# 8x8v2.net
KiCad netlist of a schematic drawn in Altium Designer
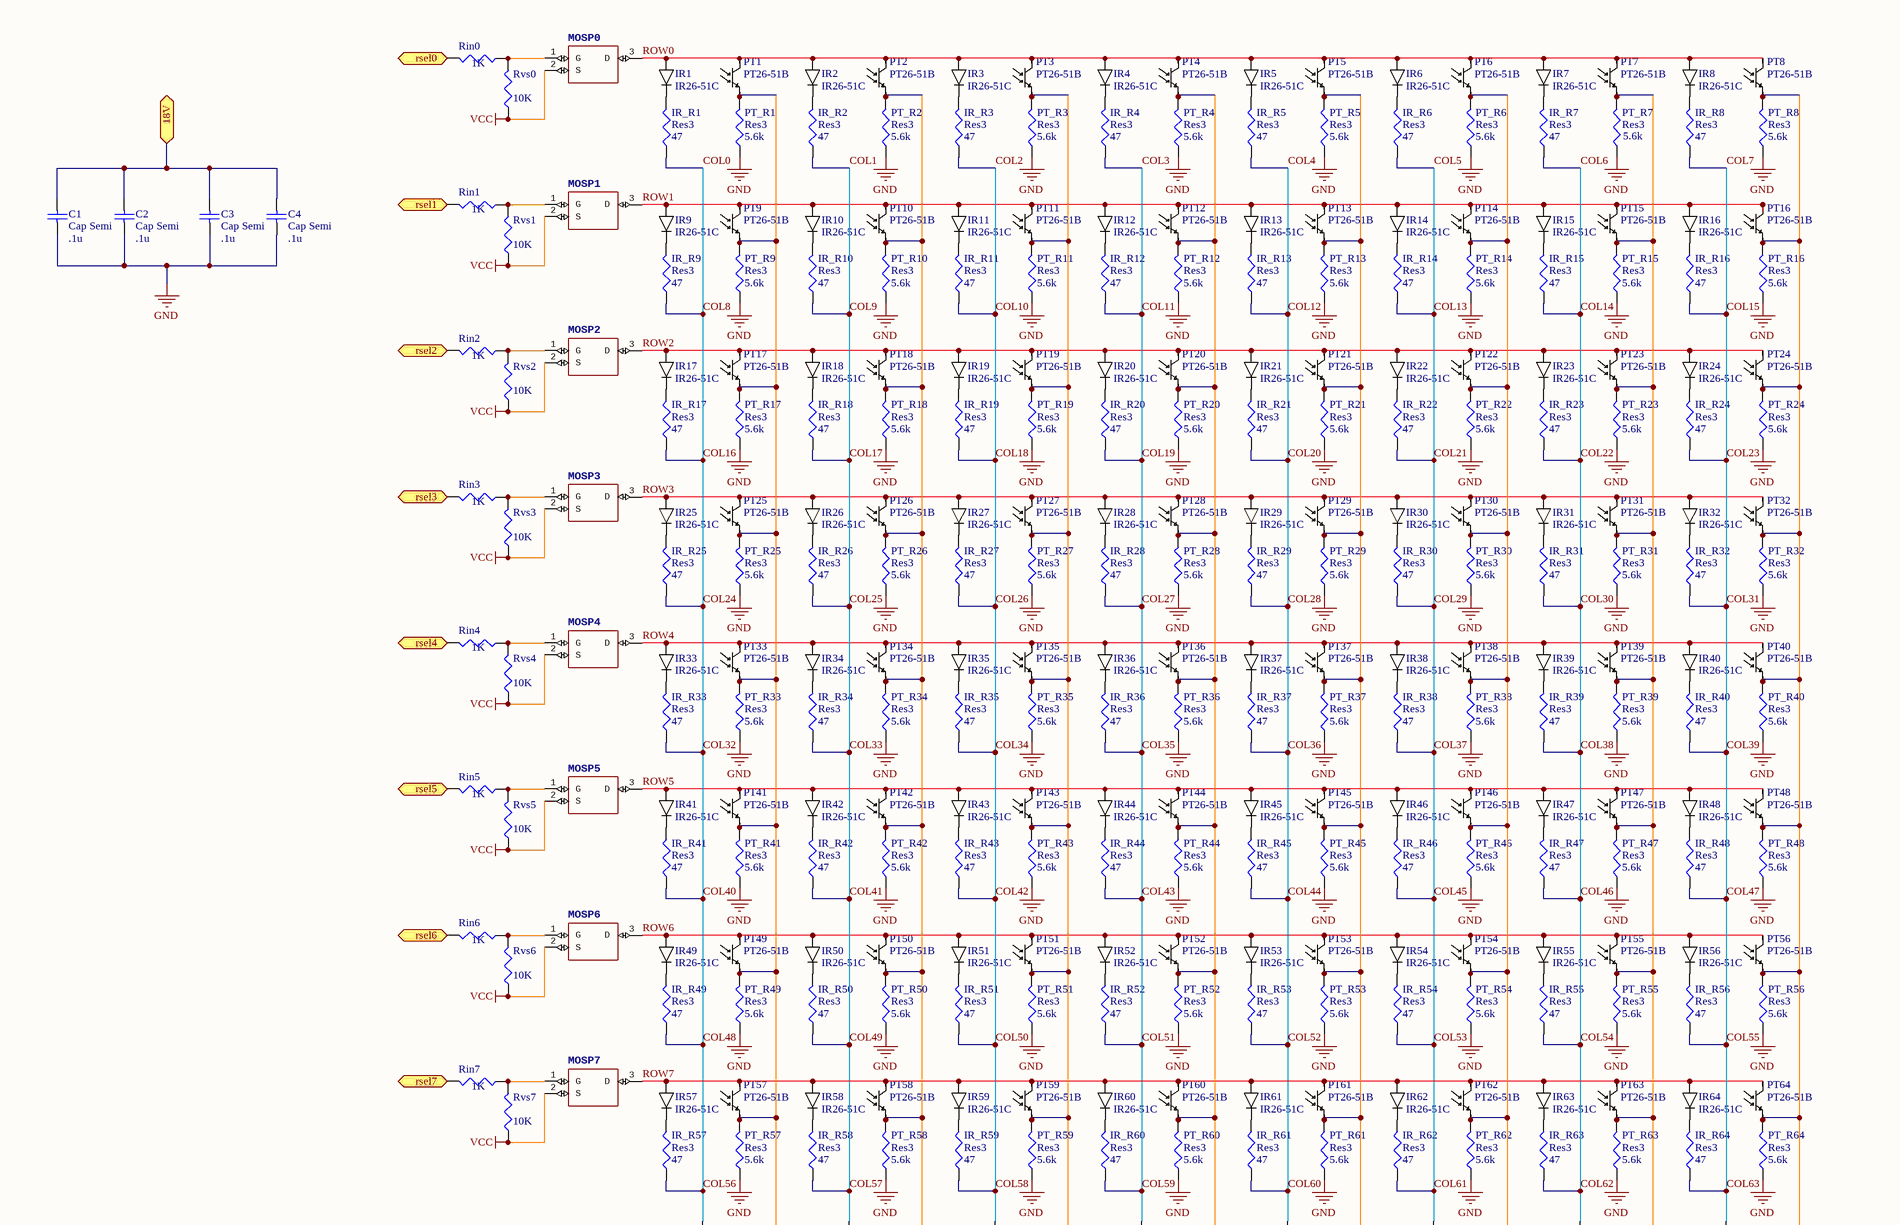
[diagram p0: 8x8v2.SchDoc, top left]
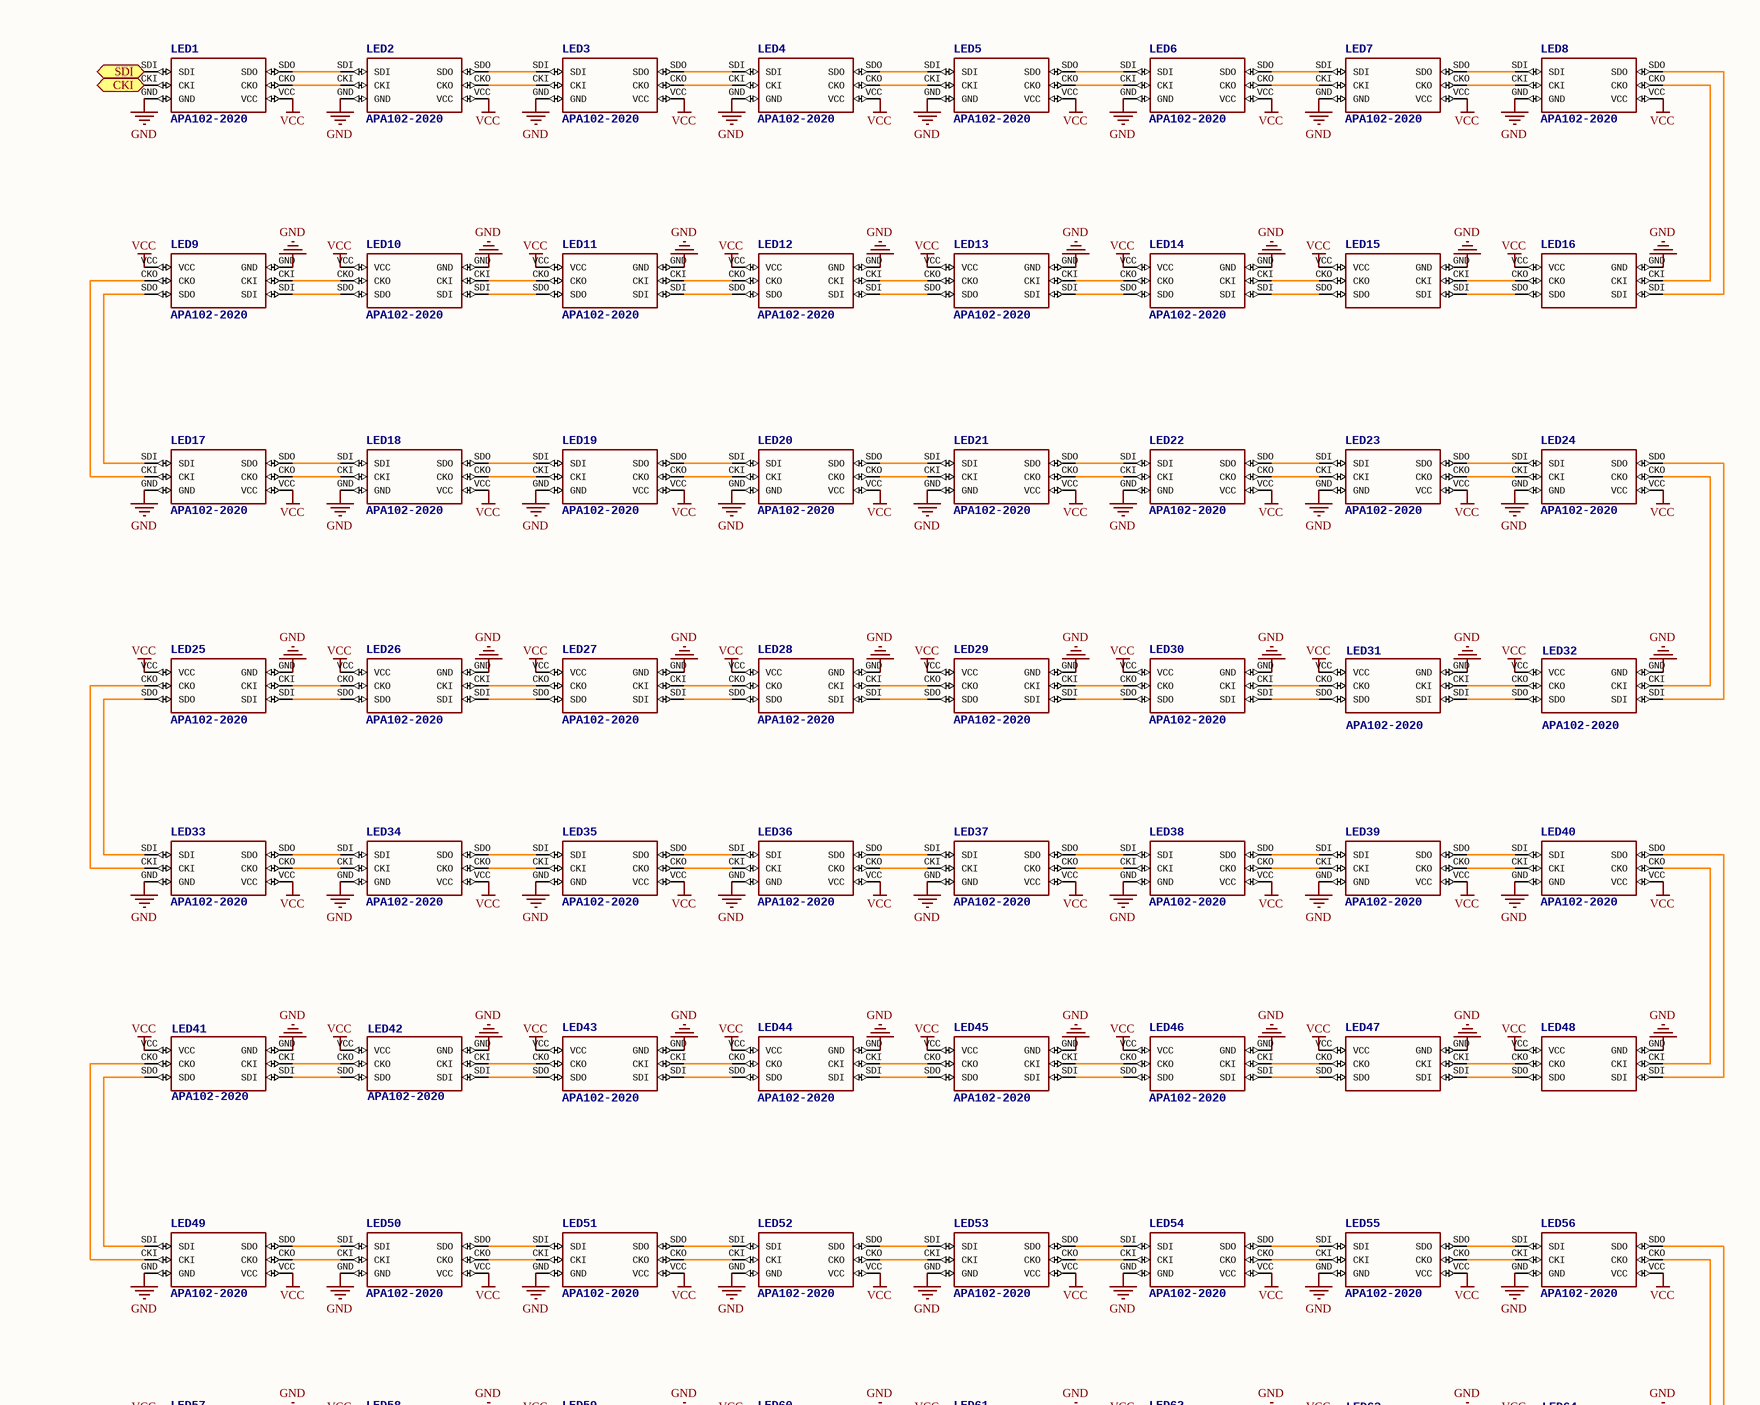
[diagram p1: 8x8v2.SchDoc, top right]
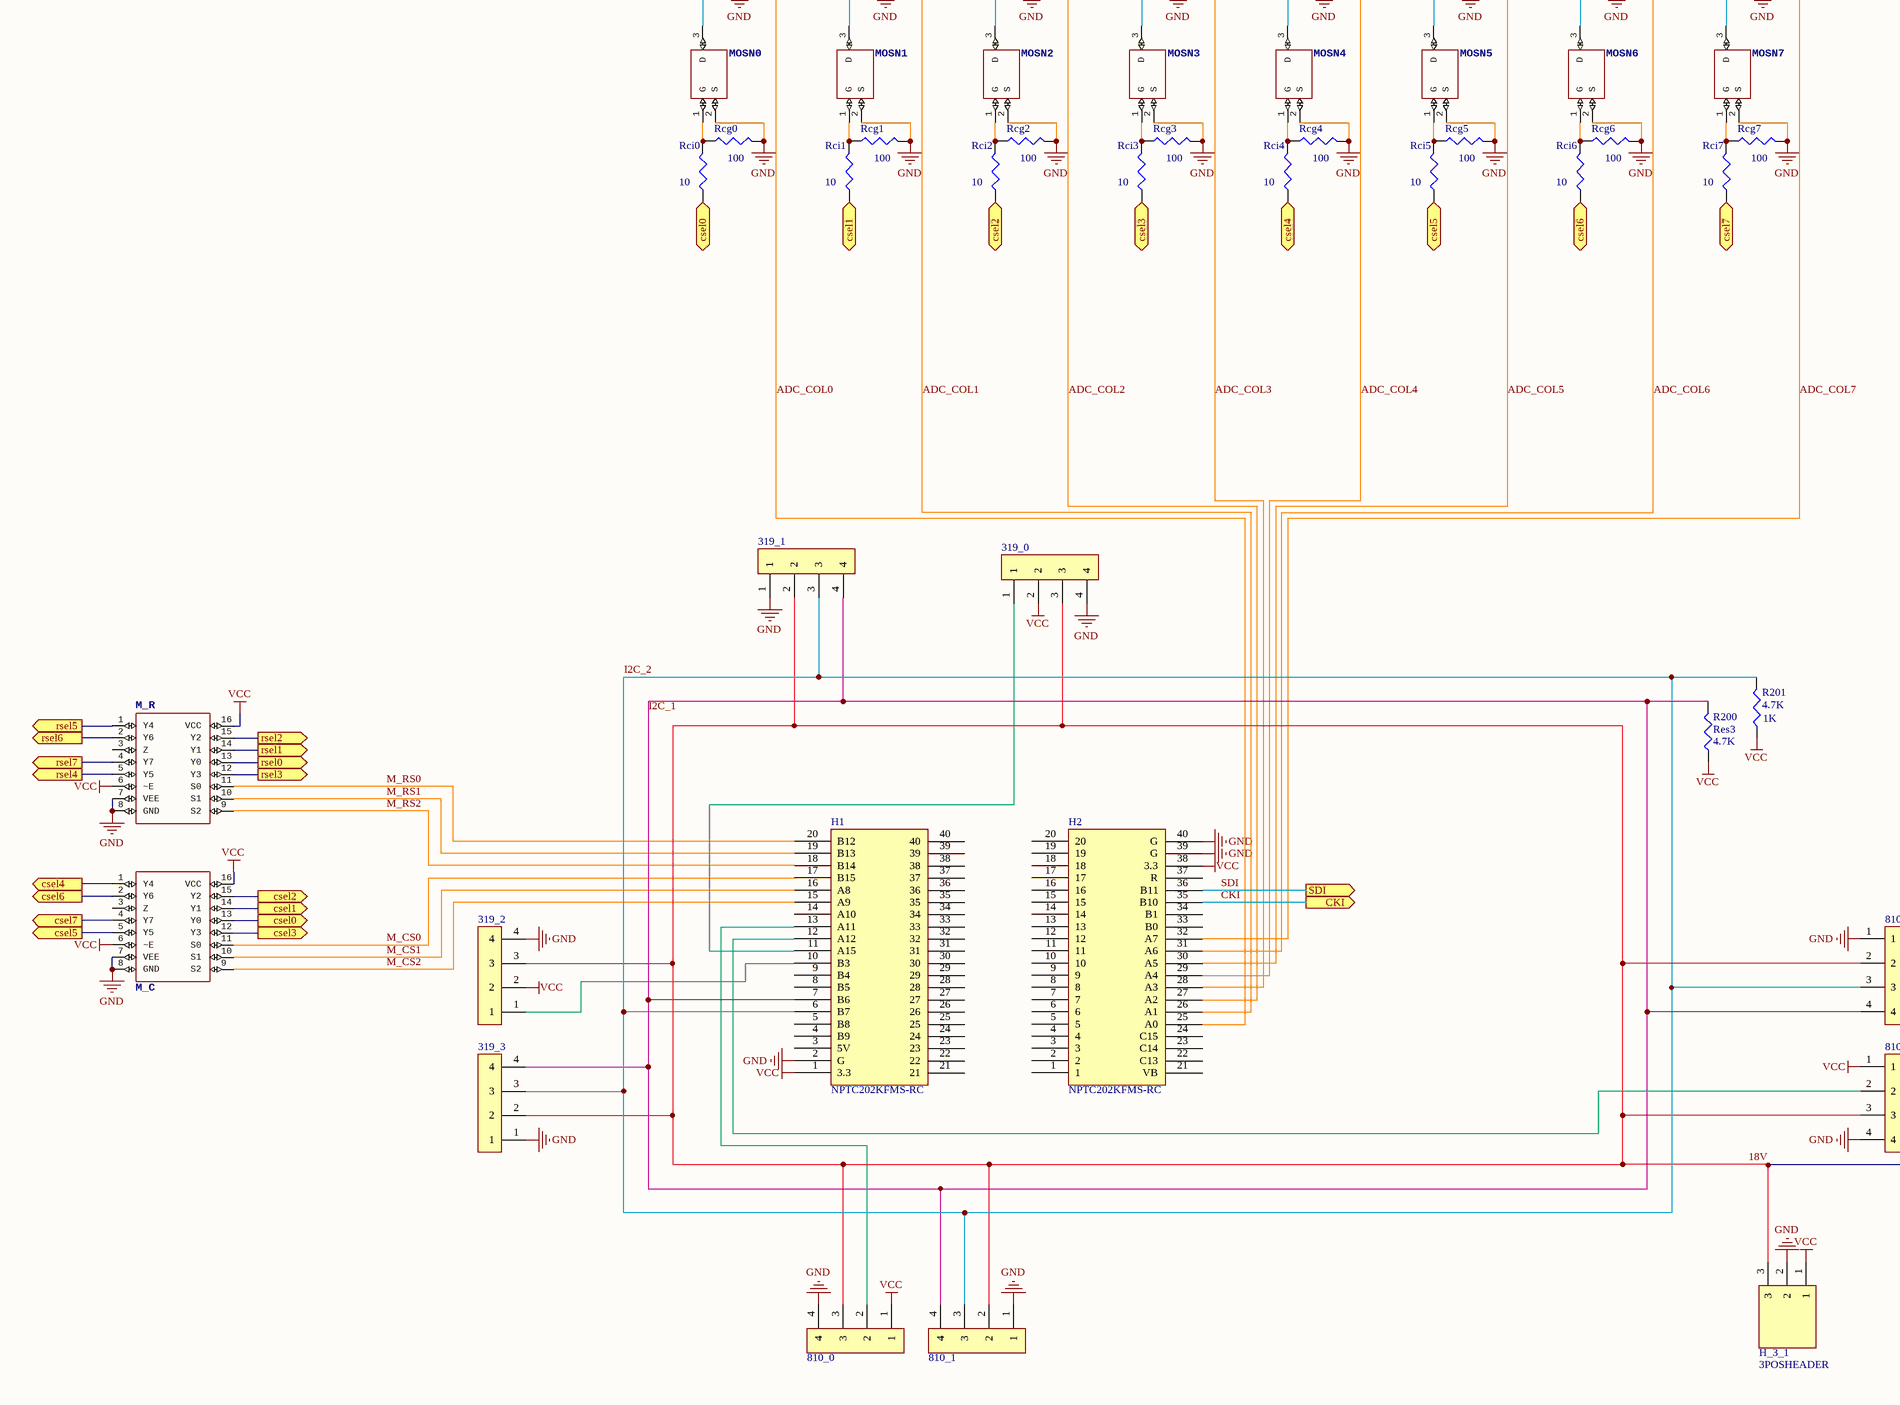
[diagram p2: 8x8v2.SchDoc, bottom left]
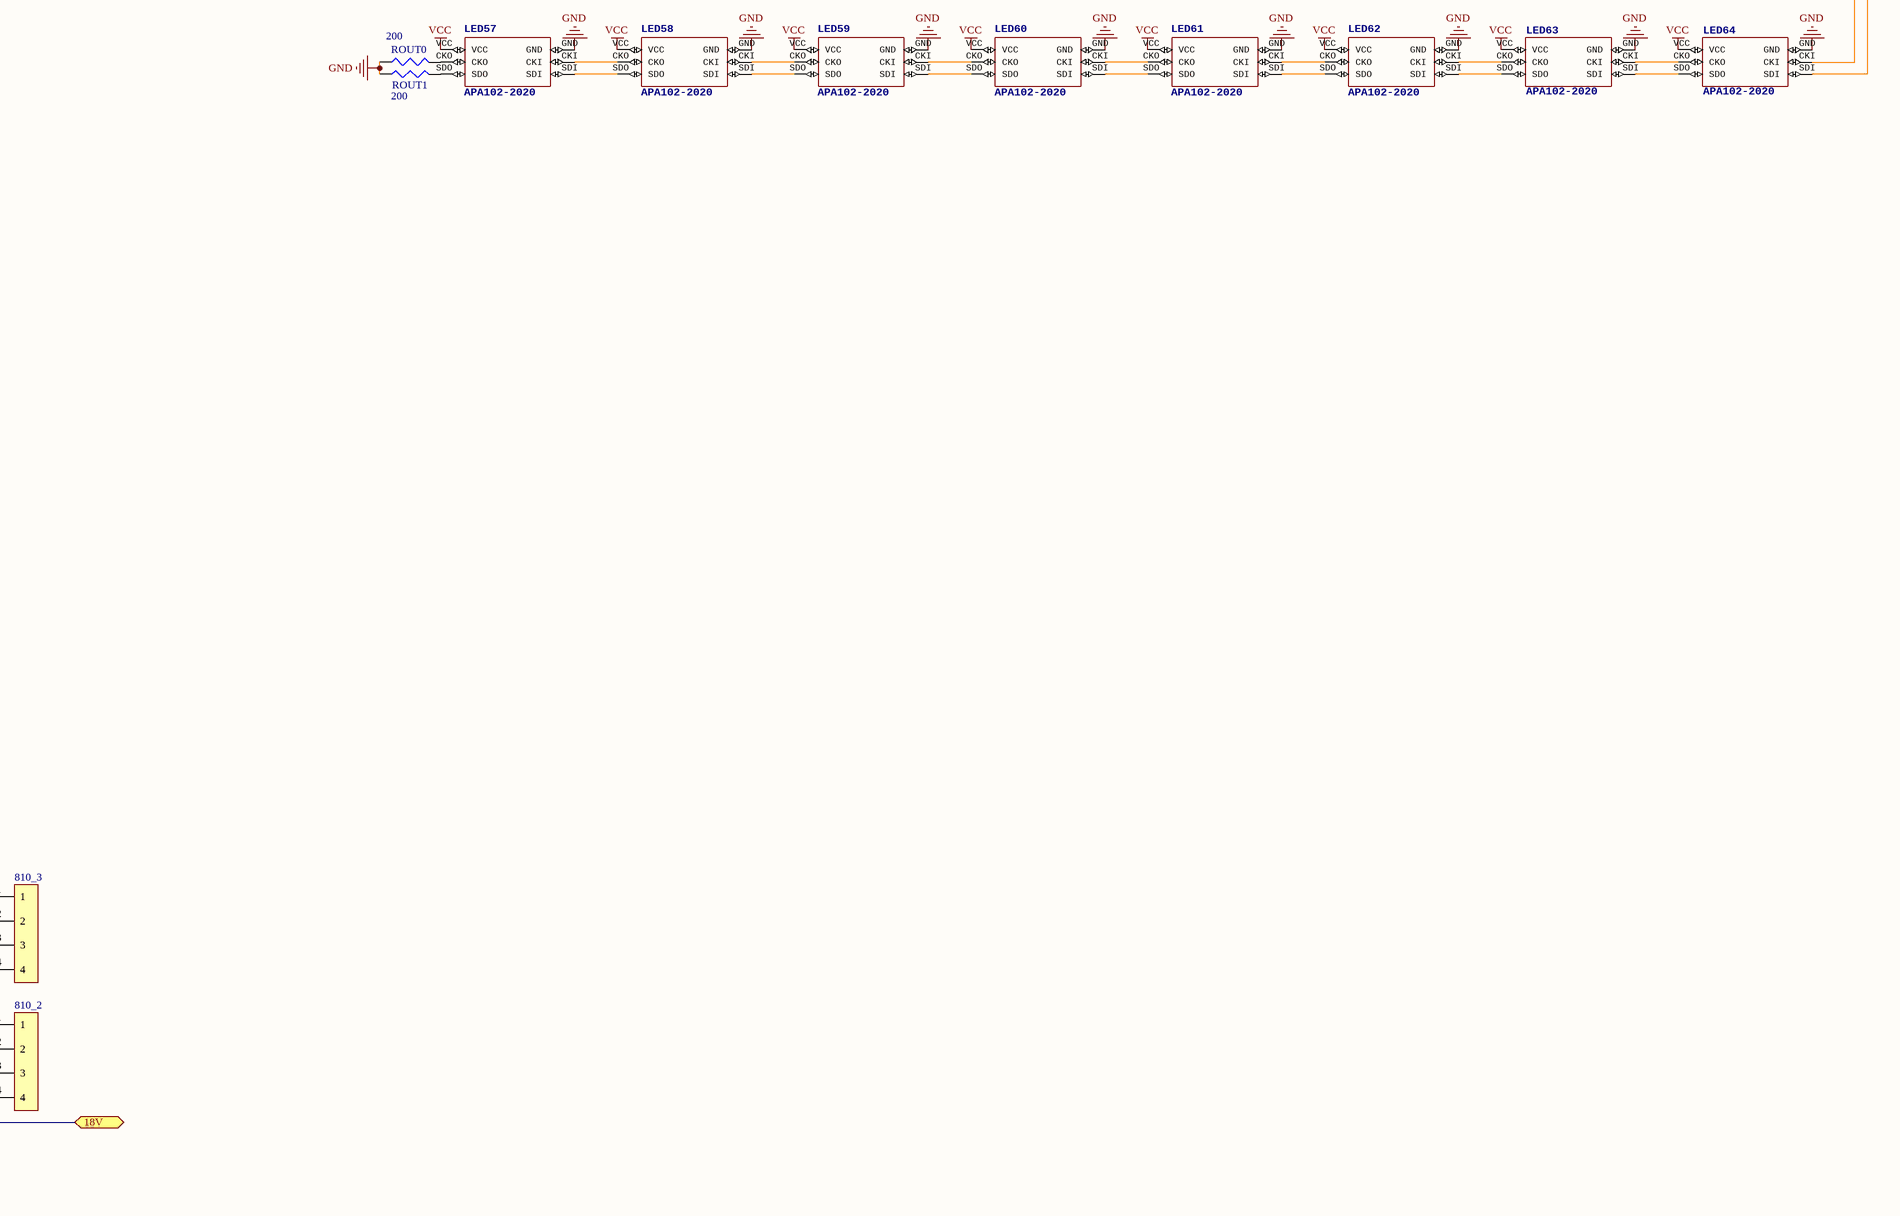
[diagram p3: 8x8v2.SchDoc, bottom right]

(export (version "E")
  (design (tool "Eeschema 10.0.6"))
  (components
    (comp (ref "319_0")
      (value "319_4")
      (footprint "319_4")
      (description "pad for mill max 319 series")
      (libsource (lib "T25_Components") (part "319_4"))
    )
    (comp (ref "319_1")
      (value "319_4")
      (footprint "319_4")
      (description "pad for mill max 319 series")
      (libsource (lib "T25_Components") (part "319_4"))
    )
    (comp (ref "319_2")
      (value "319_4")
      (footprint "319_4")
      (description "pad for mill max 319 series")
      (libsource (lib "") (part "319_4_1"))
    )
    (comp (ref "319_3")
      (value "319_4")
      (footprint "319_4")
      (description "pad for mill max 319 series")
      (libsource (lib "") (part "319_4_1"))
    )
    (comp (ref "810_0")
      (value "810_4")
      (footprint "810_4")
      (description "pad for mill max 810 series")
      (libsource (lib "T25_Components") (part "810_4"))
    )
    (comp (ref "810_1")
      (value "810_4")
      (footprint "810_4")
      (description "pad for mill max 810 series")
      (libsource (lib "T25_Components") (part "810_4"))
    )
    (comp (ref "810_2")
      (value "810_4")
      (footprint "810_4")
      (description "pad for mill max 810 series")
      (libsource (lib "") (part "810_4_1"))
    )
    (comp (ref "810_3")
      (value "810_4")
      (footprint "810_4")
      (description "pad for mill max 810 series")
      (libsource (lib "") (part "810_4_1"))
    )
    (comp (ref "C1")
      (value "Cap Semi")
      (footprint "0402")
      (description "Capacitor (Semiconductor SIM Model)")
      (fields (field (name "ALTIUM_VALUE") ".1u") (field (name "PUBLISHER") "Altium Limited"))
      (libsource (lib "Miscellaneous Devices") (part "Cap Semi"))
    )
    (comp (ref "C2")
      (value "Cap Semi")
      (footprint "0402")
      (description "Capacitor (Semiconductor SIM Model)")
      (fields (field (name "ALTIUM_VALUE") ".1u") (field (name "PUBLISHER") "Altium Limited"))
      (libsource (lib "Miscellaneous Devices") (part "Cap Semi"))
    )
    (comp (ref "C3")
      (value "Cap Semi")
      (footprint "0402")
      (description "Capacitor (Semiconductor SIM Model)")
      (fields (field (name "ALTIUM_VALUE") ".1u") (field (name "PUBLISHER") "Altium Limited"))
      (libsource (lib "Miscellaneous Devices") (part "Cap Semi"))
    )
    (comp (ref "C4")
      (value "Cap Semi")
      (footprint "0402")
      (description "Capacitor (Semiconductor SIM Model)")
      (fields (field (name "ALTIUM_VALUE") ".1u") (field (name "PUBLISHER") "Altium Limited"))
      (libsource (lib "Miscellaneous Devices") (part "Cap Semi"))
    )
    (comp (ref "H1")
      (value "NPTC202KFMS-RC")
      (footprint "NPTC202KFMS-RC")
      (description "40 Position Header Connector 0.100\" (2.54mm) Surface Mount Tin")
      (libsource (lib "T25_Components") (part "NPTC202KFMS-RC"))
    )
    (comp (ref "H2")
      (value "NPTC202KFMS-RC")
      (footprint "NPTC202KFMS-RC")
      (description "40 Position Header Connector 0.100\" (2.54mm) Surface Mount Tin")
      (libsource (lib "T25_Components") (part "NPTC202KFMS-RC"))
    )
    (comp (ref "H_3_1")
      (value "3POSHEADER")
      (footprint "3POSHEADER")
      (description "3 POS HEADER")
      (libsource (lib "T25_Components") (part "3POSHEADER"))
    )
    (comp (ref "IR1")
      (value "IR26-51C")
      (footprint "SFH 4056")
      (description "IR26-51C SMD IR Emitter")
      (libsource (lib "T25_Components") (part "IR26-51C"))
    )
    (comp (ref "IR2")
      (value "IR26-51C")
      (footprint "SFH 4056")
      (description "IR26-51C SMD IR Emitter")
      (libsource (lib "T25_Components") (part "IR26-51C"))
    )
    (comp (ref "IR3")
      (value "IR26-51C")
      (footprint "SFH 4056")
      (description "IR26-51C SMD IR Emitter")
      (libsource (lib "T25_Components") (part "IR26-51C"))
    )
    (comp (ref "IR4")
      (value "IR26-51C")
      (footprint "SFH 4056")
      (description "IR26-51C SMD IR Emitter")
      (libsource (lib "T25_Components") (part "IR26-51C"))
    )
    (comp (ref "IR5")
      (value "IR26-51C")
      (footprint "SFH 4056")
      (description "IR26-51C SMD IR Emitter")
      (libsource (lib "T25_Components") (part "IR26-51C"))
    )
    (comp (ref "IR6")
      (value "IR26-51C")
      (footprint "SFH 4056")
      (description "IR26-51C SMD IR Emitter")
      (libsource (lib "T25_Components") (part "IR26-51C"))
    )
    (comp (ref "IR7")
      (value "IR26-51C")
      (footprint "SFH 4056")
      (description "IR26-51C SMD IR Emitter")
      (libsource (lib "T25_Components") (part "IR26-51C"))
    )
    (comp (ref "IR8")
      (value "IR26-51C")
      (footprint "SFH 4056")
      (description "IR26-51C SMD IR Emitter")
      (libsource (lib "T25_Components") (part "IR26-51C"))
    )
    (comp (ref "IR9")
      (value "IR26-51C")
      (footprint "SFH 4056")
      (description "IR26-51C SMD IR Emitter")
      (libsource (lib "T25_Components") (part "IR26-51C"))
    )
    (comp (ref "IR10")
      (value "IR26-51C")
      (footprint "SFH 4056")
      (description "IR26-51C SMD IR Emitter")
      (libsource (lib "T25_Components") (part "IR26-51C"))
    )
    (comp (ref "IR11")
      (value "IR26-51C")
      (footprint "SFH 4056")
      (description "IR26-51C SMD IR Emitter")
      (libsource (lib "T25_Components") (part "IR26-51C"))
    )
    (comp (ref "IR12")
      (value "IR26-51C")
      (footprint "SFH 4056")
      (description "IR26-51C SMD IR Emitter")
      (libsource (lib "T25_Components") (part "IR26-51C"))
    )
    (comp (ref "IR13")
      (value "IR26-51C")
      (footprint "SFH 4056")
      (description "IR26-51C SMD IR Emitter")
      (libsource (lib "T25_Components") (part "IR26-51C"))
    )
    (comp (ref "IR14")
      (value "IR26-51C")
      (footprint "SFH 4056")
      (description "IR26-51C SMD IR Emitter")
      (libsource (lib "T25_Components") (part "IR26-51C"))
    )
    (comp (ref "IR15")
      (value "IR26-51C")
      (footprint "SFH 4056")
      (description "IR26-51C SMD IR Emitter")
      (libsource (lib "T25_Components") (part "IR26-51C"))
    )
    (comp (ref "IR16")
      (value "IR26-51C")
      (footprint "SFH 4056")
      (description "IR26-51C SMD IR Emitter")
      (libsource (lib "T25_Components") (part "IR26-51C"))
    )
    (comp (ref "IR17")
      (value "IR26-51C")
      (footprint "SFH 4056")
      (description "IR26-51C SMD IR Emitter")
      (libsource (lib "T25_Components") (part "IR26-51C"))
    )
    (comp (ref "IR18")
      (value "IR26-51C")
      (footprint "SFH 4056")
      (description "IR26-51C SMD IR Emitter")
      (libsource (lib "T25_Components") (part "IR26-51C"))
    )
    (comp (ref "IR19")
      (value "IR26-51C")
      (footprint "SFH 4056")
      (description "IR26-51C SMD IR Emitter")
      (libsource (lib "T25_Components") (part "IR26-51C"))
    )
    (comp (ref "IR20")
      (value "IR26-51C")
      (footprint "SFH 4056")
      (description "IR26-51C SMD IR Emitter")
      (libsource (lib "T25_Components") (part "IR26-51C"))
    )
    (comp (ref "IR21")
      (value "IR26-51C")
      (footprint "SFH 4056")
      (description "IR26-51C SMD IR Emitter")
      (libsource (lib "T25_Components") (part "IR26-51C"))
    )
    (comp (ref "IR22")
      (value "IR26-51C")
      (footprint "SFH 4056")
      (description "IR26-51C SMD IR Emitter")
      (libsource (lib "T25_Components") (part "IR26-51C"))
    )
    (comp (ref "IR23")
      (value "IR26-51C")
      (footprint "SFH 4056")
      (description "IR26-51C SMD IR Emitter")
      (libsource (lib "T25_Components") (part "IR26-51C"))
    )
    (comp (ref "IR24")
      (value "IR26-51C")
      (footprint "SFH 4056")
      (description "IR26-51C SMD IR Emitter")
      (libsource (lib "T25_Components") (part "IR26-51C"))
    )
    (comp (ref "IR25")
      (value "IR26-51C")
      (footprint "SFH 4056")
      (description "IR26-51C SMD IR Emitter")
      (libsource (lib "T25_Components") (part "IR26-51C"))
    )
    (comp (ref "IR26")
      (value "IR26-51C")
      (footprint "SFH 4056")
      (description "IR26-51C SMD IR Emitter")
      (libsource (lib "T25_Components") (part "IR26-51C"))
    )
    (comp (ref "IR27")
      (value "IR26-51C")
      (footprint "SFH 4056")
      (description "IR26-51C SMD IR Emitter")
      (libsource (lib "T25_Components") (part "IR26-51C"))
    )
    (comp (ref "IR28")
      (value "IR26-51C")
      (footprint "SFH 4056")
      (description "IR26-51C SMD IR Emitter")
      (libsource (lib "T25_Components") (part "IR26-51C"))
    )
    (comp (ref "IR29")
      (value "IR26-51C")
      (footprint "SFH 4056")
      (description "IR26-51C SMD IR Emitter")
      (libsource (lib "T25_Components") (part "IR26-51C"))
    )
    (comp (ref "IR30")
      (value "IR26-51C")
      (footprint "SFH 4056")
      (description "IR26-51C SMD IR Emitter")
      (libsource (lib "T25_Components") (part "IR26-51C"))
    )
    (comp (ref "IR31")
      (value "IR26-51C")
      (footprint "SFH 4056")
      (description "IR26-51C SMD IR Emitter")
      (libsource (lib "T25_Components") (part "IR26-51C"))
    )
    (comp (ref "IR32")
      (value "IR26-51C")
      (footprint "SFH 4056")
      (description "IR26-51C SMD IR Emitter")
      (libsource (lib "T25_Components") (part "IR26-51C"))
    )
    (comp (ref "IR33")
      (value "IR26-51C")
      (footprint "SFH 4056")
      (description "IR26-51C SMD IR Emitter")
      (libsource (lib "T25_Components") (part "IR26-51C"))
    )
    (comp (ref "IR34")
      (value "IR26-51C")
      (footprint "SFH 4056")
      (description "IR26-51C SMD IR Emitter")
      (libsource (lib "T25_Components") (part "IR26-51C"))
    )
    (comp (ref "IR35")
      (value "IR26-51C")
      (footprint "SFH 4056")
      (description "IR26-51C SMD IR Emitter")
      (libsource (lib "T25_Components") (part "IR26-51C"))
    )
    (comp (ref "IR36")
      (value "IR26-51C")
      (footprint "SFH 4056")
      (description "IR26-51C SMD IR Emitter")
      (libsource (lib "T25_Components") (part "IR26-51C"))
    )
    (comp (ref "IR37")
      (value "IR26-51C")
      (footprint "SFH 4056")
      (description "IR26-51C SMD IR Emitter")
      (libsource (lib "T25_Components") (part "IR26-51C"))
    )
    (comp (ref "IR38")
      (value "IR26-51C")
      (footprint "SFH 4056")
      (description "IR26-51C SMD IR Emitter")
      (libsource (lib "T25_Components") (part "IR26-51C"))
    )
    (comp (ref "IR39")
      (value "IR26-51C")
      (footprint "SFH 4056")
      (description "IR26-51C SMD IR Emitter")
      (libsource (lib "T25_Components") (part "IR26-51C"))
    )
    (comp (ref "IR40")
      (value "IR26-51C")
      (footprint "SFH 4056")
      (description "IR26-51C SMD IR Emitter")
      (libsource (lib "T25_Components") (part "IR26-51C"))
    )
    (comp (ref "IR41")
      (value "IR26-51C")
      (footprint "SFH 4056")
      (description "IR26-51C SMD IR Emitter")
      (libsource (lib "T25_Components") (part "IR26-51C"))
    )
    (comp (ref "IR42")
      (value "IR26-51C")
      (footprint "SFH 4056")
      (description "IR26-51C SMD IR Emitter")
      (libsource (lib "T25_Components") (part "IR26-51C"))
    )
    (comp (ref "IR43")
      (value "IR26-51C")
      (footprint "SFH 4056")
      (description "IR26-51C SMD IR Emitter")
      (libsource (lib "T25_Components") (part "IR26-51C"))
    )
    (comp (ref "IR44")
      (value "IR26-51C")
      (footprint "SFH 4056")
      (description "IR26-51C SMD IR Emitter")
      (libsource (lib "T25_Components") (part "IR26-51C"))
    )
    (comp (ref "IR45")
      (value "IR26-51C")
      (footprint "SFH 4056")
      (description "IR26-51C SMD IR Emitter")
      (libsource (lib "T25_Components") (part "IR26-51C"))
    )
    (comp (ref "IR46")
      (value "IR26-51C")
      (footprint "SFH 4056")
      (description "IR26-51C SMD IR Emitter")
      (libsource (lib "T25_Components") (part "IR26-51C"))
    )
    (comp (ref "IR47")
      (value "IR26-51C")
      (footprint "SFH 4056")
      (description "IR26-51C SMD IR Emitter")
      (libsource (lib "T25_Components") (part "IR26-51C"))
    )
    (comp (ref "IR48")
      (value "IR26-51C")
      (footprint "SFH 4056")
      (description "IR26-51C SMD IR Emitter")
      (libsource (lib "T25_Components") (part "IR26-51C"))
    )
    (comp (ref "IR49")
      (value "IR26-51C")
      (footprint "SFH 4056")
      (description "IR26-51C SMD IR Emitter")
      (libsource (lib "T25_Components") (part "IR26-51C"))
    )
    (comp (ref "IR50")
      (value "IR26-51C")
      (footprint "SFH 4056")
      (description "IR26-51C SMD IR Emitter")
      (libsource (lib "T25_Components") (part "IR26-51C"))
    )
    (comp (ref "IR51")
      (value "IR26-51C")
      (footprint "SFH 4056")
      (description "IR26-51C SMD IR Emitter")
      (libsource (lib "T25_Components") (part "IR26-51C"))
    )
    (comp (ref "IR52")
      (value "IR26-51C")
      (footprint "SFH 4056")
      (description "IR26-51C SMD IR Emitter")
      (libsource (lib "T25_Components") (part "IR26-51C"))
    )
    (comp (ref "IR53")
      (value "IR26-51C")
      (footprint "SFH 4056")
      (description "IR26-51C SMD IR Emitter")
      (libsource (lib "T25_Components") (part "IR26-51C"))
    )
    (comp (ref "IR54")
      (value "IR26-51C")
      (footprint "SFH 4056")
      (description "IR26-51C SMD IR Emitter")
      (libsource (lib "T25_Components") (part "IR26-51C"))
    )
    (comp (ref "IR55")
      (value "IR26-51C")
      (footprint "SFH 4056")
      (description "IR26-51C SMD IR Emitter")
      (libsource (lib "T25_Components") (part "IR26-51C"))
    )
    (comp (ref "IR56")
      (value "IR26-51C")
      (footprint "SFH 4056")
      (description "IR26-51C SMD IR Emitter")
      (libsource (lib "T25_Components") (part "IR26-51C"))
    )
    (comp (ref "IR57")
      (value "IR26-51C")
      (footprint "SFH 4056")
      (description "IR26-51C SMD IR Emitter")
      (libsource (lib "T25_Components") (part "IR26-51C"))
    )
    (comp (ref "IR58")
      (value "IR26-51C")
      (footprint "SFH 4056")
      (description "IR26-51C SMD IR Emitter")
      (libsource (lib "T25_Components") (part "IR26-51C"))
    )
    (comp (ref "IR59")
      (value "IR26-51C")
      (footprint "SFH 4056")
      (description "IR26-51C SMD IR Emitter")
      (libsource (lib "T25_Components") (part "IR26-51C"))
    )
    (comp (ref "IR60")
      (value "IR26-51C")
      (footprint "SFH 4056")
      (description "IR26-51C SMD IR Emitter")
      (libsource (lib "T25_Components") (part "IR26-51C"))
    )
    (comp (ref "IR61")
      (value "IR26-51C")
      (footprint "SFH 4056")
      (description "IR26-51C SMD IR Emitter")
      (libsource (lib "T25_Components") (part "IR26-51C"))
    )
    (comp (ref "IR62")
      (value "IR26-51C")
      (footprint "SFH 4056")
      (description "IR26-51C SMD IR Emitter")
      (libsource (lib "T25_Components") (part "IR26-51C"))
    )
    (comp (ref "IR63")
      (value "IR26-51C")
      (footprint "SFH 4056")
      (description "IR26-51C SMD IR Emitter")
      (libsource (lib "T25_Components") (part "IR26-51C"))
    )
    (comp (ref "IR64")
      (value "IR26-51C")
      (footprint "SFH 4056")
      (description "IR26-51C SMD IR Emitter")
      (libsource (lib "T25_Components") (part "IR26-51C"))
    )
    (comp (ref "IR_R1")
      (value "Res3")
      (footprint "J1-0603")
      (description "IR Emitter Resistor")
      (fields (field (name "ALTIUM_VALUE") "47") (field (name "PUBLISHER") "Altium Limited"))
      (libsource (lib "Miscellaneous Devices") (part "Res3"))
    )
    (comp (ref "IR_R2")
      (value "Res3")
      (footprint "J1-0603")
      (description "IR Emitter Resistor")
      (fields (field (name "ALTIUM_VALUE") "47") (field (name "PUBLISHER") "Altium Limited"))
      (libsource (lib "Miscellaneous Devices") (part "Res3"))
    )
    (comp (ref "IR_R3")
      (value "Res3")
      (footprint "J1-0603")
      (description "IR Emitter Resistor")
      (fields (field (name "ALTIUM_VALUE") "47") (field (name "PUBLISHER") "Altium Limited"))
      (libsource (lib "Miscellaneous Devices") (part "Res3"))
    )
    (comp (ref "IR_R4")
      (value "Res3")
      (footprint "J1-0603")
      (description "IR Emitter Resistor")
      (fields (field (name "ALTIUM_VALUE") "47") (field (name "PUBLISHER") "Altium Limited"))
      (libsource (lib "Miscellaneous Devices") (part "Res3"))
    )
    (comp (ref "IR_R5")
      (value "Res3")
      (footprint "J1-0603")
      (description "IR Emitter Resistor")
      (fields (field (name "ALTIUM_VALUE") "47") (field (name "PUBLISHER") "Altium Limited"))
      (libsource (lib "Miscellaneous Devices") (part "Res3"))
    )
    (comp (ref "IR_R6")
      (value "Res3")
      (footprint "J1-0603")
      (description "IR Emitter Resistor")
      (fields (field (name "ALTIUM_VALUE") "47") (field (name "PUBLISHER") "Altium Limited"))
      (libsource (lib "Miscellaneous Devices") (part "Res3"))
    )
    (comp (ref "IR_R7")
      (value "Res3")
      (footprint "J1-0603")
      (description "IR Emitter Resistor")
      (fields (field (name "ALTIUM_VALUE") "47") (field (name "PUBLISHER") "Altium Limited"))
      (libsource (lib "Miscellaneous Devices") (part "Res3"))
    )
    (comp (ref "IR_R8")
      (value "Res3")
      (footprint "J1-0603")
      (description "IR Emitter Resistor")
      (fields (field (name "ALTIUM_VALUE") "47") (field (name "PUBLISHER") "Altium Limited"))
      (libsource (lib "Miscellaneous Devices") (part "Res3"))
    )
    (comp (ref "IR_R9")
      (value "Res3")
      (footprint "J1-0603")
      (description "IR Emitter Resistor")
      (fields (field (name "ALTIUM_VALUE") "47") (field (name "PUBLISHER") "Altium Limited"))
      (libsource (lib "Miscellaneous Devices") (part "Res3"))
    )
    (comp (ref "IR_R10")
      (value "Res3")
      (footprint "J1-0603")
      (description "IR Emitter Resistor")
      (fields (field (name "ALTIUM_VALUE") "47") (field (name "PUBLISHER") "Altium Limited"))
      (libsource (lib "Miscellaneous Devices") (part "Res3"))
    )
    (comp (ref "IR_R11")
      (value "Res3")
      (footprint "J1-0603")
      (description "IR Emitter Resistor")
      (fields (field (name "ALTIUM_VALUE") "47") (field (name "PUBLISHER") "Altium Limited"))
      (libsource (lib "Miscellaneous Devices") (part "Res3"))
    )
    (comp (ref "IR_R12")
      (value "Res3")
      (footprint "J1-0603")
      (description "IR Emitter Resistor")
      (fields (field (name "ALTIUM_VALUE") "47") (field (name "PUBLISHER") "Altium Limited"))
      (libsource (lib "Miscellaneous Devices") (part "Res3"))
    )
    (comp (ref "IR_R13")
      (value "Res3")
      (footprint "J1-0603")
      (description "IR Emitter Resistor")
      (fields (field (name "ALTIUM_VALUE") "47") (field (name "PUBLISHER") "Altium Limited"))
      (libsource (lib "Miscellaneous Devices") (part "Res3"))
    )
    (comp (ref "IR_R14")
      (value "Res3")
      (footprint "J1-0603")
      (description "IR Emitter Resistor")
      (fields (field (name "ALTIUM_VALUE") "47") (field (name "PUBLISHER") "Altium Limited"))
      (libsource (lib "Miscellaneous Devices") (part "Res3"))
    )
    (comp (ref "IR_R15")
      (value "Res3")
      (footprint "J1-0603")
      (description "IR Emitter Resistor")
      (fields (field (name "ALTIUM_VALUE") "47") (field (name "PUBLISHER") "Altium Limited"))
      (libsource (lib "Miscellaneous Devices") (part "Res3"))
    )
    (comp (ref "IR_R16")
      (value "Res3")
      (footprint "J1-0603")
      (description "IR Emitter Resistor")
      (fields (field (name "ALTIUM_VALUE") "47") (field (name "PUBLISHER") "Altium Limited"))
      (libsource (lib "Miscellaneous Devices") (part "Res3"))
    )
    (comp (ref "IR_R17")
      (value "Res3")
      (footprint "J1-0603")
      (description "IR Emitter Resistor")
      (fields (field (name "ALTIUM_VALUE") "47") (field (name "PUBLISHER") "Altium Limited"))
      (libsource (lib "Miscellaneous Devices") (part "Res3"))
    )
    (comp (ref "IR_R18")
      (value "Res3")
      (footprint "J1-0603")
      (description "IR Emitter Resistor")
      (fields (field (name "ALTIUM_VALUE") "47") (field (name "PUBLISHER") "Altium Limited"))
      (libsource (lib "Miscellaneous Devices") (part "Res3"))
    )
    (comp (ref "IR_R19")
      (value "Res3")
      (footprint "J1-0603")
      (description "IR Emitter Resistor")
      (fields (field (name "ALTIUM_VALUE") "47") (field (name "PUBLISHER") "Altium Limited"))
      (libsource (lib "Miscellaneous Devices") (part "Res3"))
    )
    (comp (ref "IR_R20")
      (value "Res3")
      (footprint "J1-0603")
      (description "IR Emitter Resistor")
      (fields (field (name "ALTIUM_VALUE") "47") (field (name "PUBLISHER") "Altium Limited"))
      (libsource (lib "Miscellaneous Devices") (part "Res3"))
    )
    (comp (ref "IR_R21")
      (value "Res3")
      (footprint "J1-0603")
      (description "IR Emitter Resistor")
      (fields (field (name "ALTIUM_VALUE") "47") (field (name "PUBLISHER") "Altium Limited"))
      (libsource (lib "Miscellaneous Devices") (part "Res3"))
    )
    (comp (ref "IR_R22")
      (value "Res3")
      (footprint "J1-0603")
      (description "IR Emitter Resistor")
      (fields (field (name "ALTIUM_VALUE") "47") (field (name "PUBLISHER") "Altium Limited"))
      (libsource (lib "Miscellaneous Devices") (part "Res3"))
    )
    (comp (ref "IR_R23")
      (value "Res3")
      (footprint "J1-0603")
      (description "IR Emitter Resistor")
      (fields (field (name "ALTIUM_VALUE") "47") (field (name "PUBLISHER") "Altium Limited"))
      (libsource (lib "Miscellaneous Devices") (part "Res3"))
    )
    (comp (ref "IR_R24")
      (value "Res3")
      (footprint "J1-0603")
      (description "IR Emitter Resistor")
      (fields (field (name "ALTIUM_VALUE") "47") (field (name "PUBLISHER") "Altium Limited"))
      (libsource (lib "Miscellaneous Devices") (part "Res3"))
    )
    (comp (ref "IR_R25")
      (value "Res3")
      (footprint "J1-0603")
      (description "IR Emitter Resistor")
      (fields (field (name "ALTIUM_VALUE") "47") (field (name "PUBLISHER") "Altium Limited"))
      (libsource (lib "Miscellaneous Devices") (part "Res3"))
    )
    (comp (ref "IR_R26")
      (value "Res3")
      (footprint "J1-0603")
      (description "IR Emitter Resistor")
      (fields (field (name "ALTIUM_VALUE") "47") (field (name "PUBLISHER") "Altium Limited"))
      (libsource (lib "Miscellaneous Devices") (part "Res3"))
    )
    (comp (ref "IR_R27")
      (value "Res3")
      (footprint "J1-0603")
      (description "IR Emitter Resistor")
      (fields (field (name "ALTIUM_VALUE") "47") (field (name "PUBLISHER") "Altium Limited"))
      (libsource (lib "Miscellaneous Devices") (part "Res3"))
    )
    (comp (ref "IR_R28")
      (value "Res3")
      (footprint "J1-0603")
      (description "IR Emitter Resistor")
      (fields (field (name "ALTIUM_VALUE") "47") (field (name "PUBLISHER") "Altium Limited"))
      (libsource (lib "Miscellaneous Devices") (part "Res3"))
    )
    (comp (ref "IR_R29")
      (value "Res3")
      (footprint "J1-0603")
      (description "IR Emitter Resistor")
      (fields (field (name "ALTIUM_VALUE") "47") (field (name "PUBLISHER") "Altium Limited"))
      (libsource (lib "Miscellaneous Devices") (part "Res3"))
    )
    (comp (ref "IR_R30")
      (value "Res3")
      (footprint "J1-0603")
      (description "IR Emitter Resistor")
      (fields (field (name "ALTIUM_VALUE") "47") (field (name "PUBLISHER") "Altium Limited"))
      (libsource (lib "Miscellaneous Devices") (part "Res3"))
    )
    (comp (ref "IR_R31")
      (value "Res3")
      (footprint "J1-0603")
      (description "IR Emitter Resistor")
      (fields (field (name "ALTIUM_VALUE") "47") (field (name "PUBLISHER") "Altium Limited"))
      (libsource (lib "Miscellaneous Devices") (part "Res3"))
    )
    (comp (ref "IR_R32")
      (value "Res3")
      (footprint "J1-0603")
      (description "IR Emitter Resistor")
      (fields (field (name "ALTIUM_VALUE") "47") (field (name "PUBLISHER") "Altium Limited"))
      (libsource (lib "Miscellaneous Devices") (part "Res3"))
    )
    (comp (ref "IR_R33")
      (value "Res3")
      (footprint "J1-0603")
      (description "IR Emitter Resistor")
      (fields (field (name "ALTIUM_VALUE") "47") (field (name "PUBLISHER") "Altium Limited"))
      (libsource (lib "Miscellaneous Devices") (part "Res3"))
    )
    (comp (ref "IR_R34")
      (value "Res3")
      (footprint "J1-0603")
      (description "IR Emitter Resistor")
      (fields (field (name "ALTIUM_VALUE") "47") (field (name "PUBLISHER") "Altium Limited"))
      (libsource (lib "Miscellaneous Devices") (part "Res3"))
    )
    (comp (ref "IR_R35")
      (value "Res3")
      (footprint "J1-0603")
      (description "IR Emitter Resistor")
      (fields (field (name "ALTIUM_VALUE") "47") (field (name "PUBLISHER") "Altium Limited"))
      (libsource (lib "Miscellaneous Devices") (part "Res3"))
    )
    (comp (ref "IR_R36")
      (value "Res3")
      (footprint "J1-0603")
      (description "IR Emitter Resistor")
      (fields (field (name "ALTIUM_VALUE") "47") (field (name "PUBLISHER") "Altium Limited"))
      (libsource (lib "Miscellaneous Devices") (part "Res3"))
    )
    (comp (ref "IR_R37")
      (value "Res3")
      (footprint "J1-0603")
      (description "IR Emitter Resistor")
      (fields (field (name "ALTIUM_VALUE") "47") (field (name "PUBLISHER") "Altium Limited"))
      (libsource (lib "Miscellaneous Devices") (part "Res3"))
    )
    (comp (ref "IR_R38")
      (value "Res3")
      (footprint "J1-0603")
      (description "IR Emitter Resistor")
      (fields (field (name "ALTIUM_VALUE") "47") (field (name "PUBLISHER") "Altium Limited"))
      (libsource (lib "Miscellaneous Devices") (part "Res3"))
    )
    (comp (ref "IR_R39")
      (value "Res3")
      (footprint "J1-0603")
      (description "IR Emitter Resistor")
      (fields (field (name "ALTIUM_VALUE") "47") (field (name "PUBLISHER") "Altium Limited"))
      (libsource (lib "Miscellaneous Devices") (part "Res3"))
    )
    (comp (ref "IR_R40")
      (value "Res3")
      (footprint "J1-0603")
      (description "IR Emitter Resistor")
      (fields (field (name "ALTIUM_VALUE") "47") (field (name "PUBLISHER") "Altium Limited"))
      (libsource (lib "Miscellaneous Devices") (part "Res3"))
    )
    (comp (ref "IR_R41")
      (value "Res3")
      (footprint "J1-0603")
      (description "IR Emitter Resistor")
      (fields (field (name "ALTIUM_VALUE") "47") (field (name "PUBLISHER") "Altium Limited"))
      (libsource (lib "Miscellaneous Devices") (part "Res3"))
    )
    (comp (ref "IR_R42")
      (value "Res3")
      (footprint "J1-0603")
      (description "IR Emitter Resistor")
      (fields (field (name "ALTIUM_VALUE") "47") (field (name "PUBLISHER") "Altium Limited"))
      (libsource (lib "Miscellaneous Devices") (part "Res3"))
    )
    (comp (ref "IR_R43")
      (value "Res3")
      (footprint "J1-0603")
      (description "IR Emitter Resistor")
      (fields (field (name "ALTIUM_VALUE") "47") (field (name "PUBLISHER") "Altium Limited"))
      (libsource (lib "Miscellaneous Devices") (part "Res3"))
    )
    (comp (ref "IR_R44")
      (value "Res3")
      (footprint "J1-0603")
      (description "IR Emitter Resistor")
      (fields (field (name "ALTIUM_VALUE") "47") (field (name "PUBLISHER") "Altium Limited"))
      (libsource (lib "Miscellaneous Devices") (part "Res3"))
    )
    (comp (ref "IR_R45")
      (value "Res3")
      (footprint "J1-0603")
      (description "IR Emitter Resistor")
      (fields (field (name "ALTIUM_VALUE") "47") (field (name "PUBLISHER") "Altium Limited"))
      (libsource (lib "Miscellaneous Devices") (part "Res3"))
    )
    (comp (ref "IR_R46")
      (value "Res3")
      (footprint "J1-0603")
      (description "IR Emitter Resistor")
      (fields (field (name "ALTIUM_VALUE") "47") (field (name "PUBLISHER") "Altium Limited"))
      (libsource (lib "Miscellaneous Devices") (part "Res3"))
    )
    (comp (ref "IR_R47")
      (value "Res3")
      (footprint "J1-0603")
      (description "IR Emitter Resistor")
      (fields (field (name "ALTIUM_VALUE") "47") (field (name "PUBLISHER") "Altium Limited"))
      (libsource (lib "Miscellaneous Devices") (part "Res3"))
    )
    (comp (ref "IR_R48")
      (value "Res3")
      (footprint "J1-0603")
      (description "IR Emitter Resistor")
      (fields (field (name "ALTIUM_VALUE") "47") (field (name "PUBLISHER") "Altium Limited"))
      (libsource (lib "Miscellaneous Devices") (part "Res3"))
    )
    (comp (ref "IR_R49")
      (value "Res3")
      (footprint "J1-0603")
      (description "IR Emitter Resistor")
      (fields (field (name "ALTIUM_VALUE") "47") (field (name "PUBLISHER") "Altium Limited"))
      (libsource (lib "Miscellaneous Devices") (part "Res3"))
    )
    (comp (ref "IR_R50")
      (value "Res3")
      (footprint "J1-0603")
      (description "IR Emitter Resistor")
      (fields (field (name "ALTIUM_VALUE") "47") (field (name "PUBLISHER") "Altium Limited"))
      (libsource (lib "Miscellaneous Devices") (part "Res3"))
    )
    (comp (ref "IR_R51")
      (value "Res3")
      (footprint "J1-0603")
      (description "IR Emitter Resistor")
      (fields (field (name "ALTIUM_VALUE") "47") (field (name "PUBLISHER") "Altium Limited"))
      (libsource (lib "Miscellaneous Devices") (part "Res3"))
    )
    (comp (ref "IR_R52")
      (value "Res3")
      (footprint "J1-0603")
      (description "IR Emitter Resistor")
      (fields (field (name "ALTIUM_VALUE") "47") (field (name "PUBLISHER") "Altium Limited"))
      (libsource (lib "Miscellaneous Devices") (part "Res3"))
    )
    (comp (ref "IR_R53")
      (value "Res3")
      (footprint "J1-0603")
      (description "IR Emitter Resistor")
      (fields (field (name "ALTIUM_VALUE") "47") (field (name "PUBLISHER") "Altium Limited"))
      (libsource (lib "Miscellaneous Devices") (part "Res3"))
    )
    (comp (ref "IR_R54")
      (value "Res3")
      (footprint "J1-0603")
      (description "IR Emitter Resistor")
      (fields (field (name "ALTIUM_VALUE") "47") (field (name "PUBLISHER") "Altium Limited"))
      (libsource (lib "Miscellaneous Devices") (part "Res3"))
    )
    (comp (ref "IR_R55")
      (value "Res3")
      (footprint "J1-0603")
      (description "IR Emitter Resistor")
      (fields (field (name "ALTIUM_VALUE") "47") (field (name "PUBLISHER") "Altium Limited"))
      (libsource (lib "Miscellaneous Devices") (part "Res3"))
    )
    (comp (ref "IR_R56")
      (value "Res3")
      (footprint "J1-0603")
      (description "IR Emitter Resistor")
      (fields (field (name "ALTIUM_VALUE") "47") (field (name "PUBLISHER") "Altium Limited"))
      (libsource (lib "Miscellaneous Devices") (part "Res3"))
    )
    (comp (ref "IR_R57")
      (value "Res3")
      (footprint "J1-0603")
      (description "IR Emitter Resistor")
      (fields (field (name "ALTIUM_VALUE") "47") (field (name "PUBLISHER") "Altium Limited"))
      (libsource (lib "Miscellaneous Devices") (part "Res3"))
    )
    (comp (ref "IR_R58")
      (value "Res3")
      (footprint "J1-0603")
      (description "IR Emitter Resistor")
      (fields (field (name "ALTIUM_VALUE") "47") (field (name "PUBLISHER") "Altium Limited"))
      (libsource (lib "Miscellaneous Devices") (part "Res3"))
    )
    (comp (ref "IR_R59")
      (value "Res3")
      (footprint "J1-0603")
      (description "IR Emitter Resistor")
      (fields (field (name "ALTIUM_VALUE") "47") (field (name "PUBLISHER") "Altium Limited"))
      (libsource (lib "Miscellaneous Devices") (part "Res3"))
    )
    (comp (ref "IR_R60")
      (value "Res3")
      (footprint "J1-0603")
      (description "IR Emitter Resistor")
      (fields (field (name "ALTIUM_VALUE") "47") (field (name "PUBLISHER") "Altium Limited"))
      (libsource (lib "Miscellaneous Devices") (part "Res3"))
    )
    (comp (ref "IR_R61")
      (value "Res3")
      (footprint "J1-0603")
      (description "IR Emitter Resistor")
      (fields (field (name "ALTIUM_VALUE") "47") (field (name "PUBLISHER") "Altium Limited"))
      (libsource (lib "Miscellaneous Devices") (part "Res3"))
    )
    (comp (ref "IR_R62")
      (value "Res3")
      (footprint "J1-0603")
      (description "IR Emitter Resistor")
      (fields (field (name "ALTIUM_VALUE") "47") (field (name "PUBLISHER") "Altium Limited"))
      (libsource (lib "Miscellaneous Devices") (part "Res3"))
    )
    (comp (ref "IR_R63")
      (value "Res3")
      (footprint "J1-0603")
      (description "IR Emitter Resistor")
      (fields (field (name "ALTIUM_VALUE") "47") (field (name "PUBLISHER") "Altium Limited"))
      (libsource (lib "Miscellaneous Devices") (part "Res3"))
    )
    (comp (ref "IR_R64")
      (value "Res3")
      (footprint "J1-0603")
      (description "IR Emitter Resistor")
      (fields (field (name "ALTIUM_VALUE") "47") (field (name "PUBLISHER") "Altium Limited"))
      (libsource (lib "Miscellaneous Devices") (part "Res3"))
    )
    (comp (ref "LED1")
      (value "APA102-2020")
      (footprint "SON75P200X200X100-6N")
      (fields
        (field (name "MANUFACTURER_PART_NUMBER") "COM-14608")
        (field (name "MOUSER_PART_NUMBER") "474-COM-14608")
      )
      (libsource (lib "COM-14608") (part "COM-14608"))
    )
    (comp (ref "LED2")
      (value "APA102-2020")
      (footprint "SON75P200X200X100-6N")
      (fields
        (field (name "MANUFACTURER_PART_NUMBER") "COM-14608")
        (field (name "MOUSER_PART_NUMBER") "474-COM-14608")
      )
      (libsource (lib "COM-14608") (part "COM-14608"))
    )
    (comp (ref "LED3")
      (value "APA102-2020")
      (footprint "SON75P200X200X100-6N")
      (fields
        (field (name "MANUFACTURER_PART_NUMBER") "COM-14608")
        (field (name "MOUSER_PART_NUMBER") "474-COM-14608")
      )
      (libsource (lib "COM-14608") (part "COM-14608"))
    )
    (comp (ref "LED4")
      (value "APA102-2020")
      (footprint "SON75P200X200X100-6N")
      (fields
        (field (name "MANUFACTURER_PART_NUMBER") "COM-14608")
        (field (name "MOUSER_PART_NUMBER") "474-COM-14608")
      )
      (libsource (lib "COM-14608") (part "COM-14608"))
    )
    (comp (ref "LED5")
      (value "APA102-2020")
      (footprint "SON75P200X200X100-6N")
      (fields
        (field (name "MANUFACTURER_PART_NUMBER") "COM-14608")
        (field (name "MOUSER_PART_NUMBER") "474-COM-14608")
      )
      (libsource (lib "COM-14608") (part "COM-14608"))
    )
    (comp (ref "LED6")
      (value "APA102-2020")
      (footprint "SON75P200X200X100-6N")
      (fields
        (field (name "MANUFACTURER_PART_NUMBER") "COM-14608")
        (field (name "MOUSER_PART_NUMBER") "474-COM-14608")
      )
      (libsource (lib "COM-14608") (part "COM-14608"))
    )
    (comp (ref "LED7")
      (value "APA102-2020")
      (footprint "SON75P200X200X100-6N")
      (fields
        (field (name "MANUFACTURER_PART_NUMBER") "COM-14608")
        (field (name "MOUSER_PART_NUMBER") "474-COM-14608")
      )
      (libsource (lib "COM-14608") (part "COM-14608"))
    )
    (comp (ref "LED8")
      (value "APA102-2020")
      (footprint "SON75P200X200X100-6N")
      (fields
        (field (name "MANUFACTURER_PART_NUMBER") "COM-14608")
        (field (name "MOUSER_PART_NUMBER") "474-COM-14608")
      )
      (libsource (lib "COM-14608") (part "COM-14608"))
    )
    (comp (ref "LED9")
      (value "APA102-2020")
      (footprint "SON75P200X200X100-6N")
      (fields
        (field (name "MANUFACTURER_PART_NUMBER") "COM-14608")
        (field (name "MOUSER_PART_NUMBER") "474-COM-14608")
      )
      (libsource (lib "COM-14608") (part "COM-14608"))
    )
    (comp (ref "LED10")
      (value "APA102-2020")
      (footprint "SON75P200X200X100-6N")
      (fields
        (field (name "MANUFACTURER_PART_NUMBER") "COM-14608")
        (field (name "MOUSER_PART_NUMBER") "474-COM-14608")
      )
      (libsource (lib "COM-14608") (part "COM-14608"))
    )
    (comp (ref "LED11")
      (value "APA102-2020")
      (footprint "SON75P200X200X100-6N")
      (fields
        (field (name "MANUFACTURER_PART_NUMBER") "COM-14608")
        (field (name "MOUSER_PART_NUMBER") "474-COM-14608")
      )
      (libsource (lib "COM-14608") (part "COM-14608"))
    )
    (comp (ref "LED12")
      (value "APA102-2020")
      (footprint "SON75P200X200X100-6N")
      (fields
        (field (name "MANUFACTURER_PART_NUMBER") "COM-14608")
        (field (name "MOUSER_PART_NUMBER") "474-COM-14608")
      )
      (libsource (lib "COM-14608") (part "COM-14608"))
    )
    (comp (ref "LED13")
      (value "APA102-2020")
      (footprint "SON75P200X200X100-6N")
      (fields
        (field (name "MANUFACTURER_PART_NUMBER") "COM-14608")
        (field (name "MOUSER_PART_NUMBER") "474-COM-14608")
      )
      (libsource (lib "COM-14608") (part "COM-14608"))
    )
    (comp (ref "LED14")
      (value "APA102-2020")
      (footprint "SON75P200X200X100-6N")
      (fields
        (field (name "MANUFACTURER_PART_NUMBER") "COM-14608")
        (field (name "MOUSER_PART_NUMBER") "474-COM-14608")
      )
      (libsource (lib "COM-14608") (part "COM-14608"))
    )
    (comp (ref "LED15")
      (value "APA102-2020")
      (footprint "SON75P200X200X100-6N")
      (fields
        (field (name "MANUFACTURER_PART_NUMBER") "COM-14608")
        (field (name "MOUSER_PART_NUMBER") "474-COM-14608")
      )
      (libsource (lib "COM-14608") (part "COM-14608"))
    )
    (comp (ref "LED16")
      (value "APA102-2020")
      (footprint "SON75P200X200X100-6N")
      (fields
        (field (name "MANUFACTURER_PART_NUMBER") "COM-14608")
        (field (name "MOUSER_PART_NUMBER") "474-COM-14608")
      )
      (libsource (lib "COM-14608") (part "COM-14608"))
    )
    (comp (ref "LED17")
      (value "APA102-2020")
      (footprint "SON75P200X200X100-6N")
      (fields
        (field (name "MANUFACTURER_PART_NUMBER") "COM-14608")
        (field (name "MOUSER_PART_NUMBER") "474-COM-14608")
      )
      (libsource (lib "COM-14608") (part "COM-14608"))
    )
    (comp (ref "LED18")
      (value "APA102-2020")
      (footprint "SON75P200X200X100-6N")
      (fields
        (field (name "MANUFACTURER_PART_NUMBER") "COM-14608")
        (field (name "MOUSER_PART_NUMBER") "474-COM-14608")
      )
      (libsource (lib "COM-14608") (part "COM-14608"))
    )
    (comp (ref "LED19")
      (value "APA102-2020")
      (footprint "SON75P200X200X100-6N")
      (fields
        (field (name "MANUFACTURER_PART_NUMBER") "COM-14608")
        (field (name "MOUSER_PART_NUMBER") "474-COM-14608")
      )
      (libsource (lib "COM-14608") (part "COM-14608"))
    )
    (comp (ref "LED20")
      (value "APA102-2020")
      (footprint "SON75P200X200X100-6N")
      (fields
        (field (name "MANUFACTURER_PART_NUMBER") "COM-14608")
        (field (name "MOUSER_PART_NUMBER") "474-COM-14608")
      )
      (libsource (lib "COM-14608") (part "COM-14608"))
    )
    (comp (ref "LED21")
      (value "APA102-2020")
      (footprint "SON75P200X200X100-6N")
      (fields
        (field (name "MANUFACTURER_PART_NUMBER") "COM-14608")
        (field (name "MOUSER_PART_NUMBER") "474-COM-14608")
      )
      (libsource (lib "COM-14608") (part "COM-14608"))
    )
    (comp (ref "LED22")
      (value "APA102-2020")
      (footprint "SON75P200X200X100-6N")
      (fields
        (field (name "MANUFACTURER_PART_NUMBER") "COM-14608")
        (field (name "MOUSER_PART_NUMBER") "474-COM-14608")
      )
      (libsource (lib "COM-14608") (part "COM-14608"))
    )
    (comp (ref "LED23")
      (value "APA102-2020")
      (footprint "SON75P200X200X100-6N")
      (fields
        (field (name "MANUFACTURER_PART_NUMBER") "COM-14608")
        (field (name "MOUSER_PART_NUMBER") "474-COM-14608")
      )
      (libsource (lib "COM-14608") (part "COM-14608"))
    )
    (comp (ref "LED24")
      (value "APA102-2020")
      (footprint "SON75P200X200X100-6N")
      (fields
        (field (name "MANUFACTURER_PART_NUMBER") "COM-14608")
        (field (name "MOUSER_PART_NUMBER") "474-COM-14608")
      )
      (libsource (lib "COM-14608") (part "COM-14608"))
    )
    (comp (ref "LED25")
      (value "APA102-2020")
      (footprint "SON75P200X200X100-6N")
      (fields
        (field (name "MANUFACTURER_PART_NUMBER") "COM-14608")
        (field (name "MOUSER_PART_NUMBER") "474-COM-14608")
      )
      (libsource (lib "COM-14608") (part "COM-14608"))
    )
    (comp (ref "LED26")
      (value "APA102-2020")
      (footprint "SON75P200X200X100-6N")
      (fields
        (field (name "MANUFACTURER_PART_NUMBER") "COM-14608")
        (field (name "MOUSER_PART_NUMBER") "474-COM-14608")
      )
      (libsource (lib "COM-14608") (part "COM-14608"))
    )
    (comp (ref "LED27")
      (value "APA102-2020")
      (footprint "SON75P200X200X100-6N")
      (fields
        (field (name "MANUFACTURER_PART_NUMBER") "COM-14608")
        (field (name "MOUSER_PART_NUMBER") "474-COM-14608")
      )
      (libsource (lib "COM-14608") (part "COM-14608"))
    )
    (comp (ref "LED28")
      (value "APA102-2020")
      (footprint "SON75P200X200X100-6N")
      (fields
        (field (name "MANUFACTURER_PART_NUMBER") "COM-14608")
        (field (name "MOUSER_PART_NUMBER") "474-COM-14608")
      )
      (libsource (lib "COM-14608") (part "COM-14608"))
    )
    (comp (ref "LED29")
      (value "APA102-2020")
      (footprint "SON75P200X200X100-6N")
      (fields
        (field (name "MANUFACTURER_PART_NUMBER") "COM-14608")
        (field (name "MOUSER_PART_NUMBER") "474-COM-14608")
      )
      (libsource (lib "COM-14608") (part "COM-14608"))
    )
    (comp (ref "LED30")
      (value "APA102-2020")
      (footprint "SON75P200X200X100-6N")
      (fields
        (field (name "MANUFACTURER_PART_NUMBER") "COM-14608")
        (field (name "MOUSER_PART_NUMBER") "474-COM-14608")
      )
      (libsource (lib "COM-14608") (part "COM-14608"))
    )
    (comp (ref "LED31")
      (value "APA102-2020")
      (footprint "SON75P200X200X100-6N")
      (fields
        (field (name "MANUFACTURER_PART_NUMBER") "COM-14608")
        (field (name "MOUSER_PART_NUMBER") "474-COM-14608")
      )
      (libsource (lib "COM-14608") (part "COM-14608"))
    )
    (comp (ref "LED32")
      (value "APA102-2020")
      (footprint "SON75P200X200X100-6N")
      (fields
        (field (name "MANUFACTURER_PART_NUMBER") "COM-14608")
        (field (name "MOUSER_PART_NUMBER") "474-COM-14608")
      )
      (libsource (lib "COM-14608") (part "COM-14608"))
    )
    (comp (ref "LED33")
      (value "APA102-2020")
      (footprint "SON75P200X200X100-6N")
      (fields
        (field (name "MANUFACTURER_PART_NUMBER") "COM-14608")
        (field (name "MOUSER_PART_NUMBER") "474-COM-14608")
      )
      (libsource (lib "COM-14608") (part "COM-14608"))
    )
    (comp (ref "LED34")
      (value "APA102-2020")
      (footprint "SON75P200X200X100-6N")
      (fields
        (field (name "MANUFACTURER_PART_NUMBER") "COM-14608")
        (field (name "MOUSER_PART_NUMBER") "474-COM-14608")
      )
      (libsource (lib "COM-14608") (part "COM-14608"))
    )
    (comp (ref "LED35")
      (value "APA102-2020")
      (footprint "SON75P200X200X100-6N")
      (fields
        (field (name "MANUFACTURER_PART_NUMBER") "COM-14608")
        (field (name "MOUSER_PART_NUMBER") "474-COM-14608")
      )
      (libsource (lib "COM-14608") (part "COM-14608"))
    )
    (comp (ref "LED36")
      (value "APA102-2020")
      (footprint "SON75P200X200X100-6N")
      (fields
        (field (name "MANUFACTURER_PART_NUMBER") "COM-14608")
        (field (name "MOUSER_PART_NUMBER") "474-COM-14608")
      )
      (libsource (lib "COM-14608") (part "COM-14608"))
    )
    (comp (ref "LED37")
      (value "APA102-2020")
      (footprint "SON75P200X200X100-6N")
      (fields
        (field (name "MANUFACTURER_PART_NUMBER") "COM-14608")
        (field (name "MOUSER_PART_NUMBER") "474-COM-14608")
      )
      (libsource (lib "COM-14608") (part "COM-14608"))
    )
    (comp (ref "LED38")
      (value "APA102-2020")
      (footprint "SON75P200X200X100-6N")
      (fields
        (field (name "MANUFACTURER_PART_NUMBER") "COM-14608")
        (field (name "MOUSER_PART_NUMBER") "474-COM-14608")
      )
      (libsource (lib "COM-14608") (part "COM-14608"))
    )
    (comp (ref "LED39")
      (value "APA102-2020")
      (footprint "SON75P200X200X100-6N")
      (fields
        (field (name "MANUFACTURER_PART_NUMBER") "COM-14608")
        (field (name "MOUSER_PART_NUMBER") "474-COM-14608")
      )
      (libsource (lib "COM-14608") (part "COM-14608"))
    )
    (comp (ref "LED40")
      (value "APA102-2020")
      (footprint "SON75P200X200X100-6N")
      (fields
        (field (name "MANUFACTURER_PART_NUMBER") "COM-14608")
        (field (name "MOUSER_PART_NUMBER") "474-COM-14608")
      )
      (libsource (lib "COM-14608") (part "COM-14608"))
    )
    (comp (ref "LED41")
      (value "APA102-2020")
      (footprint "SON75P200X200X100-6N")
      (fields
        (field (name "MANUFACTURER_PART_NUMBER") "COM-14608")
        (field (name "MOUSER_PART_NUMBER") "474-COM-14608")
      )
      (libsource (lib "COM-14608") (part "COM-14608"))
    )
    (comp (ref "LED42")
      (value "APA102-2020")
      (footprint "SON75P200X200X100-6N")
      (fields
        (field (name "MANUFACTURER_PART_NUMBER") "COM-14608")
        (field (name "MOUSER_PART_NUMBER") "474-COM-14608")
      )
      (libsource (lib "COM-14608") (part "COM-14608"))
    )
    (comp (ref "LED43")
      (value "APA102-2020")
      (footprint "SON75P200X200X100-6N")
      (fields
        (field (name "MANUFACTURER_PART_NUMBER") "COM-14608")
        (field (name "MOUSER_PART_NUMBER") "474-COM-14608")
      )
      (libsource (lib "COM-14608") (part "COM-14608"))
    )
    (comp (ref "LED44")
      (value "APA102-2020")
      (footprint "SON75P200X200X100-6N")
      (fields
        (field (name "MANUFACTURER_PART_NUMBER") "COM-14608")
        (field (name "MOUSER_PART_NUMBER") "474-COM-14608")
      )
      (libsource (lib "COM-14608") (part "COM-14608"))
    )
    (comp (ref "LED45")
      (value "APA102-2020")
      (footprint "SON75P200X200X100-6N")
      (fields
        (field (name "MANUFACTURER_PART_NUMBER") "COM-14608")
        (field (name "MOUSER_PART_NUMBER") "474-COM-14608")
      )
      (libsource (lib "COM-14608") (part "COM-14608"))
    )
    (comp (ref "LED46")
      (value "APA102-2020")
      (footprint "SON75P200X200X100-6N")
      (fields
        (field (name "MANUFACTURER_PART_NUMBER") "COM-14608")
        (field (name "MOUSER_PART_NUMBER") "474-COM-14608")
      )
      (libsource (lib "COM-14608") (part "COM-14608"))
    )
    (comp (ref "LED47")
      (value "APA102-2020")
      (footprint "SON75P200X200X100-6N")
      (fields
        (field (name "MANUFACTURER_PART_NUMBER") "COM-14608")
        (field (name "MOUSER_PART_NUMBER") "474-COM-14608")
      )
      (libsource (lib "COM-14608") (part "COM-14608"))
    )
    (comp (ref "LED48")
      (value "APA102-2020")
      (footprint "SON75P200X200X100-6N")
      (fields
        (field (name "MANUFACTURER_PART_NUMBER") "COM-14608")
        (field (name "MOUSER_PART_NUMBER") "474-COM-14608")
      )
      (libsource (lib "COM-14608") (part "COM-14608"))
    )
    (comp (ref "LED49")
      (value "APA102-2020")
      (footprint "SON75P200X200X100-6N")
      (fields
        (field (name "MANUFACTURER_PART_NUMBER") "COM-14608")
        (field (name "MOUSER_PART_NUMBER") "474-COM-14608")
      )
      (libsource (lib "COM-14608") (part "COM-14608"))
    )
    (comp (ref "LED50")
      (value "APA102-2020")
      (footprint "SON75P200X200X100-6N")
      (fields
        (field (name "MANUFACTURER_PART_NUMBER") "COM-14608")
        (field (name "MOUSER_PART_NUMBER") "474-COM-14608")
      )
      (libsource (lib "COM-14608") (part "COM-14608"))
    )
    (comp (ref "LED51")
      (value "APA102-2020")
      (footprint "SON75P200X200X100-6N")
      (fields
        (field (name "MANUFACTURER_PART_NUMBER") "COM-14608")
        (field (name "MOUSER_PART_NUMBER") "474-COM-14608")
      )
      (libsource (lib "COM-14608") (part "COM-14608"))
    )
    (comp (ref "LED52")
      (value "APA102-2020")
      (footprint "SON75P200X200X100-6N")
      (fields
        (field (name "MANUFACTURER_PART_NUMBER") "COM-14608")
        (field (name "MOUSER_PART_NUMBER") "474-COM-14608")
      )
      (libsource (lib "COM-14608") (part "COM-14608"))
    )
    (comp (ref "LED53")
      (value "APA102-2020")
      (footprint "SON75P200X200X100-6N")
      (fields
        (field (name "MANUFACTURER_PART_NUMBER") "COM-14608")
        (field (name "MOUSER_PART_NUMBER") "474-COM-14608")
      )
      (libsource (lib "COM-14608") (part "COM-14608"))
    )
    (comp (ref "LED54")
      (value "APA102-2020")
      (footprint "SON75P200X200X100-6N")
      (fields
        (field (name "MANUFACTURER_PART_NUMBER") "COM-14608")
        (field (name "MOUSER_PART_NUMBER") "474-COM-14608")
      )
      (libsource (lib "COM-14608") (part "COM-14608"))
    )
    (comp (ref "LED55")
      (value "APA102-2020")
      (footprint "SON75P200X200X100-6N")
      (fields
        (field (name "MANUFACTURER_PART_NUMBER") "COM-14608")
        (field (name "MOUSER_PART_NUMBER") "474-COM-14608")
      )
      (libsource (lib "COM-14608") (part "COM-14608"))
    )
    (comp (ref "LED56")
      (value "APA102-2020")
      (footprint "SON75P200X200X100-6N")
      (fields
        (field (name "MANUFACTURER_PART_NUMBER") "COM-14608")
        (field (name "MOUSER_PART_NUMBER") "474-COM-14608")
      )
      (libsource (lib "COM-14608") (part "COM-14608"))
    )
    (comp (ref "LED57")
      (value "APA102-2020")
      (footprint "SON75P200X200X100-6N")
      (fields
        (field (name "MANUFACTURER_PART_NUMBER") "COM-14608")
        (field (name "MOUSER_PART_NUMBER") "474-COM-14608")
      )
      (libsource (lib "COM-14608") (part "COM-14608"))
    )
    (comp (ref "LED58")
      (value "APA102-2020")
      (footprint "SON75P200X200X100-6N")
      (fields
        (field (name "MANUFACTURER_PART_NUMBER") "COM-14608")
        (field (name "MOUSER_PART_NUMBER") "474-COM-14608")
      )
      (libsource (lib "COM-14608") (part "COM-14608"))
    )
    (comp (ref "LED59")
      (value "APA102-2020")
      (footprint "SON75P200X200X100-6N")
      (fields
        (field (name "MANUFACTURER_PART_NUMBER") "COM-14608")
        (field (name "MOUSER_PART_NUMBER") "474-COM-14608")
      )
      (libsource (lib "COM-14608") (part "COM-14608"))
    )
    (comp (ref "LED60")
      (value "APA102-2020")
      (footprint "SON75P200X200X100-6N")
      (fields
        (field (name "MANUFACTURER_PART_NUMBER") "COM-14608")
        (field (name "MOUSER_PART_NUMBER") "474-COM-14608")
      )
      (libsource (lib "COM-14608") (part "COM-14608"))
    )
    (comp (ref "LED61")
      (value "APA102-2020")
      (footprint "SON75P200X200X100-6N")
      (fields
        (field (name "MANUFACTURER_PART_NUMBER") "COM-14608")
        (field (name "MOUSER_PART_NUMBER") "474-COM-14608")
      )
      (libsource (lib "COM-14608") (part "COM-14608"))
    )
    (comp (ref "LED62")
      (value "APA102-2020")
      (footprint "SON75P200X200X100-6N")
      (fields
        (field (name "MANUFACTURER_PART_NUMBER") "COM-14608")
        (field (name "MOUSER_PART_NUMBER") "474-COM-14608")
      )
      (libsource (lib "COM-14608") (part "COM-14608"))
    )
    (comp (ref "LED63")
      (value "APA102-2020")
      (footprint "SON75P200X200X100-6N")
      (fields
        (field (name "MANUFACTURER_PART_NUMBER") "COM-14608")
        (field (name "MOUSER_PART_NUMBER") "474-COM-14608")
      )
      (libsource (lib "COM-14608") (part "COM-14608"))
    )
    (comp (ref "LED64")
      (value "APA102-2020")
      (footprint "SON75P200X200X100-6N")
      (fields
        (field (name "MANUFACTURER_PART_NUMBER") "COM-14608")
        (field (name "MOUSER_PART_NUMBER") "474-COM-14608")
      )
      (libsource (lib "COM-14608") (part "COM-14608"))
    )
    (comp (ref "MOSN0")
      (value "MOSFET 12V N-Ch Enh FET 2426pF 27.3nC   Source:  Datasheet")
      (footprint "SOT95P285X130-3N")
      (fields
        (field (name "MANUFACTURER_PART_NUMBER") "DMN1019USN-7")
        (field (name "RS_PART_NUMBER") "1658326")
        (field (name "MOUSER_PART_NUMBER") "621-DMN1019USN-7")
      )
      (libsource (lib "DMN1019USN-7") (part "DMN1019USN-7"))
    )
    (comp (ref "MOSN1")
      (value "MOSFET 12V N-Ch Enh FET 2426pF 27.3nC   Source:  Datasheet")
      (footprint "SOT95P285X130-3N")
      (fields
        (field (name "MANUFACTURER_PART_NUMBER") "DMN1019USN-7")
        (field (name "RS_PART_NUMBER") "1658326")
        (field (name "MOUSER_PART_NUMBER") "621-DMN1019USN-7")
      )
      (libsource (lib "DMN1019USN-7") (part "DMN1019USN-7"))
    )
    (comp (ref "MOSN2")
      (value "MOSFET 12V N-Ch Enh FET 2426pF 27.3nC   Source:  Datasheet")
      (footprint "SOT95P285X130-3N")
      (fields
        (field (name "MANUFACTURER_PART_NUMBER") "DMN1019USN-7")
        (field (name "RS_PART_NUMBER") "1658326")
        (field (name "MOUSER_PART_NUMBER") "621-DMN1019USN-7")
      )
      (libsource (lib "DMN1019USN-7") (part "DMN1019USN-7"))
    )
    (comp (ref "MOSN3")
      (value "MOSFET 12V N-Ch Enh FET 2426pF 27.3nC   Source:  Datasheet")
      (footprint "SOT95P285X130-3N")
      (fields
        (field (name "MANUFACTURER_PART_NUMBER") "DMN1019USN-7")
        (field (name "RS_PART_NUMBER") "1658326")
        (field (name "MOUSER_PART_NUMBER") "621-DMN1019USN-7")
      )
      (libsource (lib "DMN1019USN-7") (part "DMN1019USN-7"))
    )
    (comp (ref "MOSN4")
      (value "MOSFET 12V N-Ch Enh FET 2426pF 27.3nC   Source:  Datasheet")
      (footprint "SOT95P285X130-3N")
      (fields
        (field (name "MANUFACTURER_PART_NUMBER") "DMN1019USN-7")
        (field (name "RS_PART_NUMBER") "1658326")
        (field (name "MOUSER_PART_NUMBER") "621-DMN1019USN-7")
      )
      (libsource (lib "DMN1019USN-7") (part "DMN1019USN-7"))
    )
    (comp (ref "MOSN5")
      (value "MOSFET 12V N-Ch Enh FET 2426pF 27.3nC   Source:  Datasheet")
      (footprint "SOT95P285X130-3N")
      (fields
        (field (name "MANUFACTURER_PART_NUMBER") "DMN1019USN-7")
        (field (name "RS_PART_NUMBER") "1658326")
        (field (name "MOUSER_PART_NUMBER") "621-DMN1019USN-7")
      )
      (libsource (lib "DMN1019USN-7") (part "DMN1019USN-7"))
    )
    (comp (ref "MOSN6")
      (value "MOSFET 12V N-Ch Enh FET 2426pF 27.3nC   Source:  Datasheet")
      (footprint "SOT95P285X130-3N")
      (fields
        (field (name "MANUFACTURER_PART_NUMBER") "DMN1019USN-7")
        (field (name "RS_PART_NUMBER") "1658326")
        (field (name "MOUSER_PART_NUMBER") "621-DMN1019USN-7")
      )
      (libsource (lib "DMN1019USN-7") (part "DMN1019USN-7"))
    )
    (comp (ref "MOSN7")
      (value "MOSFET 12V N-Ch Enh FET 2426pF 27.3nC   Source:  Datasheet")
      (footprint "SOT95P285X130-3N")
      (fields
        (field (name "MANUFACTURER_PART_NUMBER") "DMN1019USN-7")
        (field (name "RS_PART_NUMBER") "1658326")
        (field (name "MOUSER_PART_NUMBER") "621-DMN1019USN-7")
      )
      (libsource (lib "DMN1019USN-7") (part "DMN1019USN-7"))
    )
    (comp (ref "MOSP0")
      (value "Power MOSFET   Source:  Datasheet")
      (footprint "SOT65P220X100-3N")
      (fields
        (field (name "MANUFACTURER_PART_NUMBER") "NTS2101PT1G")
        (field (name "RS_PART_NUMBER") "1631139")
        (field (name "MOUSER_PART_NUMBER") "863-NTS2101PT1G")
      )
      (libsource (lib "NTS2101PT1G") (part "NTS2101PT1G"))
    )
    (comp (ref "MOSP1")
      (value "Power MOSFET   Source:  Datasheet")
      (footprint "SOT65P220X100-3N")
      (fields
        (field (name "MANUFACTURER_PART_NUMBER") "NTS2101PT1G")
        (field (name "RS_PART_NUMBER") "1631139")
        (field (name "MOUSER_PART_NUMBER") "863-NTS2101PT1G")
      )
      (libsource (lib "NTS2101PT1G") (part "NTS2101PT1G"))
    )
    (comp (ref "MOSP2")
      (value "Power MOSFET   Source:  Datasheet")
      (footprint "SOT65P220X100-3N")
      (fields
        (field (name "MANUFACTURER_PART_NUMBER") "NTS2101PT1G")
        (field (name "RS_PART_NUMBER") "1631139")
        (field (name "MOUSER_PART_NUMBER") "863-NTS2101PT1G")
      )
      (libsource (lib "NTS2101PT1G") (part "NTS2101PT1G"))
    )
    (comp (ref "MOSP3")
      (value "Power MOSFET   Source:  Datasheet")
      (footprint "SOT65P220X100-3N")
      (fields
        (field (name "MANUFACTURER_PART_NUMBER") "NTS2101PT1G")
        (field (name "RS_PART_NUMBER") "1631139")
        (field (name "MOUSER_PART_NUMBER") "863-NTS2101PT1G")
      )
      (libsource (lib "NTS2101PT1G") (part "NTS2101PT1G"))
    )
    (comp (ref "MOSP4")
      (value "Power MOSFET   Source:  Datasheet")
      (footprint "SOT65P220X100-3N")
      (fields
        (field (name "MANUFACTURER_PART_NUMBER") "NTS2101PT1G")
        (field (name "RS_PART_NUMBER") "1631139")
        (field (name "MOUSER_PART_NUMBER") "863-NTS2101PT1G")
      )
      (libsource (lib "NTS2101PT1G") (part "NTS2101PT1G"))
    )
    (comp (ref "MOSP5")
      (value "Power MOSFET   Source:  Datasheet")
      (footprint "SOT65P220X100-3N")
      (fields
        (field (name "MANUFACTURER_PART_NUMBER") "NTS2101PT1G")
        (field (name "RS_PART_NUMBER") "1631139")
        (field (name "MOUSER_PART_NUMBER") "863-NTS2101PT1G")
      )
      (libsource (lib "NTS2101PT1G") (part "NTS2101PT1G"))
    )
    (comp (ref "MOSP6")
      (value "Power MOSFET   Source:  Datasheet")
      (footprint "SOT65P220X100-3N")
      (fields
        (field (name "MANUFACTURER_PART_NUMBER") "NTS2101PT1G")
        (field (name "RS_PART_NUMBER") "1631139")
        (field (name "MOUSER_PART_NUMBER") "863-NTS2101PT1G")
      )
      (libsource (lib "NTS2101PT1G") (part "NTS2101PT1G"))
    )
    (comp (ref "MOSP7")
      (value "Power MOSFET   Source:  Datasheet")
      (footprint "SOT65P220X100-3N")
      (fields
        (field (name "MANUFACTURER_PART_NUMBER") "NTS2101PT1G")
        (field (name "RS_PART_NUMBER") "1631139")
        (field (name "MOUSER_PART_NUMBER") "863-NTS2101PT1G")
      )
      (libsource (lib "NTS2101PT1G") (part "NTS2101PT1G"))
    )
    (comp (ref "M_C")
      (value "8-channel analog multiplexer/demultiplexer   Source:  Datasheet")
      (footprint "SOP65P640X110-16N")
      (fields
        (field (name "MANUFACTURER_PART_NUMBER") "74HC4051PW,118")
        (field (name "RS_PART_NUMBER") "1707982")
        (field (name "MOUSER_PART_NUMBER") "771-74HC4051PW-T")
      )
      (libsource (lib "74HC4051PW_118") (part "74HC4051PW,118"))
    )
    (comp (ref "M_R")
      (value "8-channel analog multiplexer/demultiplexer   Source:  Datasheet")
      (footprint "SOP65P640X110-16N")
      (fields
        (field (name "MANUFACTURER_PART_NUMBER") "74HC4051PW,118")
        (field (name "RS_PART_NUMBER") "1707982")
        (field (name "MOUSER_PART_NUMBER") "771-74HC4051PW-T")
      )
      (libsource (lib "74HC4051PW_118") (part "74HC4051PW,118"))
    )
    (comp (ref "PT1")
      (value "PT26-51B")
      (footprint "VEMT2020X01")
      (libsource (lib "T25_Components") (part "PT26-51B"))
    )
    (comp (ref "PT2")
      (value "PT26-51B")
      (footprint "VEMT2020X01")
      (libsource (lib "T25_Components") (part "PT26-51B"))
    )
    (comp (ref "PT3")
      (value "PT26-51B")
      (footprint "VEMT2020X01")
      (libsource (lib "T25_Components") (part "PT26-51B"))
    )
    (comp (ref "PT4")
      (value "PT26-51B")
      (footprint "VEMT2020X01")
      (libsource (lib "T25_Components") (part "PT26-51B"))
    )
    (comp (ref "PT5")
      (value "PT26-51B")
      (footprint "VEMT2020X01")
      (libsource (lib "T25_Components") (part "PT26-51B"))
    )
    (comp (ref "PT6")
      (value "PT26-51B")
      (footprint "VEMT2020X01")
      (libsource (lib "T25_Components") (part "PT26-51B"))
    )
    (comp (ref "PT7")
      (value "PT26-51B")
      (footprint "VEMT2020X01")
      (libsource (lib "T25_Components") (part "PT26-51B"))
    )
    (comp (ref "PT8")
      (value "PT26-51B")
      (footprint "VEMT2020X01")
      (libsource (lib "T25_Components") (part "PT26-51B"))
    )
    (comp (ref "PT9")
      (value "PT26-51B")
      (footprint "VEMT2020X01")
      (libsource (lib "T25_Components") (part "PT26-51B"))
    )
    (comp (ref "PT10")
      (value "PT26-51B")
      (footprint "VEMT2020X01")
      (libsource (lib "T25_Components") (part "PT26-51B"))
    )
    (comp (ref "PT11")
      (value "PT26-51B")
      (footprint "VEMT2020X01")
      (libsource (lib "T25_Components") (part "PT26-51B"))
    )
    (comp (ref "PT12")
      (value "PT26-51B")
      (footprint "VEMT2020X01")
      (libsource (lib "T25_Components") (part "PT26-51B"))
    )
    (comp (ref "PT13")
      (value "PT26-51B")
      (footprint "VEMT2020X01")
      (libsource (lib "T25_Components") (part "PT26-51B"))
    )
    (comp (ref "PT14")
      (value "PT26-51B")
      (footprint "VEMT2020X01")
      (libsource (lib "T25_Components") (part "PT26-51B"))
    )
    (comp (ref "PT15")
      (value "PT26-51B")
      (footprint "VEMT2020X01")
      (libsource (lib "T25_Components") (part "PT26-51B"))
    )
    (comp (ref "PT16")
      (value "PT26-51B")
      (footprint "VEMT2020X01")
      (libsource (lib "T25_Components") (part "PT26-51B"))
    )
    (comp (ref "PT17")
      (value "PT26-51B")
      (footprint "VEMT2020X01")
      (libsource (lib "T25_Components") (part "PT26-51B"))
    )
    (comp (ref "PT18")
      (value "PT26-51B")
      (footprint "VEMT2020X01")
      (libsource (lib "T25_Components") (part "PT26-51B"))
    )
    (comp (ref "PT19")
      (value "PT26-51B")
      (footprint "VEMT2020X01")
      (libsource (lib "T25_Components") (part "PT26-51B"))
    )
    (comp (ref "PT20")
      (value "PT26-51B")
      (footprint "VEMT2020X01")
      (libsource (lib "T25_Components") (part "PT26-51B"))
    )
    (comp (ref "PT21")
      (value "PT26-51B")
      (footprint "VEMT2020X01")
      (libsource (lib "T25_Components") (part "PT26-51B"))
    )
    (comp (ref "PT22")
      (value "PT26-51B")
      (footprint "VEMT2020X01")
      (libsource (lib "T25_Components") (part "PT26-51B"))
    )
    (comp (ref "PT23")
      (value "PT26-51B")
      (footprint "VEMT2020X01")
      (libsource (lib "T25_Components") (part "PT26-51B"))
    )
    (comp (ref "PT24")
      (value "PT26-51B")
      (footprint "VEMT2020X01")
      (libsource (lib "T25_Components") (part "PT26-51B"))
    )
    (comp (ref "PT25")
      (value "PT26-51B")
      (footprint "VEMT2020X01")
      (libsource (lib "T25_Components") (part "PT26-51B"))
    )
    (comp (ref "PT26")
      (value "PT26-51B")
      (footprint "VEMT2020X01")
      (libsource (lib "T25_Components") (part "PT26-51B"))
    )
    (comp (ref "PT27")
      (value "PT26-51B")
      (footprint "VEMT2020X01")
      (libsource (lib "T25_Components") (part "PT26-51B"))
    )
    (comp (ref "PT28")
      (value "PT26-51B")
      (footprint "VEMT2020X01")
      (libsource (lib "T25_Components") (part "PT26-51B"))
    )
    (comp (ref "PT29")
      (value "PT26-51B")
      (footprint "VEMT2020X01")
      (libsource (lib "T25_Components") (part "PT26-51B"))
    )
    (comp (ref "PT30")
      (value "PT26-51B")
      (footprint "VEMT2020X01")
      (libsource (lib "T25_Components") (part "PT26-51B"))
    )
    (comp (ref "PT31")
      (value "PT26-51B")
      (footprint "VEMT2020X01")
      (libsource (lib "T25_Components") (part "PT26-51B"))
    )
    (comp (ref "PT32")
      (value "PT26-51B")
      (footprint "VEMT2020X01")
      (libsource (lib "T25_Components") (part "PT26-51B"))
    )
    (comp (ref "PT33")
      (value "PT26-51B")
      (footprint "VEMT2020X01")
      (libsource (lib "T25_Components") (part "PT26-51B"))
    )
    (comp (ref "PT34")
      (value "PT26-51B")
      (footprint "VEMT2020X01")
      (libsource (lib "T25_Components") (part "PT26-51B"))
    )
    (comp (ref "PT35")
      (value "PT26-51B")
      (footprint "VEMT2020X01")
      (libsource (lib "T25_Components") (part "PT26-51B"))
    )
    (comp (ref "PT36")
      (value "PT26-51B")
      (footprint "VEMT2020X01")
      (libsource (lib "T25_Components") (part "PT26-51B"))
    )
    (comp (ref "PT37")
      (value "PT26-51B")
      (footprint "VEMT2020X01")
      (libsource (lib "T25_Components") (part "PT26-51B"))
    )
    (comp (ref "PT38")
      (value "PT26-51B")
      (footprint "VEMT2020X01")
      (libsource (lib "T25_Components") (part "PT26-51B"))
    )
    (comp (ref "PT39")
      (value "PT26-51B")
      (footprint "VEMT2020X01")
      (libsource (lib "T25_Components") (part "PT26-51B"))
    )
    (comp (ref "PT40")
      (value "PT26-51B")
      (footprint "VEMT2020X01")
      (libsource (lib "T25_Components") (part "PT26-51B"))
    )
    (comp (ref "PT41")
      (value "PT26-51B")
      (footprint "VEMT2020X01")
      (libsource (lib "T25_Components") (part "PT26-51B"))
    )
    (comp (ref "PT42")
      (value "PT26-51B")
      (footprint "VEMT2020X01")
      (libsource (lib "T25_Components") (part "PT26-51B"))
    )
    (comp (ref "PT43")
      (value "PT26-51B")
      (footprint "VEMT2020X01")
      (libsource (lib "T25_Components") (part "PT26-51B"))
    )
    (comp (ref "PT44")
      (value "PT26-51B")
      (footprint "VEMT2020X01")
      (libsource (lib "T25_Components") (part "PT26-51B"))
    )
    (comp (ref "PT45")
      (value "PT26-51B")
      (footprint "VEMT2020X01")
      (libsource (lib "T25_Components") (part "PT26-51B"))
    )
    (comp (ref "PT46")
      (value "PT26-51B")
      (footprint "VEMT2020X01")
      (libsource (lib "T25_Components") (part "PT26-51B"))
    )
    (comp (ref "PT47")
      (value "PT26-51B")
      (footprint "VEMT2020X01")
      (libsource (lib "T25_Components") (part "PT26-51B"))
    )
    (comp (ref "PT48")
      (value "PT26-51B")
      (footprint "VEMT2020X01")
      (libsource (lib "T25_Components") (part "PT26-51B"))
    )
    (comp (ref "PT49")
      (value "PT26-51B")
      (footprint "VEMT2020X01")
      (libsource (lib "T25_Components") (part "PT26-51B"))
    )
    (comp (ref "PT50")
      (value "PT26-51B")
      (footprint "VEMT2020X01")
      (libsource (lib "T25_Components") (part "PT26-51B"))
    )
    (comp (ref "PT51")
      (value "PT26-51B")
      (footprint "VEMT2020X01")
      (libsource (lib "T25_Components") (part "PT26-51B"))
    )
    (comp (ref "PT52")
      (value "PT26-51B")
      (footprint "VEMT2020X01")
      (libsource (lib "T25_Components") (part "PT26-51B"))
    )
    (comp (ref "PT53")
      (value "PT26-51B")
      (footprint "VEMT2020X01")
      (libsource (lib "T25_Components") (part "PT26-51B"))
    )
    (comp (ref "PT54")
      (value "PT26-51B")
      (footprint "VEMT2020X01")
      (libsource (lib "T25_Components") (part "PT26-51B"))
    )
    (comp (ref "PT55")
      (value "PT26-51B")
      (footprint "VEMT2020X01")
      (libsource (lib "T25_Components") (part "PT26-51B"))
    )
    (comp (ref "PT56")
      (value "PT26-51B")
      (footprint "VEMT2020X01")
      (libsource (lib "T25_Components") (part "PT26-51B"))
    )
    (comp (ref "PT57")
      (value "PT26-51B")
      (footprint "VEMT2020X01")
      (libsource (lib "T25_Components") (part "PT26-51B"))
    )
    (comp (ref "PT58")
      (value "PT26-51B")
      (footprint "VEMT2020X01")
      (libsource (lib "T25_Components") (part "PT26-51B"))
    )
    (comp (ref "PT59")
      (value "PT26-51B")
      (footprint "VEMT2020X01")
      (libsource (lib "T25_Components") (part "PT26-51B"))
    )
    (comp (ref "PT60")
      (value "PT26-51B")
      (footprint "VEMT2020X01")
      (libsource (lib "T25_Components") (part "PT26-51B"))
    )
    (comp (ref "PT61")
      (value "PT26-51B")
      (footprint "VEMT2020X01")
      (libsource (lib "T25_Components") (part "PT26-51B"))
    )
    (comp (ref "PT62")
      (value "PT26-51B")
      (footprint "VEMT2020X01")
      (libsource (lib "T25_Components") (part "PT26-51B"))
    )
    (comp (ref "PT63")
      (value "PT26-51B")
      (footprint "VEMT2020X01")
      (libsource (lib "T25_Components") (part "PT26-51B"))
    )
    (comp (ref "PT64")
      (value "PT26-51B")
      (footprint "VEMT2020X01")
      (libsource (lib "T25_Components") (part "PT26-51B"))
    )
    (comp (ref "PT_R1")
      (value "Res3")
      (footprint "J1-0603")
      (description "Phototransitor Resistor")
      (fields (field (name "ALTIUM_VALUE") "5.6k") (field (name "PUBLISHER") "Altium Limited"))
      (libsource (lib "Miscellaneous Devices") (part "Res3"))
    )
    (comp (ref "PT_R2")
      (value "Res3")
      (footprint "J1-0603")
      (description "Phototransitor Resistor")
      (fields (field (name "ALTIUM_VALUE") "5.6k") (field (name "PUBLISHER") "Altium Limited"))
      (libsource (lib "Miscellaneous Devices") (part "Res3"))
    )
    (comp (ref "PT_R3")
      (value "Res3")
      (footprint "J1-0603")
      (description "Phototransitor Resistor")
      (fields (field (name "ALTIUM_VALUE") "5.6k") (field (name "PUBLISHER") "Altium Limited"))
      (libsource (lib "Miscellaneous Devices") (part "Res3"))
    )
    (comp (ref "PT_R4")
      (value "Res3")
      (footprint "J1-0603")
      (description "Phototransitor Resistor")
      (fields (field (name "ALTIUM_VALUE") "5.6k") (field (name "PUBLISHER") "Altium Limited"))
      (libsource (lib "Miscellaneous Devices") (part "Res3"))
    )
    (comp (ref "PT_R5")
      (value "Res3")
      (footprint "J1-0603")
      (description "Phototransitor Resistor")
      (fields (field (name "ALTIUM_VALUE") "5.6k") (field (name "PUBLISHER") "Altium Limited"))
      (libsource (lib "Miscellaneous Devices") (part "Res3"))
    )
    (comp (ref "PT_R6")
      (value "Res3")
      (footprint "J1-0603")
      (description "Phototransitor Resistor")
      (fields (field (name "ALTIUM_VALUE") "5.6k") (field (name "PUBLISHER") "Altium Limited"))
      (libsource (lib "Miscellaneous Devices") (part "Res3"))
    )
    (comp (ref "PT_R7")
      (value "Res3")
      (footprint "J1-0603")
      (description "Phototransitor Resistor")
      (fields (field (name "ALTIUM_VALUE") "5.6k") (field (name "PUBLISHER") "Altium Limited"))
      (libsource (lib "Miscellaneous Devices") (part "Res3"))
    )
    (comp (ref "PT_R8")
      (value "Res3")
      (footprint "J1-0603")
      (description "Phototransitor Resistor")
      (fields (field (name "ALTIUM_VALUE") "5.6k") (field (name "PUBLISHER") "Altium Limited"))
      (libsource (lib "Miscellaneous Devices") (part "Res3"))
    )
    (comp (ref "PT_R9")
      (value "Res3")
      (footprint "J1-0603")
      (description "Phototransitor Resistor")
      (fields (field (name "ALTIUM_VALUE") "5.6k") (field (name "PUBLISHER") "Altium Limited"))
      (libsource (lib "Miscellaneous Devices") (part "Res3"))
    )
    (comp (ref "PT_R10")
      (value "Res3")
      (footprint "J1-0603")
      (description "Phototransitor Resistor")
      (fields (field (name "ALTIUM_VALUE") "5.6k") (field (name "PUBLISHER") "Altium Limited"))
      (libsource (lib "Miscellaneous Devices") (part "Res3"))
    )
    (comp (ref "PT_R11")
      (value "Res3")
      (footprint "J1-0603")
      (description "Phototransitor Resistor")
      (fields (field (name "ALTIUM_VALUE") "5.6k") (field (name "PUBLISHER") "Altium Limited"))
      (libsource (lib "Miscellaneous Devices") (part "Res3"))
    )
    (comp (ref "PT_R12")
      (value "Res3")
      (footprint "J1-0603")
      (description "Phototransitor Resistor")
      (fields (field (name "ALTIUM_VALUE") "5.6k") (field (name "PUBLISHER") "Altium Limited"))
      (libsource (lib "Miscellaneous Devices") (part "Res3"))
    )
    (comp (ref "PT_R13")
      (value "Res3")
      (footprint "J1-0603")
      (description "Phototransitor Resistor")
      (fields (field (name "ALTIUM_VALUE") "5.6k") (field (name "PUBLISHER") "Altium Limited"))
      (libsource (lib "Miscellaneous Devices") (part "Res3"))
    )
    (comp (ref "PT_R14")
      (value "Res3")
      (footprint "J1-0603")
      (description "Phototransitor Resistor")
      (fields (field (name "ALTIUM_VALUE") "5.6k") (field (name "PUBLISHER") "Altium Limited"))
      (libsource (lib "Miscellaneous Devices") (part "Res3"))
    )
    (comp (ref "PT_R15")
      (value "Res3")
      (footprint "J1-0603")
      (description "Phototransitor Resistor")
      (fields (field (name "ALTIUM_VALUE") "5.6k") (field (name "PUBLISHER") "Altium Limited"))
      (libsource (lib "Miscellaneous Devices") (part "Res3"))
    )
    (comp (ref "PT_R16")
      (value "Res3")
      (footprint "J1-0603")
      (description "Phototransitor Resistor")
      (fields (field (name "ALTIUM_VALUE") "5.6k") (field (name "PUBLISHER") "Altium Limited"))
      (libsource (lib "Miscellaneous Devices") (part "Res3"))
    )
    (comp (ref "PT_R17")
      (value "Res3")
      (footprint "J1-0603")
      (description "Phototransitor Resistor")
      (fields (field (name "ALTIUM_VALUE") "5.6k") (field (name "PUBLISHER") "Altium Limited"))
      (libsource (lib "Miscellaneous Devices") (part "Res3"))
    )
    (comp (ref "PT_R18")
      (value "Res3")
      (footprint "J1-0603")
      (description "Phototransitor Resistor")
      (fields (field (name "ALTIUM_VALUE") "5.6k") (field (name "PUBLISHER") "Altium Limited"))
      (libsource (lib "Miscellaneous Devices") (part "Res3"))
    )
    (comp (ref "PT_R19")
      (value "Res3")
      (footprint "J1-0603")
      (description "Phototransitor Resistor")
      (fields (field (name "ALTIUM_VALUE") "5.6k") (field (name "PUBLISHER") "Altium Limited"))
      (libsource (lib "Miscellaneous Devices") (part "Res3"))
    )
    (comp (ref "PT_R20")
      (value "Res3")
      (footprint "J1-0603")
      (description "Phototransitor Resistor")
      (fields (field (name "ALTIUM_VALUE") "5.6k") (field (name "PUBLISHER") "Altium Limited"))
      (libsource (lib "Miscellaneous Devices") (part "Res3"))
    )
    (comp (ref "PT_R21")
      (value "Res3")
      (footprint "J1-0603")
      (description "Phototransitor Resistor")
      (fields (field (name "ALTIUM_VALUE") "5.6k") (field (name "PUBLISHER") "Altium Limited"))
      (libsource (lib "Miscellaneous Devices") (part "Res3"))
    )
    (comp (ref "PT_R22")
      (value "Res3")
      (footprint "J1-0603")
      (description "Phototransitor Resistor")
      (fields (field (name "ALTIUM_VALUE") "5.6k") (field (name "PUBLISHER") "Altium Limited"))
      (libsource (lib "Miscellaneous Devices") (part "Res3"))
    )
    (comp (ref "PT_R23")
      (value "Res3")
      (footprint "J1-0603")
      (description "Phototransitor Resistor")
      (fields (field (name "ALTIUM_VALUE") "5.6k") (field (name "PUBLISHER") "Altium Limited"))
      (libsource (lib "Miscellaneous Devices") (part "Res3"))
    )
    (comp (ref "PT_R24")
      (value "Res3")
      (footprint "J1-0603")
      (description "Phototransitor Resistor")
      (fields (field (name "ALTIUM_VALUE") "5.6k") (field (name "PUBLISHER") "Altium Limited"))
      (libsource (lib "Miscellaneous Devices") (part "Res3"))
    )
    (comp (ref "PT_R25")
      (value "Res3")
      (footprint "J1-0603")
      (description "Phototransitor Resistor")
      (fields (field (name "ALTIUM_VALUE") "5.6k") (field (name "PUBLISHER") "Altium Limited"))
      (libsource (lib "Miscellaneous Devices") (part "Res3"))
    )
    (comp (ref "PT_R26")
      (value "Res3")
      (footprint "J1-0603")
      (description "Phototransitor Resistor")
      (fields (field (name "ALTIUM_VALUE") "5.6k") (field (name "PUBLISHER") "Altium Limited"))
      (libsource (lib "Miscellaneous Devices") (part "Res3"))
    )
    (comp (ref "PT_R27")
      (value "Res3")
      (footprint "J1-0603")
      (description "Phototransitor Resistor")
      (fields (field (name "ALTIUM_VALUE") "5.6k") (field (name "PUBLISHER") "Altium Limited"))
      (libsource (lib "Miscellaneous Devices") (part "Res3"))
    )
    (comp (ref "PT_R28")
      (value "Res3")
      (footprint "J1-0603")
      (description "Phototransitor Resistor")
      (fields (field (name "ALTIUM_VALUE") "5.6k") (field (name "PUBLISHER") "Altium Limited"))
      (libsource (lib "Miscellaneous Devices") (part "Res3"))
    )
    (comp (ref "PT_R29")
      (value "Res3")
      (footprint "J1-0603")
      (description "Phototransitor Resistor")
      (fields (field (name "ALTIUM_VALUE") "5.6k") (field (name "PUBLISHER") "Altium Limited"))
      (libsource (lib "Miscellaneous Devices") (part "Res3"))
    )
    (comp (ref "PT_R30")
      (value "Res3")
      (footprint "J1-0603")
      (description "Phototransitor Resistor")
      (fields (field (name "ALTIUM_VALUE") "5.6k") (field (name "PUBLISHER") "Altium Limited"))
      (libsource (lib "Miscellaneous Devices") (part "Res3"))
    )
    (comp (ref "PT_R31")
      (value "Res3")
      (footprint "J1-0603")
      (description "Phototransitor Resistor")
      (fields (field (name "ALTIUM_VALUE") "5.6k") (field (name "PUBLISHER") "Altium Limited"))
      (libsource (lib "Miscellaneous Devices") (part "Res3"))
    )
    (comp (ref "PT_R32")
      (value "Res3")
      (footprint "J1-0603")
      (description "Phototransitor Resistor")
      (fields (field (name "ALTIUM_VALUE") "5.6k") (field (name "PUBLISHER") "Altium Limited"))
      (libsource (lib "Miscellaneous Devices") (part "Res3"))
    )
    (comp (ref "PT_R33")
      (value "Res3")
      (footprint "J1-0603")
      (description "Phototransitor Resistor")
      (fields (field (name "ALTIUM_VALUE") "5.6k") (field (name "PUBLISHER") "Altium Limited"))
      (libsource (lib "Miscellaneous Devices") (part "Res3"))
    )
    (comp (ref "PT_R34")
      (value "Res3")
      (footprint "J1-0603")
      (description "Phototransitor Resistor")
      (fields (field (name "ALTIUM_VALUE") "5.6k") (field (name "PUBLISHER") "Altium Limited"))
      (libsource (lib "Miscellaneous Devices") (part "Res3"))
    )
    (comp (ref "PT_R35")
      (value "Res3")
      (footprint "J1-0603")
      (description "Phototransitor Resistor")
      (fields (field (name "ALTIUM_VALUE") "5.6k") (field (name "PUBLISHER") "Altium Limited"))
      (libsource (lib "Miscellaneous Devices") (part "Res3"))
    )
    (comp (ref "PT_R36")
      (value "Res3")
      (footprint "J1-0603")
      (description "Phototransitor Resistor")
      (fields (field (name "ALTIUM_VALUE") "5.6k") (field (name "PUBLISHER") "Altium Limited"))
      (libsource (lib "Miscellaneous Devices") (part "Res3"))
    )
    (comp (ref "PT_R37")
      (value "Res3")
      (footprint "J1-0603")
      (description "Phototransitor Resistor")
      (fields (field (name "ALTIUM_VALUE") "5.6k") (field (name "PUBLISHER") "Altium Limited"))
      (libsource (lib "Miscellaneous Devices") (part "Res3"))
    )
    (comp (ref "PT_R38")
      (value "Res3")
      (footprint "J1-0603")
      (description "Phototransitor Resistor")
      (fields (field (name "ALTIUM_VALUE") "5.6k") (field (name "PUBLISHER") "Altium Limited"))
      (libsource (lib "Miscellaneous Devices") (part "Res3"))
    )
    (comp (ref "PT_R39")
      (value "Res3")
      (footprint "J1-0603")
      (description "Phototransitor Resistor")
      (fields (field (name "ALTIUM_VALUE") "5.6k") (field (name "PUBLISHER") "Altium Limited"))
      (libsource (lib "Miscellaneous Devices") (part "Res3"))
    )
    (comp (ref "PT_R40")
      (value "Res3")
      (footprint "J1-0603")
      (description "Phototransitor Resistor")
      (fields (field (name "ALTIUM_VALUE") "5.6k") (field (name "PUBLISHER") "Altium Limited"))
      (libsource (lib "Miscellaneous Devices") (part "Res3"))
    )
    (comp (ref "PT_R41")
      (value "Res3")
      (footprint "J1-0603")
      (description "Phototransitor Resistor")
      (fields (field (name "ALTIUM_VALUE") "5.6k") (field (name "PUBLISHER") "Altium Limited"))
      (libsource (lib "Miscellaneous Devices") (part "Res3"))
    )
    (comp (ref "PT_R42")
      (value "Res3")
      (footprint "J1-0603")
      (description "Phototransitor Resistor")
      (fields (field (name "ALTIUM_VALUE") "5.6k") (field (name "PUBLISHER") "Altium Limited"))
      (libsource (lib "Miscellaneous Devices") (part "Res3"))
    )
    (comp (ref "PT_R43")
      (value "Res3")
      (footprint "J1-0603")
      (description "Phototransitor Resistor")
      (fields (field (name "ALTIUM_VALUE") "5.6k") (field (name "PUBLISHER") "Altium Limited"))
      (libsource (lib "Miscellaneous Devices") (part "Res3"))
    )
    (comp (ref "PT_R44")
      (value "Res3")
      (footprint "J1-0603")
      (description "Phototransitor Resistor")
      (fields (field (name "ALTIUM_VALUE") "5.6k") (field (name "PUBLISHER") "Altium Limited"))
      (libsource (lib "Miscellaneous Devices") (part "Res3"))
    )
    (comp (ref "PT_R45")
      (value "Res3")
      (footprint "J1-0603")
      (description "Phototransitor Resistor")
      (fields (field (name "ALTIUM_VALUE") "5.6k") (field (name "PUBLISHER") "Altium Limited"))
      (libsource (lib "Miscellaneous Devices") (part "Res3"))
    )
    (comp (ref "PT_R46")
      (value "Res3")
      (footprint "J1-0603")
      (description "Phototransitor Resistor")
      (fields (field (name "ALTIUM_VALUE") "5.6k") (field (name "PUBLISHER") "Altium Limited"))
      (libsource (lib "Miscellaneous Devices") (part "Res3"))
    )
    (comp (ref "PT_R47")
      (value "Res3")
      (footprint "J1-0603")
      (description "Phototransitor Resistor")
      (fields (field (name "ALTIUM_VALUE") "5.6k") (field (name "PUBLISHER") "Altium Limited"))
      (libsource (lib "Miscellaneous Devices") (part "Res3"))
    )
    (comp (ref "PT_R48")
      (value "Res3")
      (footprint "J1-0603")
      (description "Phototransitor Resistor")
      (fields (field (name "ALTIUM_VALUE") "5.6k") (field (name "PUBLISHER") "Altium Limited"))
      (libsource (lib "Miscellaneous Devices") (part "Res3"))
    )
    (comp (ref "PT_R49")
      (value "Res3")
      (footprint "J1-0603")
      (description "Phototransitor Resistor")
      (fields (field (name "ALTIUM_VALUE") "5.6k") (field (name "PUBLISHER") "Altium Limited"))
      (libsource (lib "Miscellaneous Devices") (part "Res3"))
    )
    (comp (ref "PT_R50")
      (value "Res3")
      (footprint "J1-0603")
      (description "Phototransitor Resistor")
      (fields (field (name "ALTIUM_VALUE") "5.6k") (field (name "PUBLISHER") "Altium Limited"))
      (libsource (lib "Miscellaneous Devices") (part "Res3"))
    )
    (comp (ref "PT_R51")
      (value "Res3")
      (footprint "J1-0603")
      (description "Phototransitor Resistor")
      (fields (field (name "ALTIUM_VALUE") "5.6k") (field (name "PUBLISHER") "Altium Limited"))
      (libsource (lib "Miscellaneous Devices") (part "Res3"))
    )
    (comp (ref "PT_R52")
      (value "Res3")
      (footprint "J1-0603")
      (description "Phototransitor Resistor")
      (fields (field (name "ALTIUM_VALUE") "5.6k") (field (name "PUBLISHER") "Altium Limited"))
      (libsource (lib "Miscellaneous Devices") (part "Res3"))
    )
    (comp (ref "PT_R53")
      (value "Res3")
      (footprint "J1-0603")
      (description "Phototransitor Resistor")
      (fields (field (name "ALTIUM_VALUE") "5.6k") (field (name "PUBLISHER") "Altium Limited"))
      (libsource (lib "Miscellaneous Devices") (part "Res3"))
    )
    (comp (ref "PT_R54")
      (value "Res3")
      (footprint "J1-0603")
      (description "Phototransitor Resistor")
      (fields (field (name "ALTIUM_VALUE") "5.6k") (field (name "PUBLISHER") "Altium Limited"))
      (libsource (lib "Miscellaneous Devices") (part "Res3"))
    )
    (comp (ref "PT_R55")
      (value "Res3")
      (footprint "J1-0603")
      (description "Phototransitor Resistor")
      (fields (field (name "ALTIUM_VALUE") "5.6k") (field (name "PUBLISHER") "Altium Limited"))
      (libsource (lib "Miscellaneous Devices") (part "Res3"))
    )
    (comp (ref "PT_R56")
      (value "Res3")
      (footprint "J1-0603")
      (description "Phototransitor Resistor")
      (fields (field (name "ALTIUM_VALUE") "5.6k") (field (name "PUBLISHER") "Altium Limited"))
      (libsource (lib "Miscellaneous Devices") (part "Res3"))
    )
    (comp (ref "PT_R57")
      (value "Res3")
      (footprint "J1-0603")
      (description "Phototransitor Resistor")
      (fields (field (name "ALTIUM_VALUE") "5.6k") (field (name "PUBLISHER") "Altium Limited"))
      (libsource (lib "Miscellaneous Devices") (part "Res3"))
    )
    (comp (ref "PT_R58")
      (value "Res3")
      (footprint "J1-0603")
      (description "Phototransitor Resistor")
      (fields (field (name "ALTIUM_VALUE") "5.6k") (field (name "PUBLISHER") "Altium Limited"))
      (libsource (lib "Miscellaneous Devices") (part "Res3"))
    )
    (comp (ref "PT_R59")
      (value "Res3")
      (footprint "J1-0603")
      (description "Phototransitor Resistor")
      (fields (field (name "ALTIUM_VALUE") "5.6k") (field (name "PUBLISHER") "Altium Limited"))
      (libsource (lib "Miscellaneous Devices") (part "Res3"))
    )
    (comp (ref "PT_R60")
      (value "Res3")
      (footprint "J1-0603")
      (description "Phototransitor Resistor")
      (fields (field (name "ALTIUM_VALUE") "5.6k") (field (name "PUBLISHER") "Altium Limited"))
      (libsource (lib "Miscellaneous Devices") (part "Res3"))
    )
    (comp (ref "PT_R61")
      (value "Res3")
      (footprint "J1-0603")
      (description "Phototransitor Resistor")
      (fields (field (name "ALTIUM_VALUE") "5.6k") (field (name "PUBLISHER") "Altium Limited"))
      (libsource (lib "Miscellaneous Devices") (part "Res3"))
    )
    (comp (ref "PT_R62")
      (value "Res3")
      (footprint "J1-0603")
      (description "Phototransitor Resistor")
      (fields (field (name "ALTIUM_VALUE") "5.6k") (field (name "PUBLISHER") "Altium Limited"))
      (libsource (lib "Miscellaneous Devices") (part "Res3"))
    )
    (comp (ref "PT_R63")
      (value "Res3")
      (footprint "J1-0603")
      (description "Phototransitor Resistor")
      (fields (field (name "ALTIUM_VALUE") "5.6k") (field (name "PUBLISHER") "Altium Limited"))
      (libsource (lib "Miscellaneous Devices") (part "Res3"))
    )
    (comp (ref "PT_R64")
      (value "Res3")
      (footprint "J1-0603")
      (description "Phototransitor Resistor")
      (fields (field (name "ALTIUM_VALUE") "5.6k") (field (name "PUBLISHER") "Altium Limited"))
      (libsource (lib "Miscellaneous Devices") (part "Res3"))
    )
    (comp (ref "R200")
      (value "Res3")
      (footprint "J1-0603")
      (description "Resistor")
      (fields (field (name "ALTIUM_VALUE") "4.7K") (field (name "PUBLISHER") "Altium Limited"))
      (libsource (lib "Miscellaneous Devices") (part "Res3"))
    )
    (comp (ref "R201")
      (value "4.7K")
      (footprint "J1-0603")
      (description "Resistor")
      (fields (field (name "ALTIUM_VALUE") "1K") (field (name "PUBLISHER") "Altium Limited"))
      (libsource (lib "Miscellaneous Devices") (part "Res3"))
    )
    (comp (ref "Rcg0")
      (value "100")
      (footprint "J1-0603")
      (description "Rcg Resistor")
      (fields (field (name "Comment") "Res3") (field (name "PUBLISHER") "Altium Limited"))
      (libsource (lib "Miscellaneous Devices") (part "Res3"))
    )
    (comp (ref "Rcg1")
      (value "100")
      (footprint "J1-0603")
      (description "Rcg Resistor")
      (fields (field (name "Comment") "Res3") (field (name "PUBLISHER") "Altium Limited"))
      (libsource (lib "Miscellaneous Devices") (part "Res3"))
    )
    (comp (ref "Rcg2")
      (value "100")
      (footprint "J1-0603")
      (description "Rcg Resistor")
      (fields (field (name "Comment") "Res3") (field (name "PUBLISHER") "Altium Limited"))
      (libsource (lib "Miscellaneous Devices") (part "Res3"))
    )
    (comp (ref "Rcg3")
      (value "100")
      (footprint "J1-0603")
      (description "Rcg Resistor")
      (fields (field (name "Comment") "Res3") (field (name "PUBLISHER") "Altium Limited"))
      (libsource (lib "Miscellaneous Devices") (part "Res3"))
    )
    (comp (ref "Rcg4")
      (value "100")
      (footprint "J1-0603")
      (description "Rcg Resistor")
      (fields (field (name "Comment") "Res3") (field (name "PUBLISHER") "Altium Limited"))
      (libsource (lib "Miscellaneous Devices") (part "Res3"))
    )
    (comp (ref "Rcg5")
      (value "100")
      (footprint "J1-0603")
      (description "Rcg Resistor")
      (fields (field (name "Comment") "Res3") (field (name "PUBLISHER") "Altium Limited"))
      (libsource (lib "Miscellaneous Devices") (part "Res3"))
    )
    (comp (ref "Rcg6")
      (value "100")
      (footprint "J1-0603")
      (description "Rcg Resistor")
      (fields (field (name "Comment") "Res3") (field (name "PUBLISHER") "Altium Limited"))
      (libsource (lib "Miscellaneous Devices") (part "Res3"))
    )
    (comp (ref "Rcg7")
      (value "100")
      (footprint "J1-0603")
      (description "Rcg Resistor")
      (fields (field (name "Comment") "Res3") (field (name "PUBLISHER") "Altium Limited"))
      (libsource (lib "Miscellaneous Devices") (part "Res3"))
    )
    (comp (ref "Rci0")
      (value "10")
      (footprint "J1-0603")
      (description "Csel Resistor")
      (fields (field (name "Comment") "Res3") (field (name "PUBLISHER") "Altium Limited"))
      (libsource (lib "Miscellaneous Devices") (part "Res3"))
    )
    (comp (ref "Rci1")
      (value "10")
      (footprint "J1-0603")
      (description "Csel Resistor")
      (fields (field (name "Comment") "Res3") (field (name "PUBLISHER") "Altium Limited"))
      (libsource (lib "Miscellaneous Devices") (part "Res3"))
    )
    (comp (ref "Rci2")
      (value "10")
      (footprint "J1-0603")
      (description "Csel Resistor")
      (fields (field (name "Comment") "Res3") (field (name "PUBLISHER") "Altium Limited"))
      (libsource (lib "Miscellaneous Devices") (part "Res3"))
    )
    (comp (ref "Rci3")
      (value "10")
      (footprint "J1-0603")
      (description "Csel Resistor")
      (fields (field (name "Comment") "Res3") (field (name "PUBLISHER") "Altium Limited"))
      (libsource (lib "Miscellaneous Devices") (part "Res3"))
    )
    (comp (ref "Rci4")
      (value "10")
      (footprint "J1-0603")
      (description "Csel Resistor")
      (fields (field (name "Comment") "Res3") (field (name "PUBLISHER") "Altium Limited"))
      (libsource (lib "Miscellaneous Devices") (part "Res3"))
    )
    (comp (ref "Rci5")
      (value "10")
      (footprint "J1-0603")
      (description "Csel Resistor")
      (fields (field (name "Comment") "Res3") (field (name "PUBLISHER") "Altium Limited"))
      (libsource (lib "Miscellaneous Devices") (part "Res3"))
    )
    (comp (ref "Rci6")
      (value "10")
      (footprint "J1-0603")
      (description "Csel Resistor")
      (fields (field (name "Comment") "Res3") (field (name "PUBLISHER") "Altium Limited"))
      (libsource (lib "Miscellaneous Devices") (part "Res3"))
    )
    (comp (ref "Rci7")
      (value "10")
      (footprint "J1-0603")
      (description "Csel Resistor")
      (fields (field (name "Comment") "Res3") (field (name "PUBLISHER") "Altium Limited"))
      (libsource (lib "Miscellaneous Devices") (part "Res3"))
    )
    (comp (ref "Rin0")
      (value "1K")
      (footprint "J1-0603")
      (description "Rsel resistor")
      (fields (field (name "Comment") "Res3") (field (name "PUBLISHER") "Altium Limited"))
      (libsource (lib "Miscellaneous Devices") (part "Res3"))
    )
    (comp (ref "Rin1")
      (value "1K")
      (footprint "J1-0603")
      (description "Rsel resistor")
      (fields (field (name "Comment") "Res3") (field (name "PUBLISHER") "Altium Limited"))
      (libsource (lib "Miscellaneous Devices") (part "Res3"))
    )
    (comp (ref "Rin2")
      (value "1K")
      (footprint "J1-0603")
      (description "Rsel resistor")
      (fields (field (name "Comment") "Res3") (field (name "PUBLISHER") "Altium Limited"))
      (libsource (lib "Miscellaneous Devices") (part "Res3"))
    )
    (comp (ref "Rin3")
      (value "1K")
      (footprint "J1-0603")
      (description "Rsel resistor")
      (fields (field (name "Comment") "Res3") (field (name "PUBLISHER") "Altium Limited"))
      (libsource (lib "Miscellaneous Devices") (part "Res3"))
    )
    (comp (ref "Rin4")
      (value "1K")
      (footprint "J1-0603")
      (description "Rsel resistor")
      (fields (field (name "Comment") "Res3") (field (name "PUBLISHER") "Altium Limited"))
      (libsource (lib "Miscellaneous Devices") (part "Res3"))
    )
    (comp (ref "Rin5")
      (value "1K")
      (footprint "J1-0603")
      (description "Rsel resistor")
      (fields (field (name "Comment") "Res3") (field (name "PUBLISHER") "Altium Limited"))
      (libsource (lib "Miscellaneous Devices") (part "Res3"))
    )
    (comp (ref "Rin6")
      (value "1K")
      (footprint "J1-0603")
      (description "Rsel resistor")
      (fields (field (name "Comment") "Res3") (field (name "PUBLISHER") "Altium Limited"))
      (libsource (lib "Miscellaneous Devices") (part "Res3"))
    )
    (comp (ref "Rin7")
      (value "1K")
      (footprint "J1-0603")
      (description "Rsel resistor")
      (fields (field (name "Comment") "Res3") (field (name "PUBLISHER") "Altium Limited"))
      (libsource (lib "Miscellaneous Devices") (part "Res3"))
    )
    (comp (ref "ROUT0")
      (value "200")
      (footprint "J1-0603")
      (description "Resistor")
      (fields (field (name "Comment") "Res3") (field (name "PUBLISHER") "Altium Limited"))
      (libsource (lib "Miscellaneous Devices") (part "Res3"))
    )
    (comp (ref "ROUT1")
      (value "200")
      (footprint "J1-0603")
      (description "Resistor")
      (fields (field (name "Comment") "Res3") (field (name "PUBLISHER") "Altium Limited"))
      (libsource (lib "Miscellaneous Devices") (part "Res3"))
    )
    (comp (ref "Rvs0")
      (value "10K")
      (footprint "J1-0603")
      (description "Rvs Resistor")
      (fields (field (name "Comment") "Res3") (field (name "PUBLISHER") "Altium Limited"))
      (libsource (lib "Miscellaneous Devices") (part "Res3"))
    )
    (comp (ref "Rvs1")
      (value "10K")
      (footprint "J1-0603")
      (description "Rvs Resistor")
      (fields (field (name "Comment") "Res3") (field (name "PUBLISHER") "Altium Limited"))
      (libsource (lib "Miscellaneous Devices") (part "Res3"))
    )
    (comp (ref "Rvs2")
      (value "10K")
      (footprint "J1-0603")
      (description "Rvs Resistor")
      (fields (field (name "Comment") "Res3") (field (name "PUBLISHER") "Altium Limited"))
      (libsource (lib "Miscellaneous Devices") (part "Res3"))
    )
    (comp (ref "Rvs3")
      (value "10K")
      (footprint "J1-0603")
      (description "Rvs Resistor")
      (fields (field (name "Comment") "Res3") (field (name "PUBLISHER") "Altium Limited"))
      (libsource (lib "Miscellaneous Devices") (part "Res3"))
    )
    (comp (ref "Rvs4")
      (value "10K")
      (footprint "J1-0603")
      (description "Rvs Resistor")
      (fields (field (name "Comment") "Res3") (field (name "PUBLISHER") "Altium Limited"))
      (libsource (lib "Miscellaneous Devices") (part "Res3"))
    )
    (comp (ref "Rvs5")
      (value "10K")
      (footprint "J1-0603")
      (description "Rvs Resistor")
      (fields (field (name "Comment") "Res3") (field (name "PUBLISHER") "Altium Limited"))
      (libsource (lib "Miscellaneous Devices") (part "Res3"))
    )
    (comp (ref "Rvs6")
      (value "10K")
      (footprint "J1-0603")
      (description "Rvs Resistor")
      (fields (field (name "Comment") "Res3") (field (name "PUBLISHER") "Altium Limited"))
      (libsource (lib "Miscellaneous Devices") (part "Res3"))
    )
    (comp (ref "Rvs7")
      (value "10K")
      (footprint "J1-0603")
      (description "Rvs Resistor")
      (fields (field (name "Comment") "Res3") (field (name "PUBLISHER") "Altium Limited"))
      (libsource (lib "Miscellaneous Devices") (part "Res3"))
    )
  )
  (nets
    (net (code "1") (name "/18V") (class "Default")
      (node (ref "319_0") (pin "3") (pinfunction "3_3") (pintype "passive"))
      (node (ref "319_1") (pin "2") (pinfunction "2_2") (pintype "passive"))
      (node (ref "319_2") (pin "3") (pinfunction "3_3") (pintype "passive"))
      (node (ref "319_3") (pin "2") (pinfunction "2_2") (pintype "passive"))
      (node (ref "810_0") (pin "3") (pinfunction "3_3") (pintype "passive"))
      (node (ref "810_1") (pin "2") (pinfunction "2_2") (pintype "passive"))
      (node (ref "810_2") (pin "3") (pinfunction "3_3") (pintype "passive"))
      (node (ref "810_3") (pin "2") (pinfunction "2_2") (pintype "passive"))
      (node (ref "C1") (pin "2") (pinfunction "2_2") (pintype "passive"))
      (node (ref "C2") (pin "2") (pinfunction "2_2") (pintype "passive"))
      (node (ref "C3") (pin "2") (pinfunction "2_2") (pintype "passive"))
      (node (ref "C4") (pin "2") (pinfunction "2_2") (pintype "passive"))
      (node (ref "H_3_1") (pin "3") (pinfunction "3_3") (pintype "passive"))
    )
    (net (code "2") (name "/ADC_COL0") (class "Default")
      (node (ref "H2") (pin "25") (pinfunction "25_25") (pintype "passive"))
      (node (ref "PT1") (pin "2") (pinfunction "E_2") (pintype "passive"))
      (node (ref "PT17") (pin "2") (pinfunction "E_2") (pintype "passive"))
      (node (ref "PT25") (pin "2") (pinfunction "E_2") (pintype "passive"))
      (node (ref "PT33") (pin "2") (pinfunction "E_2") (pintype "passive"))
      (node (ref "PT41") (pin "2") (pinfunction "E_2") (pintype "passive"))
      (node (ref "PT49") (pin "2") (pinfunction "E_2") (pintype "passive"))
      (node (ref "PT57") (pin "2") (pinfunction "E_2") (pintype "passive"))
      (node (ref "PT9") (pin "2") (pinfunction "E_2") (pintype "passive"))
      (node (ref "PT_R1") (pin "2") (pinfunction "2_2") (pintype "passive"))
      (node (ref "PT_R17") (pin "2") (pinfunction "2_2") (pintype "passive"))
      (node (ref "PT_R25") (pin "2") (pinfunction "2_2") (pintype "passive"))
      (node (ref "PT_R33") (pin "2") (pinfunction "2_2") (pintype "passive"))
      (node (ref "PT_R41") (pin "2") (pinfunction "2_2") (pintype "passive"))
      (node (ref "PT_R49") (pin "2") (pinfunction "2_2") (pintype "passive"))
      (node (ref "PT_R57") (pin "2") (pinfunction "2_2") (pintype "passive"))
      (node (ref "PT_R9") (pin "2") (pinfunction "2_2") (pintype "passive"))
    )
    (net (code "3") (name "/ADC_COL1") (class "Default")
      (node (ref "H2") (pin "26") (pinfunction "26_26") (pintype "passive"))
      (node (ref "PT10") (pin "2") (pinfunction "E_2") (pintype "passive"))
      (node (ref "PT18") (pin "2") (pinfunction "E_2") (pintype "passive"))
      (node (ref "PT2") (pin "2") (pinfunction "E_2") (pintype "passive"))
      (node (ref "PT26") (pin "2") (pinfunction "E_2") (pintype "passive"))
      (node (ref "PT34") (pin "2") (pinfunction "E_2") (pintype "passive"))
      (node (ref "PT42") (pin "2") (pinfunction "E_2") (pintype "passive"))
      (node (ref "PT50") (pin "2") (pinfunction "E_2") (pintype "passive"))
      (node (ref "PT58") (pin "2") (pinfunction "E_2") (pintype "passive"))
      (node (ref "PT_R10") (pin "2") (pinfunction "2_2") (pintype "passive"))
      (node (ref "PT_R18") (pin "2") (pinfunction "2_2") (pintype "passive"))
      (node (ref "PT_R2") (pin "2") (pinfunction "2_2") (pintype "passive"))
      (node (ref "PT_R26") (pin "2") (pinfunction "2_2") (pintype "passive"))
      (node (ref "PT_R34") (pin "2") (pinfunction "2_2") (pintype "passive"))
      (node (ref "PT_R42") (pin "2") (pinfunction "2_2") (pintype "passive"))
      (node (ref "PT_R50") (pin "2") (pinfunction "2_2") (pintype "passive"))
      (node (ref "PT_R58") (pin "2") (pinfunction "2_2") (pintype "passive"))
    )
    (net (code "4") (name "/ADC_COL2") (class "Default")
      (node (ref "H2") (pin "27") (pinfunction "27_27") (pintype "passive"))
      (node (ref "PT11") (pin "2") (pinfunction "E_2") (pintype "passive"))
      (node (ref "PT19") (pin "2") (pinfunction "E_2") (pintype "passive"))
      (node (ref "PT27") (pin "2") (pinfunction "E_2") (pintype "passive"))
      (node (ref "PT3") (pin "2") (pinfunction "E_2") (pintype "passive"))
      (node (ref "PT35") (pin "2") (pinfunction "E_2") (pintype "passive"))
      (node (ref "PT43") (pin "2") (pinfunction "E_2") (pintype "passive"))
      (node (ref "PT51") (pin "2") (pinfunction "E_2") (pintype "passive"))
      (node (ref "PT59") (pin "2") (pinfunction "E_2") (pintype "passive"))
      (node (ref "PT_R11") (pin "2") (pinfunction "2_2") (pintype "passive"))
      (node (ref "PT_R19") (pin "2") (pinfunction "2_2") (pintype "passive"))
      (node (ref "PT_R27") (pin "2") (pinfunction "2_2") (pintype "passive"))
      (node (ref "PT_R3") (pin "2") (pinfunction "2_2") (pintype "passive"))
      (node (ref "PT_R35") (pin "2") (pinfunction "2_2") (pintype "passive"))
      (node (ref "PT_R43") (pin "2") (pinfunction "2_2") (pintype "passive"))
      (node (ref "PT_R51") (pin "2") (pinfunction "2_2") (pintype "passive"))
      (node (ref "PT_R59") (pin "2") (pinfunction "2_2") (pintype "passive"))
    )
    (net (code "5") (name "/ADC_COL3") (class "Default")
      (node (ref "H2") (pin "28") (pinfunction "28_28") (pintype "passive"))
      (node (ref "PT12") (pin "2") (pinfunction "E_2") (pintype "passive"))
      (node (ref "PT20") (pin "2") (pinfunction "E_2") (pintype "passive"))
      (node (ref "PT28") (pin "2") (pinfunction "E_2") (pintype "passive"))
      (node (ref "PT36") (pin "2") (pinfunction "E_2") (pintype "passive"))
      (node (ref "PT4") (pin "2") (pinfunction "E_2") (pintype "passive"))
      (node (ref "PT44") (pin "2") (pinfunction "E_2") (pintype "passive"))
      (node (ref "PT52") (pin "2") (pinfunction "E_2") (pintype "passive"))
      (node (ref "PT60") (pin "2") (pinfunction "E_2") (pintype "passive"))
      (node (ref "PT_R12") (pin "2") (pinfunction "2_2") (pintype "passive"))
      (node (ref "PT_R20") (pin "2") (pinfunction "2_2") (pintype "passive"))
      (node (ref "PT_R28") (pin "2") (pinfunction "2_2") (pintype "passive"))
      (node (ref "PT_R36") (pin "2") (pinfunction "2_2") (pintype "passive"))
      (node (ref "PT_R4") (pin "2") (pinfunction "2_2") (pintype "passive"))
      (node (ref "PT_R44") (pin "2") (pinfunction "2_2") (pintype "passive"))
      (node (ref "PT_R52") (pin "2") (pinfunction "2_2") (pintype "passive"))
      (node (ref "PT_R60") (pin "2") (pinfunction "2_2") (pintype "passive"))
    )
    (net (code "6") (name "/ADC_COL4") (class "Default")
      (node (ref "H2") (pin "29") (pinfunction "29_29") (pintype "passive"))
      (node (ref "PT13") (pin "2") (pinfunction "E_2") (pintype "passive"))
      (node (ref "PT21") (pin "2") (pinfunction "E_2") (pintype "passive"))
      (node (ref "PT29") (pin "2") (pinfunction "E_2") (pintype "passive"))
      (node (ref "PT37") (pin "2") (pinfunction "E_2") (pintype "passive"))
      (node (ref "PT45") (pin "2") (pinfunction "E_2") (pintype "passive"))
      (node (ref "PT5") (pin "2") (pinfunction "E_2") (pintype "passive"))
      (node (ref "PT53") (pin "2") (pinfunction "E_2") (pintype "passive"))
      (node (ref "PT61") (pin "2") (pinfunction "E_2") (pintype "passive"))
      (node (ref "PT_R13") (pin "2") (pinfunction "2_2") (pintype "passive"))
      (node (ref "PT_R21") (pin "2") (pinfunction "2_2") (pintype "passive"))
      (node (ref "PT_R29") (pin "2") (pinfunction "2_2") (pintype "passive"))
      (node (ref "PT_R37") (pin "2") (pinfunction "2_2") (pintype "passive"))
      (node (ref "PT_R45") (pin "2") (pinfunction "2_2") (pintype "passive"))
      (node (ref "PT_R5") (pin "2") (pinfunction "2_2") (pintype "passive"))
      (node (ref "PT_R53") (pin "2") (pinfunction "2_2") (pintype "passive"))
      (node (ref "PT_R61") (pin "2") (pinfunction "2_2") (pintype "passive"))
    )
    (net (code "7") (name "/ADC_COL5") (class "Default")
      (node (ref "H2") (pin "30") (pinfunction "30_30") (pintype "passive"))
      (node (ref "PT14") (pin "2") (pinfunction "E_2") (pintype "passive"))
      (node (ref "PT22") (pin "2") (pinfunction "E_2") (pintype "passive"))
      (node (ref "PT30") (pin "2") (pinfunction "E_2") (pintype "passive"))
      (node (ref "PT38") (pin "2") (pinfunction "E_2") (pintype "passive"))
      (node (ref "PT46") (pin "2") (pinfunction "E_2") (pintype "passive"))
      (node (ref "PT54") (pin "2") (pinfunction "E_2") (pintype "passive"))
      (node (ref "PT6") (pin "2") (pinfunction "E_2") (pintype "passive"))
      (node (ref "PT62") (pin "2") (pinfunction "E_2") (pintype "passive"))
      (node (ref "PT_R14") (pin "2") (pinfunction "2_2") (pintype "passive"))
      (node (ref "PT_R22") (pin "2") (pinfunction "2_2") (pintype "passive"))
      (node (ref "PT_R30") (pin "2") (pinfunction "2_2") (pintype "passive"))
      (node (ref "PT_R38") (pin "2") (pinfunction "2_2") (pintype "passive"))
      (node (ref "PT_R46") (pin "2") (pinfunction "2_2") (pintype "passive"))
      (node (ref "PT_R54") (pin "2") (pinfunction "2_2") (pintype "passive"))
      (node (ref "PT_R6") (pin "2") (pinfunction "2_2") (pintype "passive"))
      (node (ref "PT_R62") (pin "2") (pinfunction "2_2") (pintype "passive"))
    )
    (net (code "8") (name "/ADC_COL6") (class "Default")
      (node (ref "H2") (pin "31") (pinfunction "31_31") (pintype "passive"))
      (node (ref "PT15") (pin "2") (pinfunction "E_2") (pintype "passive"))
      (node (ref "PT23") (pin "2") (pinfunction "E_2") (pintype "passive"))
      (node (ref "PT31") (pin "2") (pinfunction "E_2") (pintype "passive"))
      (node (ref "PT39") (pin "2") (pinfunction "E_2") (pintype "passive"))
      (node (ref "PT47") (pin "2") (pinfunction "E_2") (pintype "passive"))
      (node (ref "PT55") (pin "2") (pinfunction "E_2") (pintype "passive"))
      (node (ref "PT63") (pin "2") (pinfunction "E_2") (pintype "passive"))
      (node (ref "PT7") (pin "2") (pinfunction "E_2") (pintype "passive"))
      (node (ref "PT_R15") (pin "2") (pinfunction "2_2") (pintype "passive"))
      (node (ref "PT_R23") (pin "2") (pinfunction "2_2") (pintype "passive"))
      (node (ref "PT_R31") (pin "2") (pinfunction "2_2") (pintype "passive"))
      (node (ref "PT_R39") (pin "2") (pinfunction "2_2") (pintype "passive"))
      (node (ref "PT_R47") (pin "2") (pinfunction "2_2") (pintype "passive"))
      (node (ref "PT_R55") (pin "2") (pinfunction "2_2") (pintype "passive"))
      (node (ref "PT_R63") (pin "2") (pinfunction "2_2") (pintype "passive"))
      (node (ref "PT_R7") (pin "2") (pinfunction "2_2") (pintype "passive"))
    )
    (net (code "9") (name "/ADC_COL7") (class "Default")
      (node (ref "H2") (pin "32") (pinfunction "32_32") (pintype "passive"))
      (node (ref "PT16") (pin "2") (pinfunction "E_2") (pintype "passive"))
      (node (ref "PT24") (pin "2") (pinfunction "E_2") (pintype "passive"))
      (node (ref "PT32") (pin "2") (pinfunction "E_2") (pintype "passive"))
      (node (ref "PT40") (pin "2") (pinfunction "E_2") (pintype "passive"))
      (node (ref "PT48") (pin "2") (pinfunction "E_2") (pintype "passive"))
      (node (ref "PT56") (pin "2") (pinfunction "E_2") (pintype "passive"))
      (node (ref "PT64") (pin "2") (pinfunction "E_2") (pintype "passive"))
      (node (ref "PT8") (pin "2") (pinfunction "E_2") (pintype "passive"))
      (node (ref "PT_R16") (pin "2") (pinfunction "2_2") (pintype "passive"))
      (node (ref "PT_R24") (pin "2") (pinfunction "2_2") (pintype "passive"))
      (node (ref "PT_R32") (pin "2") (pinfunction "2_2") (pintype "passive"))
      (node (ref "PT_R40") (pin "2") (pinfunction "2_2") (pintype "passive"))
      (node (ref "PT_R48") (pin "2") (pinfunction "2_2") (pintype "passive"))
      (node (ref "PT_R56") (pin "2") (pinfunction "2_2") (pintype "passive"))
      (node (ref "PT_R64") (pin "2") (pinfunction "2_2") (pintype "passive"))
      (node (ref "PT_R8") (pin "2") (pinfunction "2_2") (pintype "passive"))
    )
    (net (code "10") (name "/CKI") (class "Default")
      (node (ref "H2") (pin "35") (pinfunction "35_35") (pintype "passive"))
      (node (ref "LED1") (pin "CKI") (pinfunction "CKI_CKI") (pintype "bidirectional"))
    )
    (net (code "11") (name "/COL0") (class "Default")
      (node (ref "IR_R1") (pin "1") (pinfunction "1_1") (pintype "passive"))
      (node (ref "IR_R17") (pin "1") (pinfunction "1_1") (pintype "passive"))
      (node (ref "IR_R25") (pin "1") (pinfunction "1_1") (pintype "passive"))
      (node (ref "IR_R33") (pin "1") (pinfunction "1_1") (pintype "passive"))
      (node (ref "IR_R41") (pin "1") (pinfunction "1_1") (pintype "passive"))
      (node (ref "IR_R49") (pin "1") (pinfunction "1_1") (pintype "passive"))
      (node (ref "IR_R57") (pin "1") (pinfunction "1_1") (pintype "passive"))
      (node (ref "IR_R9") (pin "1") (pinfunction "1_1") (pintype "passive"))
      (node (ref "MOSN0") (pin "3") (pinfunction "D_3") (pintype "bidirectional"))
    )
    (net (code "12") (name "/COL1") (class "Default")
      (node (ref "IR_R10") (pin "1") (pinfunction "1_1") (pintype "passive"))
      (node (ref "IR_R18") (pin "1") (pinfunction "1_1") (pintype "passive"))
      (node (ref "IR_R2") (pin "1") (pinfunction "1_1") (pintype "passive"))
      (node (ref "IR_R26") (pin "1") (pinfunction "1_1") (pintype "passive"))
      (node (ref "IR_R34") (pin "1") (pinfunction "1_1") (pintype "passive"))
      (node (ref "IR_R42") (pin "1") (pinfunction "1_1") (pintype "passive"))
      (node (ref "IR_R50") (pin "1") (pinfunction "1_1") (pintype "passive"))
      (node (ref "IR_R58") (pin "1") (pinfunction "1_1") (pintype "passive"))
      (node (ref "MOSN1") (pin "3") (pinfunction "D_3") (pintype "bidirectional"))
    )
    (net (code "13") (name "/COL10") (class "Default")
      (node (ref "IR_R11") (pin "1") (pinfunction "1_1") (pintype "passive"))
      (node (ref "IR_R19") (pin "1") (pinfunction "1_1") (pintype "passive"))
      (node (ref "IR_R27") (pin "1") (pinfunction "1_1") (pintype "passive"))
      (node (ref "IR_R3") (pin "1") (pinfunction "1_1") (pintype "passive"))
      (node (ref "IR_R35") (pin "1") (pinfunction "1_1") (pintype "passive"))
      (node (ref "IR_R43") (pin "1") (pinfunction "1_1") (pintype "passive"))
      (node (ref "IR_R51") (pin "1") (pinfunction "1_1") (pintype "passive"))
      (node (ref "IR_R59") (pin "1") (pinfunction "1_1") (pintype "passive"))
      (node (ref "MOSN2") (pin "3") (pinfunction "D_3") (pintype "bidirectional"))
    )
    (net (code "14") (name "/COL11") (class "Default")
      (node (ref "IR_R12") (pin "1") (pinfunction "1_1") (pintype "passive"))
      (node (ref "IR_R20") (pin "1") (pinfunction "1_1") (pintype "passive"))
      (node (ref "IR_R28") (pin "1") (pinfunction "1_1") (pintype "passive"))
      (node (ref "IR_R36") (pin "1") (pinfunction "1_1") (pintype "passive"))
      (node (ref "IR_R4") (pin "1") (pinfunction "1_1") (pintype "passive"))
      (node (ref "IR_R44") (pin "1") (pinfunction "1_1") (pintype "passive"))
      (node (ref "IR_R52") (pin "1") (pinfunction "1_1") (pintype "passive"))
      (node (ref "IR_R60") (pin "1") (pinfunction "1_1") (pintype "passive"))
      (node (ref "MOSN3") (pin "3") (pinfunction "D_3") (pintype "bidirectional"))
    )
    (net (code "15") (name "/COL12") (class "Default")
      (node (ref "IR_R13") (pin "1") (pinfunction "1_1") (pintype "passive"))
      (node (ref "IR_R21") (pin "1") (pinfunction "1_1") (pintype "passive"))
      (node (ref "IR_R29") (pin "1") (pinfunction "1_1") (pintype "passive"))
      (node (ref "IR_R37") (pin "1") (pinfunction "1_1") (pintype "passive"))
      (node (ref "IR_R45") (pin "1") (pinfunction "1_1") (pintype "passive"))
      (node (ref "IR_R5") (pin "1") (pinfunction "1_1") (pintype "passive"))
      (node (ref "IR_R53") (pin "1") (pinfunction "1_1") (pintype "passive"))
      (node (ref "IR_R61") (pin "1") (pinfunction "1_1") (pintype "passive"))
      (node (ref "MOSN4") (pin "3") (pinfunction "D_3") (pintype "bidirectional"))
    )
    (net (code "16") (name "/COL13") (class "Default")
      (node (ref "IR_R14") (pin "1") (pinfunction "1_1") (pintype "passive"))
      (node (ref "IR_R22") (pin "1") (pinfunction "1_1") (pintype "passive"))
      (node (ref "IR_R30") (pin "1") (pinfunction "1_1") (pintype "passive"))
      (node (ref "IR_R38") (pin "1") (pinfunction "1_1") (pintype "passive"))
      (node (ref "IR_R46") (pin "1") (pinfunction "1_1") (pintype "passive"))
      (node (ref "IR_R54") (pin "1") (pinfunction "1_1") (pintype "passive"))
      (node (ref "IR_R6") (pin "1") (pinfunction "1_1") (pintype "passive"))
      (node (ref "IR_R62") (pin "1") (pinfunction "1_1") (pintype "passive"))
      (node (ref "MOSN5") (pin "3") (pinfunction "D_3") (pintype "bidirectional"))
    )
    (net (code "17") (name "/COL14") (class "Default")
      (node (ref "IR_R15") (pin "1") (pinfunction "1_1") (pintype "passive"))
      (node (ref "IR_R23") (pin "1") (pinfunction "1_1") (pintype "passive"))
      (node (ref "IR_R31") (pin "1") (pinfunction "1_1") (pintype "passive"))
      (node (ref "IR_R39") (pin "1") (pinfunction "1_1") (pintype "passive"))
      (node (ref "IR_R47") (pin "1") (pinfunction "1_1") (pintype "passive"))
      (node (ref "IR_R55") (pin "1") (pinfunction "1_1") (pintype "passive"))
      (node (ref "IR_R63") (pin "1") (pinfunction "1_1") (pintype "passive"))
      (node (ref "IR_R7") (pin "1") (pinfunction "1_1") (pintype "passive"))
      (node (ref "MOSN6") (pin "3") (pinfunction "D_3") (pintype "bidirectional"))
    )
    (net (code "18") (name "/COL15") (class "Default")
      (node (ref "IR_R16") (pin "1") (pinfunction "1_1") (pintype "passive"))
      (node (ref "IR_R24") (pin "1") (pinfunction "1_1") (pintype "passive"))
      (node (ref "IR_R32") (pin "1") (pinfunction "1_1") (pintype "passive"))
      (node (ref "IR_R40") (pin "1") (pinfunction "1_1") (pintype "passive"))
      (node (ref "IR_R48") (pin "1") (pinfunction "1_1") (pintype "passive"))
      (node (ref "IR_R56") (pin "1") (pinfunction "1_1") (pintype "passive"))
      (node (ref "IR_R64") (pin "1") (pinfunction "1_1") (pintype "passive"))
      (node (ref "IR_R8") (pin "1") (pinfunction "1_1") (pintype "passive"))
      (node (ref "MOSN7") (pin "3") (pinfunction "D_3") (pintype "bidirectional"))
    )
    (net (code "19") (name "/I2C_1") (class "Default")
      (node (ref "319_1") (pin "4") (pinfunction "4_4") (pintype "passive"))
      (node (ref "319_3") (pin "4") (pinfunction "4_4") (pintype "passive"))
      (node (ref "810_1") (pin "4") (pinfunction "4_4") (pintype "passive"))
      (node (ref "810_3") (pin "4") (pinfunction "4_4") (pintype "passive"))
      (node (ref "H1") (pin "7") (pinfunction "B6_7") (pintype "passive"))
      (node (ref "R200") (pin "2") (pinfunction "2_2") (pintype "passive"))
    )
    (net (code "20") (name "/I2C_2") (class "Default")
      (node (ref "319_1") (pin "3") (pinfunction "3_3") (pintype "passive"))
      (node (ref "319_3") (pin "3") (pinfunction "3_3") (pintype "passive"))
      (node (ref "810_1") (pin "3") (pinfunction "3_3") (pintype "passive"))
      (node (ref "810_3") (pin "3") (pinfunction "3_3") (pintype "passive"))
      (node (ref "H1") (pin "6") (pinfunction "B7_6") (pintype "passive"))
      (node (ref "R201") (pin "2") (pinfunction "2_2") (pintype "passive"))
    )
    (net (code "21") (name "/M_CS0") (class "Default")
      (node (ref "H1") (pin "17") (pinfunction "B15_17") (pintype "passive"))
      (node (ref "M_C") (pin "11") (pinfunction "S0_11") (pintype "bidirectional"))
    )
    (net (code "22") (name "/M_CS1") (class "Default")
      (node (ref "H1") (pin "16") (pinfunction "A8_16") (pintype "passive"))
      (node (ref "M_C") (pin "10") (pinfunction "S1_10") (pintype "bidirectional"))
    )
    (net (code "23") (name "/M_CS2") (class "Default")
      (node (ref "H1") (pin "15") (pinfunction "A9_15") (pintype "passive"))
      (node (ref "M_C") (pin "9") (pinfunction "S2_9") (pintype "bidirectional"))
    )
    (net (code "24") (name "/M_RS0") (class "Default")
      (node (ref "H1") (pin "20") (pinfunction "B12_20") (pintype "passive"))
      (node (ref "M_R") (pin "11") (pinfunction "S0_11") (pintype "bidirectional"))
    )
    (net (code "25") (name "/M_RS1") (class "Default")
      (node (ref "H1") (pin "19") (pinfunction "B13_19") (pintype "passive"))
      (node (ref "M_R") (pin "10") (pinfunction "S1_10") (pintype "bidirectional"))
    )
    (net (code "26") (name "/M_RS2") (class "Default")
      (node (ref "H1") (pin "18") (pinfunction "B14_18") (pintype "passive"))
      (node (ref "M_R") (pin "9") (pinfunction "S2_9") (pintype "bidirectional"))
    )
    (net (code "27") (name "/ROW0") (class "Default")
      (node (ref "IR1") (pin "1") (pinfunction "A_1") (pintype "passive"))
      (node (ref "IR2") (pin "1") (pinfunction "A_1") (pintype "passive"))
      (node (ref "IR3") (pin "1") (pinfunction "A_1") (pintype "passive"))
      (node (ref "IR4") (pin "1") (pinfunction "A_1") (pintype "passive"))
      (node (ref "IR5") (pin "1") (pinfunction "A_1") (pintype "passive"))
      (node (ref "IR6") (pin "1") (pinfunction "A_1") (pintype "passive"))
      (node (ref "IR7") (pin "1") (pinfunction "A_1") (pintype "passive"))
      (node (ref "IR8") (pin "1") (pinfunction "A_1") (pintype "passive"))
      (node (ref "MOSP0") (pin "3") (pinfunction "D_3") (pintype "bidirectional"))
      (node (ref "PT1") (pin "1") (pinfunction "C_1") (pintype "passive"))
      (node (ref "PT2") (pin "1") (pinfunction "C_1") (pintype "passive"))
      (node (ref "PT3") (pin "1") (pinfunction "C_1") (pintype "passive"))
      (node (ref "PT4") (pin "1") (pinfunction "C_1") (pintype "passive"))
      (node (ref "PT5") (pin "1") (pinfunction "C_1") (pintype "passive"))
      (node (ref "PT6") (pin "1") (pinfunction "C_1") (pintype "passive"))
      (node (ref "PT7") (pin "1") (pinfunction "C_1") (pintype "passive"))
      (node (ref "PT8") (pin "1") (pinfunction "C_1") (pintype "passive"))
    )
    (net (code "28") (name "/ROW1") (class "Default")
      (node (ref "IR10") (pin "1") (pinfunction "A_1") (pintype "passive"))
      (node (ref "IR11") (pin "1") (pinfunction "A_1") (pintype "passive"))
      (node (ref "IR12") (pin "1") (pinfunction "A_1") (pintype "passive"))
      (node (ref "IR13") (pin "1") (pinfunction "A_1") (pintype "passive"))
      (node (ref "IR14") (pin "1") (pinfunction "A_1") (pintype "passive"))
      (node (ref "IR15") (pin "1") (pinfunction "A_1") (pintype "passive"))
      (node (ref "IR16") (pin "1") (pinfunction "A_1") (pintype "passive"))
      (node (ref "IR9") (pin "1") (pinfunction "A_1") (pintype "passive"))
      (node (ref "MOSP1") (pin "3") (pinfunction "D_3") (pintype "bidirectional"))
      (node (ref "PT10") (pin "1") (pinfunction "C_1") (pintype "passive"))
      (node (ref "PT11") (pin "1") (pinfunction "C_1") (pintype "passive"))
      (node (ref "PT12") (pin "1") (pinfunction "C_1") (pintype "passive"))
      (node (ref "PT13") (pin "1") (pinfunction "C_1") (pintype "passive"))
      (node (ref "PT14") (pin "1") (pinfunction "C_1") (pintype "passive"))
      (node (ref "PT15") (pin "1") (pinfunction "C_1") (pintype "passive"))
      (node (ref "PT16") (pin "1") (pinfunction "C_1") (pintype "passive"))
      (node (ref "PT9") (pin "1") (pinfunction "C_1") (pintype "passive"))
    )
    (net (code "29") (name "/ROW2") (class "Default")
      (node (ref "IR17") (pin "1") (pinfunction "A_1") (pintype "passive"))
      (node (ref "IR18") (pin "1") (pinfunction "A_1") (pintype "passive"))
      (node (ref "IR19") (pin "1") (pinfunction "A_1") (pintype "passive"))
      (node (ref "IR20") (pin "1") (pinfunction "A_1") (pintype "passive"))
      (node (ref "IR21") (pin "1") (pinfunction "A_1") (pintype "passive"))
      (node (ref "IR22") (pin "1") (pinfunction "A_1") (pintype "passive"))
      (node (ref "IR23") (pin "1") (pinfunction "A_1") (pintype "passive"))
      (node (ref "IR24") (pin "1") (pinfunction "A_1") (pintype "passive"))
      (node (ref "MOSP2") (pin "3") (pinfunction "D_3") (pintype "bidirectional"))
      (node (ref "PT17") (pin "1") (pinfunction "C_1") (pintype "passive"))
      (node (ref "PT18") (pin "1") (pinfunction "C_1") (pintype "passive"))
      (node (ref "PT19") (pin "1") (pinfunction "C_1") (pintype "passive"))
      (node (ref "PT20") (pin "1") (pinfunction "C_1") (pintype "passive"))
      (node (ref "PT21") (pin "1") (pinfunction "C_1") (pintype "passive"))
      (node (ref "PT22") (pin "1") (pinfunction "C_1") (pintype "passive"))
      (node (ref "PT23") (pin "1") (pinfunction "C_1") (pintype "passive"))
      (node (ref "PT24") (pin "1") (pinfunction "C_1") (pintype "passive"))
    )
    (net (code "30") (name "/ROW3") (class "Default")
      (node (ref "IR25") (pin "1") (pinfunction "A_1") (pintype "passive"))
      (node (ref "IR26") (pin "1") (pinfunction "A_1") (pintype "passive"))
      (node (ref "IR27") (pin "1") (pinfunction "A_1") (pintype "passive"))
      (node (ref "IR28") (pin "1") (pinfunction "A_1") (pintype "passive"))
      (node (ref "IR29") (pin "1") (pinfunction "A_1") (pintype "passive"))
      (node (ref "IR30") (pin "1") (pinfunction "A_1") (pintype "passive"))
      (node (ref "IR31") (pin "1") (pinfunction "A_1") (pintype "passive"))
      (node (ref "IR32") (pin "1") (pinfunction "A_1") (pintype "passive"))
      (node (ref "MOSP3") (pin "3") (pinfunction "D_3") (pintype "bidirectional"))
      (node (ref "PT25") (pin "1") (pinfunction "C_1") (pintype "passive"))
      (node (ref "PT26") (pin "1") (pinfunction "C_1") (pintype "passive"))
      (node (ref "PT27") (pin "1") (pinfunction "C_1") (pintype "passive"))
      (node (ref "PT28") (pin "1") (pinfunction "C_1") (pintype "passive"))
      (node (ref "PT29") (pin "1") (pinfunction "C_1") (pintype "passive"))
      (node (ref "PT30") (pin "1") (pinfunction "C_1") (pintype "passive"))
      (node (ref "PT31") (pin "1") (pinfunction "C_1") (pintype "passive"))
      (node (ref "PT32") (pin "1") (pinfunction "C_1") (pintype "passive"))
    )
    (net (code "31") (name "/ROW4") (class "Default")
      (node (ref "IR33") (pin "1") (pinfunction "A_1") (pintype "passive"))
      (node (ref "IR34") (pin "1") (pinfunction "A_1") (pintype "passive"))
      (node (ref "IR35") (pin "1") (pinfunction "A_1") (pintype "passive"))
      (node (ref "IR36") (pin "1") (pinfunction "A_1") (pintype "passive"))
      (node (ref "IR37") (pin "1") (pinfunction "A_1") (pintype "passive"))
      (node (ref "IR38") (pin "1") (pinfunction "A_1") (pintype "passive"))
      (node (ref "IR39") (pin "1") (pinfunction "A_1") (pintype "passive"))
      (node (ref "IR40") (pin "1") (pinfunction "A_1") (pintype "passive"))
      (node (ref "MOSP4") (pin "3") (pinfunction "D_3") (pintype "bidirectional"))
      (node (ref "PT33") (pin "1") (pinfunction "C_1") (pintype "passive"))
      (node (ref "PT34") (pin "1") (pinfunction "C_1") (pintype "passive"))
      (node (ref "PT35") (pin "1") (pinfunction "C_1") (pintype "passive"))
      (node (ref "PT36") (pin "1") (pinfunction "C_1") (pintype "passive"))
      (node (ref "PT37") (pin "1") (pinfunction "C_1") (pintype "passive"))
      (node (ref "PT38") (pin "1") (pinfunction "C_1") (pintype "passive"))
      (node (ref "PT39") (pin "1") (pinfunction "C_1") (pintype "passive"))
      (node (ref "PT40") (pin "1") (pinfunction "C_1") (pintype "passive"))
    )
    (net (code "32") (name "/ROW5") (class "Default")
      (node (ref "IR41") (pin "1") (pinfunction "A_1") (pintype "passive"))
      (node (ref "IR42") (pin "1") (pinfunction "A_1") (pintype "passive"))
      (node (ref "IR43") (pin "1") (pinfunction "A_1") (pintype "passive"))
      (node (ref "IR44") (pin "1") (pinfunction "A_1") (pintype "passive"))
      (node (ref "IR45") (pin "1") (pinfunction "A_1") (pintype "passive"))
      (node (ref "IR46") (pin "1") (pinfunction "A_1") (pintype "passive"))
      (node (ref "IR47") (pin "1") (pinfunction "A_1") (pintype "passive"))
      (node (ref "IR48") (pin "1") (pinfunction "A_1") (pintype "passive"))
      (node (ref "MOSP5") (pin "3") (pinfunction "D_3") (pintype "bidirectional"))
      (node (ref "PT41") (pin "1") (pinfunction "C_1") (pintype "passive"))
      (node (ref "PT42") (pin "1") (pinfunction "C_1") (pintype "passive"))
      (node (ref "PT43") (pin "1") (pinfunction "C_1") (pintype "passive"))
      (node (ref "PT44") (pin "1") (pinfunction "C_1") (pintype "passive"))
      (node (ref "PT45") (pin "1") (pinfunction "C_1") (pintype "passive"))
      (node (ref "PT46") (pin "1") (pinfunction "C_1") (pintype "passive"))
      (node (ref "PT47") (pin "1") (pinfunction "C_1") (pintype "passive"))
      (node (ref "PT48") (pin "1") (pinfunction "C_1") (pintype "passive"))
    )
    (net (code "33") (name "/ROW6") (class "Default")
      (node (ref "IR49") (pin "1") (pinfunction "A_1") (pintype "passive"))
      (node (ref "IR50") (pin "1") (pinfunction "A_1") (pintype "passive"))
      (node (ref "IR51") (pin "1") (pinfunction "A_1") (pintype "passive"))
      (node (ref "IR52") (pin "1") (pinfunction "A_1") (pintype "passive"))
      (node (ref "IR53") (pin "1") (pinfunction "A_1") (pintype "passive"))
      (node (ref "IR54") (pin "1") (pinfunction "A_1") (pintype "passive"))
      (node (ref "IR55") (pin "1") (pinfunction "A_1") (pintype "passive"))
      (node (ref "IR56") (pin "1") (pinfunction "A_1") (pintype "passive"))
      (node (ref "MOSP6") (pin "3") (pinfunction "D_3") (pintype "bidirectional"))
      (node (ref "PT49") (pin "1") (pinfunction "C_1") (pintype "passive"))
      (node (ref "PT50") (pin "1") (pinfunction "C_1") (pintype "passive"))
      (node (ref "PT51") (pin "1") (pinfunction "C_1") (pintype "passive"))
      (node (ref "PT52") (pin "1") (pinfunction "C_1") (pintype "passive"))
      (node (ref "PT53") (pin "1") (pinfunction "C_1") (pintype "passive"))
      (node (ref "PT54") (pin "1") (pinfunction "C_1") (pintype "passive"))
      (node (ref "PT55") (pin "1") (pinfunction "C_1") (pintype "passive"))
      (node (ref "PT56") (pin "1") (pinfunction "C_1") (pintype "passive"))
    )
    (net (code "34") (name "/ROW7") (class "Default")
      (node (ref "IR57") (pin "1") (pinfunction "A_1") (pintype "passive"))
      (node (ref "IR58") (pin "1") (pinfunction "A_1") (pintype "passive"))
      (node (ref "IR59") (pin "1") (pinfunction "A_1") (pintype "passive"))
      (node (ref "IR60") (pin "1") (pinfunction "A_1") (pintype "passive"))
      (node (ref "IR61") (pin "1") (pinfunction "A_1") (pintype "passive"))
      (node (ref "IR62") (pin "1") (pinfunction "A_1") (pintype "passive"))
      (node (ref "IR63") (pin "1") (pinfunction "A_1") (pintype "passive"))
      (node (ref "IR64") (pin "1") (pinfunction "A_1") (pintype "passive"))
      (node (ref "MOSP7") (pin "3") (pinfunction "D_3") (pintype "bidirectional"))
      (node (ref "PT57") (pin "1") (pinfunction "C_1") (pintype "passive"))
      (node (ref "PT58") (pin "1") (pinfunction "C_1") (pintype "passive"))
      (node (ref "PT59") (pin "1") (pinfunction "C_1") (pintype "passive"))
      (node (ref "PT60") (pin "1") (pinfunction "C_1") (pintype "passive"))
      (node (ref "PT61") (pin "1") (pinfunction "C_1") (pintype "passive"))
      (node (ref "PT62") (pin "1") (pinfunction "C_1") (pintype "passive"))
      (node (ref "PT63") (pin "1") (pinfunction "C_1") (pintype "passive"))
      (node (ref "PT64") (pin "1") (pinfunction "C_1") (pintype "passive"))
    )
    (net (code "35") (name "/SDI") (class "Default")
      (node (ref "H2") (pin "36") (pinfunction "36_36") (pintype "passive"))
      (node (ref "LED1") (pin "SDI") (pinfunction "SDI_SDI") (pintype "bidirectional"))
    )
    (net (code "36") (name "/csel0") (class "Default")
      (node (ref "M_C") (pin "13") (pinfunction "Y0_13") (pintype "bidirectional"))
      (node (ref "Rci0") (pin "1") (pinfunction "1_1") (pintype "passive"))
    )
    (net (code "37") (name "/csel1") (class "Default")
      (node (ref "M_C") (pin "14") (pinfunction "Y1_14") (pintype "bidirectional"))
      (node (ref "Rci1") (pin "1") (pinfunction "1_1") (pintype "passive"))
    )
    (net (code "38") (name "/csel2") (class "Default")
      (node (ref "M_C") (pin "15") (pinfunction "Y2_15") (pintype "bidirectional"))
      (node (ref "Rci2") (pin "1") (pinfunction "1_1") (pintype "passive"))
    )
    (net (code "39") (name "/csel3") (class "Default")
      (node (ref "M_C") (pin "12") (pinfunction "Y3_12") (pintype "bidirectional"))
      (node (ref "Rci3") (pin "1") (pinfunction "1_1") (pintype "passive"))
    )
    (net (code "40") (name "/csel4") (class "Default")
      (node (ref "M_C") (pin "1") (pinfunction "Y4_1") (pintype "bidirectional"))
      (node (ref "Rci4") (pin "1") (pinfunction "1_1") (pintype "passive"))
    )
    (net (code "41") (name "/csel5") (class "Default")
      (node (ref "M_C") (pin "5") (pinfunction "Y5_5") (pintype "bidirectional"))
      (node (ref "Rci5") (pin "1") (pinfunction "1_1") (pintype "passive"))
    )
    (net (code "42") (name "/csel6") (class "Default")
      (node (ref "M_C") (pin "2") (pinfunction "Y6_2") (pintype "bidirectional"))
      (node (ref "Rci6") (pin "1") (pinfunction "1_1") (pintype "passive"))
    )
    (net (code "43") (name "/csel7") (class "Default")
      (node (ref "M_C") (pin "4") (pinfunction "Y7_4") (pintype "bidirectional"))
      (node (ref "Rci7") (pin "1") (pinfunction "1_1") (pintype "passive"))
    )
    (net (code "44") (name "/rsel0") (class "Default")
      (node (ref "M_R") (pin "13") (pinfunction "Y0_13") (pintype "bidirectional"))
      (node (ref "Rin0") (pin "2") (pinfunction "2_2") (pintype "passive"))
    )
    (net (code "45") (name "/rsel1") (class "Default")
      (node (ref "M_R") (pin "14") (pinfunction "Y1_14") (pintype "bidirectional"))
      (node (ref "Rin1") (pin "2") (pinfunction "2_2") (pintype "passive"))
    )
    (net (code "46") (name "/rsel2") (class "Default")
      (node (ref "M_R") (pin "15") (pinfunction "Y2_15") (pintype "bidirectional"))
      (node (ref "Rin2") (pin "2") (pinfunction "2_2") (pintype "passive"))
    )
    (net (code "47") (name "/rsel3") (class "Default")
      (node (ref "M_R") (pin "12") (pinfunction "Y3_12") (pintype "bidirectional"))
      (node (ref "Rin3") (pin "2") (pinfunction "2_2") (pintype "passive"))
    )
    (net (code "48") (name "/rsel4") (class "Default")
      (node (ref "M_R") (pin "5") (pinfunction "Y5_5") (pintype "bidirectional"))
      (node (ref "Rin4") (pin "2") (pinfunction "2_2") (pintype "passive"))
    )
    (net (code "49") (name "/rsel5") (class "Default")
      (node (ref "M_R") (pin "1") (pinfunction "Y4_1") (pintype "bidirectional"))
      (node (ref "Rin5") (pin "2") (pinfunction "2_2") (pintype "passive"))
    )
    (net (code "50") (name "/rsel6") (class "Default")
      (node (ref "M_R") (pin "2") (pinfunction "Y6_2") (pintype "bidirectional"))
      (node (ref "Rin6") (pin "2") (pinfunction "2_2") (pintype "passive"))
    )
    (net (code "51") (name "/rsel7") (class "Default")
      (node (ref "M_R") (pin "4") (pinfunction "Y7_4") (pintype "bidirectional"))
      (node (ref "Rin7") (pin "2") (pinfunction "2_2") (pintype "passive"))
    )
    (net (code "52") (name "GND") (class "Default")
      (node (ref "319_0") (pin "4") (pinfunction "4_4") (pintype "passive"))
      (node (ref "319_1") (pin "1") (pinfunction "1_1") (pintype "passive"))
      (node (ref "319_2") (pin "4") (pinfunction "4_4") (pintype "passive"))
      (node (ref "319_3") (pin "1") (pinfunction "1_1") (pintype "passive"))
      (node (ref "810_0") (pin "4") (pinfunction "4_4") (pintype "passive"))
      (node (ref "810_1") (pin "1") (pinfunction "1_1") (pintype "passive"))
      (node (ref "810_2") (pin "4") (pinfunction "4_4") (pintype "passive"))
      (node (ref "810_3") (pin "1") (pinfunction "1_1") (pintype "passive"))
      (node (ref "C1") (pin "1") (pinfunction "1_1") (pintype "passive"))
      (node (ref "C2") (pin "1") (pinfunction "1_1") (pintype "passive"))
      (node (ref "C3") (pin "1") (pinfunction "1_1") (pintype "passive"))
      (node (ref "C4") (pin "1") (pinfunction "1_1") (pintype "passive"))
      (node (ref "H1") (pin "2") (pinfunction "G_2") (pintype "passive"))
      (node (ref "H2") (pin "39") (pinfunction "39_39") (pintype "passive"))
      (node (ref "H2") (pin "40") (pinfunction "40_40") (pintype "passive"))
      (node (ref "H_3_1") (pin "2") (pinfunction "2_2") (pintype "passive"))
      (node (ref "LED1") (pin "GND") (pinfunction "GND_GND") (pintype "bidirectional"))
      (node (ref "LED10") (pin "GND") (pinfunction "GND_GND") (pintype "bidirectional"))
      (node (ref "LED11") (pin "GND") (pinfunction "GND_GND") (pintype "bidirectional"))
      (node (ref "LED12") (pin "GND") (pinfunction "GND_GND") (pintype "bidirectional"))
      (node (ref "LED13") (pin "GND") (pinfunction "GND_GND") (pintype "bidirectional"))
      (node (ref "LED14") (pin "GND") (pinfunction "GND_GND") (pintype "bidirectional"))
      (node (ref "LED15") (pin "GND") (pinfunction "GND_GND") (pintype "bidirectional"))
      (node (ref "LED16") (pin "GND") (pinfunction "GND_GND") (pintype "bidirectional"))
      (node (ref "LED17") (pin "GND") (pinfunction "GND_GND") (pintype "bidirectional"))
      (node (ref "LED18") (pin "GND") (pinfunction "GND_GND") (pintype "bidirectional"))
      (node (ref "LED19") (pin "GND") (pinfunction "GND_GND") (pintype "bidirectional"))
      (node (ref "LED2") (pin "GND") (pinfunction "GND_GND") (pintype "bidirectional"))
      (node (ref "LED20") (pin "GND") (pinfunction "GND_GND") (pintype "bidirectional"))
      (node (ref "LED21") (pin "GND") (pinfunction "GND_GND") (pintype "bidirectional"))
      (node (ref "LED22") (pin "GND") (pinfunction "GND_GND") (pintype "bidirectional"))
      (node (ref "LED23") (pin "GND") (pinfunction "GND_GND") (pintype "bidirectional"))
      (node (ref "LED24") (pin "GND") (pinfunction "GND_GND") (pintype "bidirectional"))
      (node (ref "LED25") (pin "GND") (pinfunction "GND_GND") (pintype "bidirectional"))
      (node (ref "LED26") (pin "GND") (pinfunction "GND_GND") (pintype "bidirectional"))
      (node (ref "LED27") (pin "GND") (pinfunction "GND_GND") (pintype "bidirectional"))
      (node (ref "LED28") (pin "GND") (pinfunction "GND_GND") (pintype "bidirectional"))
      (node (ref "LED29") (pin "GND") (pinfunction "GND_GND") (pintype "bidirectional"))
      (node (ref "LED3") (pin "GND") (pinfunction "GND_GND") (pintype "bidirectional"))
      (node (ref "LED30") (pin "GND") (pinfunction "GND_GND") (pintype "bidirectional"))
      (node (ref "LED31") (pin "GND") (pinfunction "GND_GND") (pintype "bidirectional"))
      (node (ref "LED32") (pin "GND") (pinfunction "GND_GND") (pintype "bidirectional"))
      (node (ref "LED33") (pin "GND") (pinfunction "GND_GND") (pintype "bidirectional"))
      (node (ref "LED34") (pin "GND") (pinfunction "GND_GND") (pintype "bidirectional"))
      (node (ref "LED35") (pin "GND") (pinfunction "GND_GND") (pintype "bidirectional"))
      (node (ref "LED36") (pin "GND") (pinfunction "GND_GND") (pintype "bidirectional"))
      (node (ref "LED37") (pin "GND") (pinfunction "GND_GND") (pintype "bidirectional"))
      (node (ref "LED38") (pin "GND") (pinfunction "GND_GND") (pintype "bidirectional"))
      (node (ref "LED39") (pin "GND") (pinfunction "GND_GND") (pintype "bidirectional"))
      (node (ref "LED4") (pin "GND") (pinfunction "GND_GND") (pintype "bidirectional"))
      (node (ref "LED40") (pin "GND") (pinfunction "GND_GND") (pintype "bidirectional"))
      (node (ref "LED41") (pin "GND") (pinfunction "GND_GND") (pintype "bidirectional"))
      (node (ref "LED42") (pin "GND") (pinfunction "GND_GND") (pintype "bidirectional"))
      (node (ref "LED43") (pin "GND") (pinfunction "GND_GND") (pintype "bidirectional"))
      (node (ref "LED44") (pin "GND") (pinfunction "GND_GND") (pintype "bidirectional"))
      (node (ref "LED45") (pin "GND") (pinfunction "GND_GND") (pintype "bidirectional"))
      (node (ref "LED46") (pin "GND") (pinfunction "GND_GND") (pintype "bidirectional"))
      (node (ref "LED47") (pin "GND") (pinfunction "GND_GND") (pintype "bidirectional"))
      (node (ref "LED48") (pin "GND") (pinfunction "GND_GND") (pintype "bidirectional"))
      (node (ref "LED49") (pin "GND") (pinfunction "GND_GND") (pintype "bidirectional"))
      (node (ref "LED5") (pin "GND") (pinfunction "GND_GND") (pintype "bidirectional"))
      (node (ref "LED50") (pin "GND") (pinfunction "GND_GND") (pintype "bidirectional"))
      (node (ref "LED51") (pin "GND") (pinfunction "GND_GND") (pintype "bidirectional"))
      (node (ref "LED52") (pin "GND") (pinfunction "GND_GND") (pintype "bidirectional"))
      (node (ref "LED53") (pin "GND") (pinfunction "GND_GND") (pintype "bidirectional"))
      (node (ref "LED54") (pin "GND") (pinfunction "GND_GND") (pintype "bidirectional"))
      (node (ref "LED55") (pin "GND") (pinfunction "GND_GND") (pintype "bidirectional"))
      (node (ref "LED56") (pin "GND") (pinfunction "GND_GND") (pintype "bidirectional"))
      (node (ref "LED57") (pin "GND") (pinfunction "GND_GND") (pintype "bidirectional"))
      (node (ref "LED58") (pin "GND") (pinfunction "GND_GND") (pintype "bidirectional"))
      (node (ref "LED59") (pin "GND") (pinfunction "GND_GND") (pintype "bidirectional"))
      (node (ref "LED6") (pin "GND") (pinfunction "GND_GND") (pintype "bidirectional"))
      (node (ref "LED60") (pin "GND") (pinfunction "GND_GND") (pintype "bidirectional"))
      (node (ref "LED61") (pin "GND") (pinfunction "GND_GND") (pintype "bidirectional"))
      (node (ref "LED62") (pin "GND") (pinfunction "GND_GND") (pintype "bidirectional"))
      (node (ref "LED63") (pin "GND") (pinfunction "GND_GND") (pintype "bidirectional"))
      (node (ref "LED64") (pin "GND") (pinfunction "GND_GND") (pintype "bidirectional"))
      (node (ref "LED7") (pin "GND") (pinfunction "GND_GND") (pintype "bidirectional"))
      (node (ref "LED8") (pin "GND") (pinfunction "GND_GND") (pintype "bidirectional"))
      (node (ref "LED9") (pin "GND") (pinfunction "GND_GND") (pintype "bidirectional"))
      (node (ref "MOSN0") (pin "2") (pinfunction "S_2") (pintype "bidirectional"))
      (node (ref "MOSN1") (pin "2") (pinfunction "S_2") (pintype "bidirectional"))
      (node (ref "MOSN2") (pin "2") (pinfunction "S_2") (pintype "bidirectional"))
      (node (ref "MOSN3") (pin "2") (pinfunction "S_2") (pintype "bidirectional"))
      (node (ref "MOSN4") (pin "2") (pinfunction "S_2") (pintype "bidirectional"))
      (node (ref "MOSN5") (pin "2") (pinfunction "S_2") (pintype "bidirectional"))
      (node (ref "MOSN6") (pin "2") (pinfunction "S_2") (pintype "bidirectional"))
      (node (ref "MOSN7") (pin "2") (pinfunction "S_2") (pintype "bidirectional"))
      (node (ref "M_C") (pin "7") (pinfunction "VEE_7") (pintype "bidirectional"))
      (node (ref "M_C") (pin "8") (pinfunction "GND_8") (pintype "bidirectional"))
      (node (ref "M_R") (pin "7") (pinfunction "VEE_7") (pintype "bidirectional"))
      (node (ref "M_R") (pin "8") (pinfunction "GND_8") (pintype "bidirectional"))
      (node (ref "PT_R1") (pin "1") (pinfunction "1_1") (pintype "passive"))
      (node (ref "PT_R10") (pin "1") (pinfunction "1_1") (pintype "passive"))
      (node (ref "PT_R11") (pin "1") (pinfunction "1_1") (pintype "passive"))
      (node (ref "PT_R12") (pin "1") (pinfunction "1_1") (pintype "passive"))
      (node (ref "PT_R13") (pin "1") (pinfunction "1_1") (pintype "passive"))
      (node (ref "PT_R14") (pin "1") (pinfunction "1_1") (pintype "passive"))
      (node (ref "PT_R15") (pin "1") (pinfunction "1_1") (pintype "passive"))
      (node (ref "PT_R16") (pin "1") (pinfunction "1_1") (pintype "passive"))
      (node (ref "PT_R17") (pin "1") (pinfunction "1_1") (pintype "passive"))
      (node (ref "PT_R18") (pin "1") (pinfunction "1_1") (pintype "passive"))
      (node (ref "PT_R19") (pin "1") (pinfunction "1_1") (pintype "passive"))
      (node (ref "PT_R2") (pin "1") (pinfunction "1_1") (pintype "passive"))
      (node (ref "PT_R20") (pin "1") (pinfunction "1_1") (pintype "passive"))
      (node (ref "PT_R21") (pin "1") (pinfunction "1_1") (pintype "passive"))
      (node (ref "PT_R22") (pin "1") (pinfunction "1_1") (pintype "passive"))
      (node (ref "PT_R23") (pin "1") (pinfunction "1_1") (pintype "passive"))
      (node (ref "PT_R24") (pin "1") (pinfunction "1_1") (pintype "passive"))
      (node (ref "PT_R25") (pin "1") (pinfunction "1_1") (pintype "passive"))
      (node (ref "PT_R26") (pin "1") (pinfunction "1_1") (pintype "passive"))
      (node (ref "PT_R27") (pin "1") (pinfunction "1_1") (pintype "passive"))
      (node (ref "PT_R28") (pin "1") (pinfunction "1_1") (pintype "passive"))
      (node (ref "PT_R29") (pin "1") (pinfunction "1_1") (pintype "passive"))
      (node (ref "PT_R3") (pin "1") (pinfunction "1_1") (pintype "passive"))
      (node (ref "PT_R30") (pin "1") (pinfunction "1_1") (pintype "passive"))
      (node (ref "PT_R31") (pin "1") (pinfunction "1_1") (pintype "passive"))
      (node (ref "PT_R32") (pin "1") (pinfunction "1_1") (pintype "passive"))
      (node (ref "PT_R33") (pin "1") (pinfunction "1_1") (pintype "passive"))
      (node (ref "PT_R34") (pin "1") (pinfunction "1_1") (pintype "passive"))
      (node (ref "PT_R35") (pin "1") (pinfunction "1_1") (pintype "passive"))
      (node (ref "PT_R36") (pin "1") (pinfunction "1_1") (pintype "passive"))
      (node (ref "PT_R37") (pin "1") (pinfunction "1_1") (pintype "passive"))
      (node (ref "PT_R38") (pin "1") (pinfunction "1_1") (pintype "passive"))
      (node (ref "PT_R39") (pin "1") (pinfunction "1_1") (pintype "passive"))
      (node (ref "PT_R4") (pin "1") (pinfunction "1_1") (pintype "passive"))
      (node (ref "PT_R40") (pin "1") (pinfunction "1_1") (pintype "passive"))
      (node (ref "PT_R41") (pin "1") (pinfunction "1_1") (pintype "passive"))
      (node (ref "PT_R42") (pin "1") (pinfunction "1_1") (pintype "passive"))
      (node (ref "PT_R43") (pin "1") (pinfunction "1_1") (pintype "passive"))
      (node (ref "PT_R44") (pin "1") (pinfunction "1_1") (pintype "passive"))
      (node (ref "PT_R45") (pin "1") (pinfunction "1_1") (pintype "passive"))
      (node (ref "PT_R46") (pin "1") (pinfunction "1_1") (pintype "passive"))
      (node (ref "PT_R47") (pin "1") (pinfunction "1_1") (pintype "passive"))
      (node (ref "PT_R48") (pin "1") (pinfunction "1_1") (pintype "passive"))
      (node (ref "PT_R49") (pin "1") (pinfunction "1_1") (pintype "passive"))
      (node (ref "PT_R5") (pin "1") (pinfunction "1_1") (pintype "passive"))
      (node (ref "PT_R50") (pin "1") (pinfunction "1_1") (pintype "passive"))
      (node (ref "PT_R51") (pin "1") (pinfunction "1_1") (pintype "passive"))
      (node (ref "PT_R52") (pin "1") (pinfunction "1_1") (pintype "passive"))
      (node (ref "PT_R53") (pin "1") (pinfunction "1_1") (pintype "passive"))
      (node (ref "PT_R54") (pin "1") (pinfunction "1_1") (pintype "passive"))
      (node (ref "PT_R55") (pin "1") (pinfunction "1_1") (pintype "passive"))
      (node (ref "PT_R56") (pin "1") (pinfunction "1_1") (pintype "passive"))
      (node (ref "PT_R57") (pin "1") (pinfunction "1_1") (pintype "passive"))
      (node (ref "PT_R58") (pin "1") (pinfunction "1_1") (pintype "passive"))
      (node (ref "PT_R59") (pin "1") (pinfunction "1_1") (pintype "passive"))
      (node (ref "PT_R6") (pin "1") (pinfunction "1_1") (pintype "passive"))
      (node (ref "PT_R60") (pin "1") (pinfunction "1_1") (pintype "passive"))
      (node (ref "PT_R61") (pin "1") (pinfunction "1_1") (pintype "passive"))
      (node (ref "PT_R62") (pin "1") (pinfunction "1_1") (pintype "passive"))
      (node (ref "PT_R63") (pin "1") (pinfunction "1_1") (pintype "passive"))
      (node (ref "PT_R64") (pin "1") (pinfunction "1_1") (pintype "passive"))
      (node (ref "PT_R7") (pin "1") (pinfunction "1_1") (pintype "passive"))
      (node (ref "PT_R8") (pin "1") (pinfunction "1_1") (pintype "passive"))
      (node (ref "PT_R9") (pin "1") (pinfunction "1_1") (pintype "passive"))
      (node (ref "ROUT0") (pin "1") (pinfunction "1_1") (pintype "passive"))
      (node (ref "ROUT1") (pin "1") (pinfunction "1_1") (pintype "passive"))
      (node (ref "Rcg0") (pin "2") (pinfunction "2_2") (pintype "passive"))
      (node (ref "Rcg1") (pin "2") (pinfunction "2_2") (pintype "passive"))
      (node (ref "Rcg2") (pin "2") (pinfunction "2_2") (pintype "passive"))
      (node (ref "Rcg3") (pin "2") (pinfunction "2_2") (pintype "passive"))
      (node (ref "Rcg4") (pin "2") (pinfunction "2_2") (pintype "passive"))
      (node (ref "Rcg5") (pin "2") (pinfunction "2_2") (pintype "passive"))
      (node (ref "Rcg6") (pin "2") (pinfunction "2_2") (pintype "passive"))
      (node (ref "Rcg7") (pin "2") (pinfunction "2_2") (pintype "passive"))
    )
    (net (code "53") (name "Net-(H1-A11)") (class "Default")
      (node (ref "810_0") (pin "2") (pinfunction "2_2") (pintype "passive"))
      (node (ref "H1") (pin "13") (pinfunction "A11_13") (pintype "passive"))
    )
    (net (code "54") (name "Net-(H1-A12)") (class "Default")
      (node (ref "810_2") (pin "2") (pinfunction "2_2") (pintype "passive"))
      (node (ref "H1") (pin "12") (pinfunction "A12_12") (pintype "passive"))
    )
    (net (code "55") (name "Net-(H1-A15)") (class "Default")
      (node (ref "319_0") (pin "1") (pinfunction "1_1") (pintype "passive"))
      (node (ref "H1") (pin "11") (pinfunction "A15_11") (pintype "passive"))
    )
    (net (code "56") (name "Net-(H1-B3)") (class "Default")
      (node (ref "319_2") (pin "1") (pinfunction "1_1") (pintype "passive"))
      (node (ref "H1") (pin "10") (pinfunction "B3_10") (pintype "passive"))
    )
    (net (code "57") (name "Net-(IR1-C)") (class "Default")
      (node (ref "IR1") (pin "2") (pinfunction "C_2") (pintype "passive"))
      (node (ref "IR_R1") (pin "2") (pinfunction "2_2") (pintype "passive"))
    )
    (net (code "58") (name "Net-(IR2-C)") (class "Default")
      (node (ref "IR2") (pin "2") (pinfunction "C_2") (pintype "passive"))
      (node (ref "IR_R2") (pin "2") (pinfunction "2_2") (pintype "passive"))
    )
    (net (code "59") (name "Net-(IR3-C)") (class "Default")
      (node (ref "IR3") (pin "2") (pinfunction "C_2") (pintype "passive"))
      (node (ref "IR_R3") (pin "2") (pinfunction "2_2") (pintype "passive"))
    )
    (net (code "60") (name "Net-(IR4-C)") (class "Default")
      (node (ref "IR4") (pin "2") (pinfunction "C_2") (pintype "passive"))
      (node (ref "IR_R4") (pin "2") (pinfunction "2_2") (pintype "passive"))
    )
    (net (code "61") (name "Net-(IR5-C)") (class "Default")
      (node (ref "IR5") (pin "2") (pinfunction "C_2") (pintype "passive"))
      (node (ref "IR_R5") (pin "2") (pinfunction "2_2") (pintype "passive"))
    )
    (net (code "62") (name "Net-(IR6-C)") (class "Default")
      (node (ref "IR6") (pin "2") (pinfunction "C_2") (pintype "passive"))
      (node (ref "IR_R6") (pin "2") (pinfunction "2_2") (pintype "passive"))
    )
    (net (code "63") (name "Net-(IR7-C)") (class "Default")
      (node (ref "IR7") (pin "2") (pinfunction "C_2") (pintype "passive"))
      (node (ref "IR_R7") (pin "2") (pinfunction "2_2") (pintype "passive"))
    )
    (net (code "64") (name "Net-(IR8-C)") (class "Default")
      (node (ref "IR8") (pin "2") (pinfunction "C_2") (pintype "passive"))
      (node (ref "IR_R8") (pin "2") (pinfunction "2_2") (pintype "passive"))
    )
    (net (code "65") (name "Net-(IR9-C)") (class "Default")
      (node (ref "IR9") (pin "2") (pinfunction "C_2") (pintype "passive"))
      (node (ref "IR_R9") (pin "2") (pinfunction "2_2") (pintype "passive"))
    )
    (net (code "66") (name "Net-(IR10-C)") (class "Default")
      (node (ref "IR10") (pin "2") (pinfunction "C_2") (pintype "passive"))
      (node (ref "IR_R10") (pin "2") (pinfunction "2_2") (pintype "passive"))
    )
    (net (code "67") (name "Net-(IR11-C)") (class "Default")
      (node (ref "IR11") (pin "2") (pinfunction "C_2") (pintype "passive"))
      (node (ref "IR_R11") (pin "2") (pinfunction "2_2") (pintype "passive"))
    )
    (net (code "68") (name "Net-(IR12-C)") (class "Default")
      (node (ref "IR12") (pin "2") (pinfunction "C_2") (pintype "passive"))
      (node (ref "IR_R12") (pin "2") (pinfunction "2_2") (pintype "passive"))
    )
    (net (code "69") (name "Net-(IR13-C)") (class "Default")
      (node (ref "IR13") (pin "2") (pinfunction "C_2") (pintype "passive"))
      (node (ref "IR_R13") (pin "2") (pinfunction "2_2") (pintype "passive"))
    )
    (net (code "70") (name "Net-(IR14-C)") (class "Default")
      (node (ref "IR14") (pin "2") (pinfunction "C_2") (pintype "passive"))
      (node (ref "IR_R14") (pin "2") (pinfunction "2_2") (pintype "passive"))
    )
    (net (code "71") (name "Net-(IR15-C)") (class "Default")
      (node (ref "IR15") (pin "2") (pinfunction "C_2") (pintype "passive"))
      (node (ref "IR_R15") (pin "2") (pinfunction "2_2") (pintype "passive"))
    )
    (net (code "72") (name "Net-(IR16-C)") (class "Default")
      (node (ref "IR16") (pin "2") (pinfunction "C_2") (pintype "passive"))
      (node (ref "IR_R16") (pin "2") (pinfunction "2_2") (pintype "passive"))
    )
    (net (code "73") (name "Net-(IR17-C)") (class "Default")
      (node (ref "IR17") (pin "2") (pinfunction "C_2") (pintype "passive"))
      (node (ref "IR_R17") (pin "2") (pinfunction "2_2") (pintype "passive"))
    )
    (net (code "74") (name "Net-(IR18-C)") (class "Default")
      (node (ref "IR18") (pin "2") (pinfunction "C_2") (pintype "passive"))
      (node (ref "IR_R18") (pin "2") (pinfunction "2_2") (pintype "passive"))
    )
    (net (code "75") (name "Net-(IR19-C)") (class "Default")
      (node (ref "IR19") (pin "2") (pinfunction "C_2") (pintype "passive"))
      (node (ref "IR_R19") (pin "2") (pinfunction "2_2") (pintype "passive"))
    )
    (net (code "76") (name "Net-(IR20-C)") (class "Default")
      (node (ref "IR20") (pin "2") (pinfunction "C_2") (pintype "passive"))
      (node (ref "IR_R20") (pin "2") (pinfunction "2_2") (pintype "passive"))
    )
    (net (code "77") (name "Net-(IR21-C)") (class "Default")
      (node (ref "IR21") (pin "2") (pinfunction "C_2") (pintype "passive"))
      (node (ref "IR_R21") (pin "2") (pinfunction "2_2") (pintype "passive"))
    )
    (net (code "78") (name "Net-(IR22-C)") (class "Default")
      (node (ref "IR22") (pin "2") (pinfunction "C_2") (pintype "passive"))
      (node (ref "IR_R22") (pin "2") (pinfunction "2_2") (pintype "passive"))
    )
    (net (code "79") (name "Net-(IR23-C)") (class "Default")
      (node (ref "IR23") (pin "2") (pinfunction "C_2") (pintype "passive"))
      (node (ref "IR_R23") (pin "2") (pinfunction "2_2") (pintype "passive"))
    )
    (net (code "80") (name "Net-(IR24-C)") (class "Default")
      (node (ref "IR24") (pin "2") (pinfunction "C_2") (pintype "passive"))
      (node (ref "IR_R24") (pin "2") (pinfunction "2_2") (pintype "passive"))
    )
    (net (code "81") (name "Net-(IR25-C)") (class "Default")
      (node (ref "IR25") (pin "2") (pinfunction "C_2") (pintype "passive"))
      (node (ref "IR_R25") (pin "2") (pinfunction "2_2") (pintype "passive"))
    )
    (net (code "82") (name "Net-(IR26-C)") (class "Default")
      (node (ref "IR26") (pin "2") (pinfunction "C_2") (pintype "passive"))
      (node (ref "IR_R26") (pin "2") (pinfunction "2_2") (pintype "passive"))
    )
    (net (code "83") (name "Net-(IR27-C)") (class "Default")
      (node (ref "IR27") (pin "2") (pinfunction "C_2") (pintype "passive"))
      (node (ref "IR_R27") (pin "2") (pinfunction "2_2") (pintype "passive"))
    )
    (net (code "84") (name "Net-(IR28-C)") (class "Default")
      (node (ref "IR28") (pin "2") (pinfunction "C_2") (pintype "passive"))
      (node (ref "IR_R28") (pin "2") (pinfunction "2_2") (pintype "passive"))
    )
    (net (code "85") (name "Net-(IR29-C)") (class "Default")
      (node (ref "IR29") (pin "2") (pinfunction "C_2") (pintype "passive"))
      (node (ref "IR_R29") (pin "2") (pinfunction "2_2") (pintype "passive"))
    )
    (net (code "86") (name "Net-(IR30-C)") (class "Default")
      (node (ref "IR30") (pin "2") (pinfunction "C_2") (pintype "passive"))
      (node (ref "IR_R30") (pin "2") (pinfunction "2_2") (pintype "passive"))
    )
    (net (code "87") (name "Net-(IR31-C)") (class "Default")
      (node (ref "IR31") (pin "2") (pinfunction "C_2") (pintype "passive"))
      (node (ref "IR_R31") (pin "2") (pinfunction "2_2") (pintype "passive"))
    )
    (net (code "88") (name "Net-(IR32-C)") (class "Default")
      (node (ref "IR32") (pin "2") (pinfunction "C_2") (pintype "passive"))
      (node (ref "IR_R32") (pin "2") (pinfunction "2_2") (pintype "passive"))
    )
    (net (code "89") (name "Net-(IR33-C)") (class "Default")
      (node (ref "IR33") (pin "2") (pinfunction "C_2") (pintype "passive"))
      (node (ref "IR_R33") (pin "2") (pinfunction "2_2") (pintype "passive"))
    )
    (net (code "90") (name "Net-(IR34-C)") (class "Default")
      (node (ref "IR34") (pin "2") (pinfunction "C_2") (pintype "passive"))
      (node (ref "IR_R34") (pin "2") (pinfunction "2_2") (pintype "passive"))
    )
    (net (code "91") (name "Net-(IR35-C)") (class "Default")
      (node (ref "IR35") (pin "2") (pinfunction "C_2") (pintype "passive"))
      (node (ref "IR_R35") (pin "2") (pinfunction "2_2") (pintype "passive"))
    )
    (net (code "92") (name "Net-(IR36-C)") (class "Default")
      (node (ref "IR36") (pin "2") (pinfunction "C_2") (pintype "passive"))
      (node (ref "IR_R36") (pin "2") (pinfunction "2_2") (pintype "passive"))
    )
    (net (code "93") (name "Net-(IR37-C)") (class "Default")
      (node (ref "IR37") (pin "2") (pinfunction "C_2") (pintype "passive"))
      (node (ref "IR_R37") (pin "2") (pinfunction "2_2") (pintype "passive"))
    )
    (net (code "94") (name "Net-(IR38-C)") (class "Default")
      (node (ref "IR38") (pin "2") (pinfunction "C_2") (pintype "passive"))
      (node (ref "IR_R38") (pin "2") (pinfunction "2_2") (pintype "passive"))
    )
    (net (code "95") (name "Net-(IR39-C)") (class "Default")
      (node (ref "IR39") (pin "2") (pinfunction "C_2") (pintype "passive"))
      (node (ref "IR_R39") (pin "2") (pinfunction "2_2") (pintype "passive"))
    )
    (net (code "96") (name "Net-(IR40-C)") (class "Default")
      (node (ref "IR40") (pin "2") (pinfunction "C_2") (pintype "passive"))
      (node (ref "IR_R40") (pin "2") (pinfunction "2_2") (pintype "passive"))
    )
    (net (code "97") (name "Net-(IR41-C)") (class "Default")
      (node (ref "IR41") (pin "2") (pinfunction "C_2") (pintype "passive"))
      (node (ref "IR_R41") (pin "2") (pinfunction "2_2") (pintype "passive"))
    )
    (net (code "98") (name "Net-(IR42-C)") (class "Default")
      (node (ref "IR42") (pin "2") (pinfunction "C_2") (pintype "passive"))
      (node (ref "IR_R42") (pin "2") (pinfunction "2_2") (pintype "passive"))
    )
    (net (code "99") (name "Net-(IR43-C)") (class "Default")
      (node (ref "IR43") (pin "2") (pinfunction "C_2") (pintype "passive"))
      (node (ref "IR_R43") (pin "2") (pinfunction "2_2") (pintype "passive"))
    )
    (net (code "100") (name "Net-(IR44-C)") (class "Default")
      (node (ref "IR44") (pin "2") (pinfunction "C_2") (pintype "passive"))
      (node (ref "IR_R44") (pin "2") (pinfunction "2_2") (pintype "passive"))
    )
    (net (code "101") (name "Net-(IR45-C)") (class "Default")
      (node (ref "IR45") (pin "2") (pinfunction "C_2") (pintype "passive"))
      (node (ref "IR_R45") (pin "2") (pinfunction "2_2") (pintype "passive"))
    )
    (net (code "102") (name "Net-(IR46-C)") (class "Default")
      (node (ref "IR46") (pin "2") (pinfunction "C_2") (pintype "passive"))
      (node (ref "IR_R46") (pin "2") (pinfunction "2_2") (pintype "passive"))
    )
    (net (code "103") (name "Net-(IR47-C)") (class "Default")
      (node (ref "IR47") (pin "2") (pinfunction "C_2") (pintype "passive"))
      (node (ref "IR_R47") (pin "2") (pinfunction "2_2") (pintype "passive"))
    )
    (net (code "104") (name "Net-(IR48-C)") (class "Default")
      (node (ref "IR48") (pin "2") (pinfunction "C_2") (pintype "passive"))
      (node (ref "IR_R48") (pin "2") (pinfunction "2_2") (pintype "passive"))
    )
    (net (code "105") (name "Net-(IR49-C)") (class "Default")
      (node (ref "IR49") (pin "2") (pinfunction "C_2") (pintype "passive"))
      (node (ref "IR_R49") (pin "2") (pinfunction "2_2") (pintype "passive"))
    )
    (net (code "106") (name "Net-(IR50-C)") (class "Default")
      (node (ref "IR50") (pin "2") (pinfunction "C_2") (pintype "passive"))
      (node (ref "IR_R50") (pin "2") (pinfunction "2_2") (pintype "passive"))
    )
    (net (code "107") (name "Net-(IR51-C)") (class "Default")
      (node (ref "IR51") (pin "2") (pinfunction "C_2") (pintype "passive"))
      (node (ref "IR_R51") (pin "2") (pinfunction "2_2") (pintype "passive"))
    )
    (net (code "108") (name "Net-(IR52-C)") (class "Default")
      (node (ref "IR52") (pin "2") (pinfunction "C_2") (pintype "passive"))
      (node (ref "IR_R52") (pin "2") (pinfunction "2_2") (pintype "passive"))
    )
    (net (code "109") (name "Net-(IR53-C)") (class "Default")
      (node (ref "IR53") (pin "2") (pinfunction "C_2") (pintype "passive"))
      (node (ref "IR_R53") (pin "2") (pinfunction "2_2") (pintype "passive"))
    )
    (net (code "110") (name "Net-(IR54-C)") (class "Default")
      (node (ref "IR54") (pin "2") (pinfunction "C_2") (pintype "passive"))
      (node (ref "IR_R54") (pin "2") (pinfunction "2_2") (pintype "passive"))
    )
    (net (code "111") (name "Net-(IR55-C)") (class "Default")
      (node (ref "IR55") (pin "2") (pinfunction "C_2") (pintype "passive"))
      (node (ref "IR_R55") (pin "2") (pinfunction "2_2") (pintype "passive"))
    )
    (net (code "112") (name "Net-(IR56-C)") (class "Default")
      (node (ref "IR56") (pin "2") (pinfunction "C_2") (pintype "passive"))
      (node (ref "IR_R56") (pin "2") (pinfunction "2_2") (pintype "passive"))
    )
    (net (code "113") (name "Net-(IR57-C)") (class "Default")
      (node (ref "IR57") (pin "2") (pinfunction "C_2") (pintype "passive"))
      (node (ref "IR_R57") (pin "2") (pinfunction "2_2") (pintype "passive"))
    )
    (net (code "114") (name "Net-(IR58-C)") (class "Default")
      (node (ref "IR58") (pin "2") (pinfunction "C_2") (pintype "passive"))
      (node (ref "IR_R58") (pin "2") (pinfunction "2_2") (pintype "passive"))
    )
    (net (code "115") (name "Net-(IR59-C)") (class "Default")
      (node (ref "IR59") (pin "2") (pinfunction "C_2") (pintype "passive"))
      (node (ref "IR_R59") (pin "2") (pinfunction "2_2") (pintype "passive"))
    )
    (net (code "116") (name "Net-(IR60-C)") (class "Default")
      (node (ref "IR60") (pin "2") (pinfunction "C_2") (pintype "passive"))
      (node (ref "IR_R60") (pin "2") (pinfunction "2_2") (pintype "passive"))
    )
    (net (code "117") (name "Net-(IR61-C)") (class "Default")
      (node (ref "IR61") (pin "2") (pinfunction "C_2") (pintype "passive"))
      (node (ref "IR_R61") (pin "2") (pinfunction "2_2") (pintype "passive"))
    )
    (net (code "118") (name "Net-(IR62-C)") (class "Default")
      (node (ref "IR62") (pin "2") (pinfunction "C_2") (pintype "passive"))
      (node (ref "IR_R62") (pin "2") (pinfunction "2_2") (pintype "passive"))
    )
    (net (code "119") (name "Net-(IR63-C)") (class "Default")
      (node (ref "IR63") (pin "2") (pinfunction "C_2") (pintype "passive"))
      (node (ref "IR_R63") (pin "2") (pinfunction "2_2") (pintype "passive"))
    )
    (net (code "120") (name "Net-(IR64-C)") (class "Default")
      (node (ref "IR64") (pin "2") (pinfunction "C_2") (pintype "passive"))
      (node (ref "IR_R64") (pin "2") (pinfunction "2_2") (pintype "passive"))
    )
    (net (code "121") (name "Net-(LED1-PadCKO)") (class "Default")
      (node (ref "LED1") (pin "CKO") (pinfunction "CKO_CKO") (pintype "bidirectional"))
      (node (ref "LED2") (pin "CKI") (pinfunction "CKI_CKI") (pintype "bidirectional"))
    )
    (net (code "122") (name "Net-(LED1-PadSDO)") (class "Default")
      (node (ref "LED1") (pin "SDO") (pinfunction "SDO_SDO") (pintype "bidirectional"))
      (node (ref "LED2") (pin "SDI") (pinfunction "SDI_SDI") (pintype "bidirectional"))
    )
    (net (code "123") (name "Net-(LED2-PadCKO)") (class "Default")
      (node (ref "LED2") (pin "CKO") (pinfunction "CKO_CKO") (pintype "bidirectional"))
      (node (ref "LED3") (pin "CKI") (pinfunction "CKI_CKI") (pintype "bidirectional"))
    )
    (net (code "124") (name "Net-(LED2-PadSDO)") (class "Default")
      (node (ref "LED2") (pin "SDO") (pinfunction "SDO_SDO") (pintype "bidirectional"))
      (node (ref "LED3") (pin "SDI") (pinfunction "SDI_SDI") (pintype "bidirectional"))
    )
    (net (code "125") (name "Net-(LED3-PadCKO)") (class "Default")
      (node (ref "LED3") (pin "CKO") (pinfunction "CKO_CKO") (pintype "bidirectional"))
      (node (ref "LED4") (pin "CKI") (pinfunction "CKI_CKI") (pintype "bidirectional"))
    )
    (net (code "126") (name "Net-(LED3-PadSDO)") (class "Default")
      (node (ref "LED3") (pin "SDO") (pinfunction "SDO_SDO") (pintype "bidirectional"))
      (node (ref "LED4") (pin "SDI") (pinfunction "SDI_SDI") (pintype "bidirectional"))
    )
    (net (code "127") (name "Net-(LED4-PadCKO)") (class "Default")
      (node (ref "LED4") (pin "CKO") (pinfunction "CKO_CKO") (pintype "bidirectional"))
      (node (ref "LED5") (pin "CKI") (pinfunction "CKI_CKI") (pintype "bidirectional"))
    )
    (net (code "128") (name "Net-(LED4-PadSDO)") (class "Default")
      (node (ref "LED4") (pin "SDO") (pinfunction "SDO_SDO") (pintype "bidirectional"))
      (node (ref "LED5") (pin "SDI") (pinfunction "SDI_SDI") (pintype "bidirectional"))
    )
    (net (code "129") (name "Net-(LED5-PadCKO)") (class "Default")
      (node (ref "LED5") (pin "CKO") (pinfunction "CKO_CKO") (pintype "bidirectional"))
      (node (ref "LED6") (pin "CKI") (pinfunction "CKI_CKI") (pintype "bidirectional"))
    )
    (net (code "130") (name "Net-(LED5-PadSDO)") (class "Default")
      (node (ref "LED5") (pin "SDO") (pinfunction "SDO_SDO") (pintype "bidirectional"))
      (node (ref "LED6") (pin "SDI") (pinfunction "SDI_SDI") (pintype "bidirectional"))
    )
    (net (code "131") (name "Net-(LED6-PadCKO)") (class "Default")
      (node (ref "LED6") (pin "CKO") (pinfunction "CKO_CKO") (pintype "bidirectional"))
      (node (ref "LED7") (pin "CKI") (pinfunction "CKI_CKI") (pintype "bidirectional"))
    )
    (net (code "132") (name "Net-(LED6-PadSDO)") (class "Default")
      (node (ref "LED6") (pin "SDO") (pinfunction "SDO_SDO") (pintype "bidirectional"))
      (node (ref "LED7") (pin "SDI") (pinfunction "SDI_SDI") (pintype "bidirectional"))
    )
    (net (code "133") (name "Net-(LED7-PadCKO)") (class "Default")
      (node (ref "LED7") (pin "CKO") (pinfunction "CKO_CKO") (pintype "bidirectional"))
      (node (ref "LED8") (pin "CKI") (pinfunction "CKI_CKI") (pintype "bidirectional"))
    )
    (net (code "134") (name "Net-(LED7-PadSDO)") (class "Default")
      (node (ref "LED7") (pin "SDO") (pinfunction "SDO_SDO") (pintype "bidirectional"))
      (node (ref "LED8") (pin "SDI") (pinfunction "SDI_SDI") (pintype "bidirectional"))
    )
    (net (code "135") (name "Net-(LED10-PadCKI)") (class "Default")
      (node (ref "LED10") (pin "CKI") (pinfunction "CKI_CKI") (pintype "bidirectional"))
      (node (ref "LED11") (pin "CKO") (pinfunction "CKO_CKO") (pintype "bidirectional"))
    )
    (net (code "136") (name "Net-(LED10-PadCKO)") (class "Default")
      (node (ref "LED10") (pin "CKO") (pinfunction "CKO_CKO") (pintype "bidirectional"))
      (node (ref "LED9") (pin "CKI") (pinfunction "CKI_CKI") (pintype "bidirectional"))
    )
    (net (code "137") (name "Net-(LED10-PadSDI)") (class "Default")
      (node (ref "LED10") (pin "SDI") (pinfunction "SDI_SDI") (pintype "bidirectional"))
      (node (ref "LED11") (pin "SDO") (pinfunction "SDO_SDO") (pintype "bidirectional"))
    )
    (net (code "138") (name "Net-(LED10-PadSDO)") (class "Default")
      (node (ref "LED10") (pin "SDO") (pinfunction "SDO_SDO") (pintype "bidirectional"))
      (node (ref "LED9") (pin "SDI") (pinfunction "SDI_SDI") (pintype "bidirectional"))
    )
    (net (code "139") (name "Net-(LED11-PadCKI)") (class "Default")
      (node (ref "LED11") (pin "CKI") (pinfunction "CKI_CKI") (pintype "bidirectional"))
      (node (ref "LED12") (pin "CKO") (pinfunction "CKO_CKO") (pintype "bidirectional"))
    )
    (net (code "140") (name "Net-(LED11-PadSDI)") (class "Default")
      (node (ref "LED11") (pin "SDI") (pinfunction "SDI_SDI") (pintype "bidirectional"))
      (node (ref "LED12") (pin "SDO") (pinfunction "SDO_SDO") (pintype "bidirectional"))
    )
    (net (code "141") (name "Net-(LED12-PadCKI)") (class "Default")
      (node (ref "LED12") (pin "CKI") (pinfunction "CKI_CKI") (pintype "bidirectional"))
      (node (ref "LED13") (pin "CKO") (pinfunction "CKO_CKO") (pintype "bidirectional"))
    )
    (net (code "142") (name "Net-(LED12-PadSDI)") (class "Default")
      (node (ref "LED12") (pin "SDI") (pinfunction "SDI_SDI") (pintype "bidirectional"))
      (node (ref "LED13") (pin "SDO") (pinfunction "SDO_SDO") (pintype "bidirectional"))
    )
    (net (code "143") (name "Net-(LED13-PadCKI)") (class "Default")
      (node (ref "LED13") (pin "CKI") (pinfunction "CKI_CKI") (pintype "bidirectional"))
      (node (ref "LED14") (pin "CKO") (pinfunction "CKO_CKO") (pintype "bidirectional"))
    )
    (net (code "144") (name "Net-(LED13-PadSDI)") (class "Default")
      (node (ref "LED13") (pin "SDI") (pinfunction "SDI_SDI") (pintype "bidirectional"))
      (node (ref "LED14") (pin "SDO") (pinfunction "SDO_SDO") (pintype "bidirectional"))
    )
    (net (code "145") (name "Net-(LED14-PadCKI)") (class "Default")
      (node (ref "LED14") (pin "CKI") (pinfunction "CKI_CKI") (pintype "bidirectional"))
      (node (ref "LED15") (pin "CKO") (pinfunction "CKO_CKO") (pintype "bidirectional"))
    )
    (net (code "146") (name "Net-(LED14-PadSDI)") (class "Default")
      (node (ref "LED14") (pin "SDI") (pinfunction "SDI_SDI") (pintype "bidirectional"))
      (node (ref "LED15") (pin "SDO") (pinfunction "SDO_SDO") (pintype "bidirectional"))
    )
    (net (code "147") (name "Net-(LED15-PadCKI)") (class "Default")
      (node (ref "LED15") (pin "CKI") (pinfunction "CKI_CKI") (pintype "bidirectional"))
      (node (ref "LED16") (pin "CKO") (pinfunction "CKO_CKO") (pintype "bidirectional"))
    )
    (net (code "148") (name "Net-(LED15-PadSDI)") (class "Default")
      (node (ref "LED15") (pin "SDI") (pinfunction "SDI_SDI") (pintype "bidirectional"))
      (node (ref "LED16") (pin "SDO") (pinfunction "SDO_SDO") (pintype "bidirectional"))
    )
    (net (code "149") (name "Net-(LED16-PadCKI)") (class "Default")
      (node (ref "LED16") (pin "CKI") (pinfunction "CKI_CKI") (pintype "bidirectional"))
      (node (ref "LED8") (pin "CKO") (pinfunction "CKO_CKO") (pintype "bidirectional"))
    )
    (net (code "150") (name "Net-(LED16-PadSDI)") (class "Default")
      (node (ref "LED16") (pin "SDI") (pinfunction "SDI_SDI") (pintype "bidirectional"))
      (node (ref "LED8") (pin "SDO") (pinfunction "SDO_SDO") (pintype "bidirectional"))
    )
    (net (code "151") (name "Net-(LED17-PadCKI)") (class "Default")
      (node (ref "LED17") (pin "CKI") (pinfunction "CKI_CKI") (pintype "bidirectional"))
      (node (ref "LED9") (pin "CKO") (pinfunction "CKO_CKO") (pintype "bidirectional"))
    )
    (net (code "152") (name "Net-(LED17-PadCKO)") (class "Default")
      (node (ref "LED17") (pin "CKO") (pinfunction "CKO_CKO") (pintype "bidirectional"))
      (node (ref "LED18") (pin "CKI") (pinfunction "CKI_CKI") (pintype "bidirectional"))
    )
    (net (code "153") (name "Net-(LED17-PadSDI)") (class "Default")
      (node (ref "LED17") (pin "SDI") (pinfunction "SDI_SDI") (pintype "bidirectional"))
      (node (ref "LED9") (pin "SDO") (pinfunction "SDO_SDO") (pintype "bidirectional"))
    )
    (net (code "154") (name "Net-(LED17-PadSDO)") (class "Default")
      (node (ref "LED17") (pin "SDO") (pinfunction "SDO_SDO") (pintype "bidirectional"))
      (node (ref "LED18") (pin "SDI") (pinfunction "SDI_SDI") (pintype "bidirectional"))
    )
    (net (code "155") (name "Net-(LED18-PadCKO)") (class "Default")
      (node (ref "LED18") (pin "CKO") (pinfunction "CKO_CKO") (pintype "bidirectional"))
      (node (ref "LED19") (pin "CKI") (pinfunction "CKI_CKI") (pintype "bidirectional"))
    )
    (net (code "156") (name "Net-(LED18-PadSDO)") (class "Default")
      (node (ref "LED18") (pin "SDO") (pinfunction "SDO_SDO") (pintype "bidirectional"))
      (node (ref "LED19") (pin "SDI") (pinfunction "SDI_SDI") (pintype "bidirectional"))
    )
    (net (code "157") (name "Net-(LED19-PadCKO)") (class "Default")
      (node (ref "LED19") (pin "CKO") (pinfunction "CKO_CKO") (pintype "bidirectional"))
      (node (ref "LED20") (pin "CKI") (pinfunction "CKI_CKI") (pintype "bidirectional"))
    )
    (net (code "158") (name "Net-(LED19-PadSDO)") (class "Default")
      (node (ref "LED19") (pin "SDO") (pinfunction "SDO_SDO") (pintype "bidirectional"))
      (node (ref "LED20") (pin "SDI") (pinfunction "SDI_SDI") (pintype "bidirectional"))
    )
    (net (code "159") (name "Net-(LED20-PadCKO)") (class "Default")
      (node (ref "LED20") (pin "CKO") (pinfunction "CKO_CKO") (pintype "bidirectional"))
      (node (ref "LED21") (pin "CKI") (pinfunction "CKI_CKI") (pintype "bidirectional"))
    )
    (net (code "160") (name "Net-(LED20-PadSDO)") (class "Default")
      (node (ref "LED20") (pin "SDO") (pinfunction "SDO_SDO") (pintype "bidirectional"))
      (node (ref "LED21") (pin "SDI") (pinfunction "SDI_SDI") (pintype "bidirectional"))
    )
    (net (code "161") (name "Net-(LED21-PadCKO)") (class "Default")
      (node (ref "LED21") (pin "CKO") (pinfunction "CKO_CKO") (pintype "bidirectional"))
      (node (ref "LED22") (pin "CKI") (pinfunction "CKI_CKI") (pintype "bidirectional"))
    )
    (net (code "162") (name "Net-(LED21-PadSDO)") (class "Default")
      (node (ref "LED21") (pin "SDO") (pinfunction "SDO_SDO") (pintype "bidirectional"))
      (node (ref "LED22") (pin "SDI") (pinfunction "SDI_SDI") (pintype "bidirectional"))
    )
    (net (code "163") (name "Net-(LED22-PadCKO)") (class "Default")
      (node (ref "LED22") (pin "CKO") (pinfunction "CKO_CKO") (pintype "bidirectional"))
      (node (ref "LED23") (pin "CKI") (pinfunction "CKI_CKI") (pintype "bidirectional"))
    )
    (net (code "164") (name "Net-(LED22-PadSDO)") (class "Default")
      (node (ref "LED22") (pin "SDO") (pinfunction "SDO_SDO") (pintype "bidirectional"))
      (node (ref "LED23") (pin "SDI") (pinfunction "SDI_SDI") (pintype "bidirectional"))
    )
    (net (code "165") (name "Net-(LED23-PadCKO)") (class "Default")
      (node (ref "LED23") (pin "CKO") (pinfunction "CKO_CKO") (pintype "bidirectional"))
      (node (ref "LED24") (pin "CKI") (pinfunction "CKI_CKI") (pintype "bidirectional"))
    )
    (net (code "166") (name "Net-(LED23-PadSDO)") (class "Default")
      (node (ref "LED23") (pin "SDO") (pinfunction "SDO_SDO") (pintype "bidirectional"))
      (node (ref "LED24") (pin "SDI") (pinfunction "SDI_SDI") (pintype "bidirectional"))
    )
    (net (code "167") (name "Net-(LED24-PadCKO)") (class "Default")
      (node (ref "LED24") (pin "CKO") (pinfunction "CKO_CKO") (pintype "bidirectional"))
      (node (ref "LED32") (pin "CKI") (pinfunction "CKI_CKI") (pintype "bidirectional"))
    )
    (net (code "168") (name "Net-(LED24-PadSDO)") (class "Default")
      (node (ref "LED24") (pin "SDO") (pinfunction "SDO_SDO") (pintype "bidirectional"))
      (node (ref "LED32") (pin "SDI") (pinfunction "SDI_SDI") (pintype "bidirectional"))
    )
    (net (code "169") (name "Net-(LED25-PadCKI)") (class "Default")
      (node (ref "LED25") (pin "CKI") (pinfunction "CKI_CKI") (pintype "bidirectional"))
      (node (ref "LED26") (pin "CKO") (pinfunction "CKO_CKO") (pintype "bidirectional"))
    )
    (net (code "170") (name "Net-(LED25-PadCKO)") (class "Default")
      (node (ref "LED25") (pin "CKO") (pinfunction "CKO_CKO") (pintype "bidirectional"))
      (node (ref "LED33") (pin "CKI") (pinfunction "CKI_CKI") (pintype "bidirectional"))
    )
    (net (code "171") (name "Net-(LED25-PadSDI)") (class "Default")
      (node (ref "LED25") (pin "SDI") (pinfunction "SDI_SDI") (pintype "bidirectional"))
      (node (ref "LED26") (pin "SDO") (pinfunction "SDO_SDO") (pintype "bidirectional"))
    )
    (net (code "172") (name "Net-(LED25-PadSDO)") (class "Default")
      (node (ref "LED25") (pin "SDO") (pinfunction "SDO_SDO") (pintype "bidirectional"))
      (node (ref "LED33") (pin "SDI") (pinfunction "SDI_SDI") (pintype "bidirectional"))
    )
    (net (code "173") (name "Net-(LED26-PadCKI)") (class "Default")
      (node (ref "LED26") (pin "CKI") (pinfunction "CKI_CKI") (pintype "bidirectional"))
      (node (ref "LED27") (pin "CKO") (pinfunction "CKO_CKO") (pintype "bidirectional"))
    )
    (net (code "174") (name "Net-(LED26-PadSDI)") (class "Default")
      (node (ref "LED26") (pin "SDI") (pinfunction "SDI_SDI") (pintype "bidirectional"))
      (node (ref "LED27") (pin "SDO") (pinfunction "SDO_SDO") (pintype "bidirectional"))
    )
    (net (code "175") (name "Net-(LED27-PadCKI)") (class "Default")
      (node (ref "LED27") (pin "CKI") (pinfunction "CKI_CKI") (pintype "bidirectional"))
      (node (ref "LED28") (pin "CKO") (pinfunction "CKO_CKO") (pintype "bidirectional"))
    )
    (net (code "176") (name "Net-(LED27-PadSDI)") (class "Default")
      (node (ref "LED27") (pin "SDI") (pinfunction "SDI_SDI") (pintype "bidirectional"))
      (node (ref "LED28") (pin "SDO") (pinfunction "SDO_SDO") (pintype "bidirectional"))
    )
    (net (code "177") (name "Net-(LED28-PadCKI)") (class "Default")
      (node (ref "LED28") (pin "CKI") (pinfunction "CKI_CKI") (pintype "bidirectional"))
      (node (ref "LED29") (pin "CKO") (pinfunction "CKO_CKO") (pintype "bidirectional"))
    )
    (net (code "178") (name "Net-(LED28-PadSDI)") (class "Default")
      (node (ref "LED28") (pin "SDI") (pinfunction "SDI_SDI") (pintype "bidirectional"))
      (node (ref "LED29") (pin "SDO") (pinfunction "SDO_SDO") (pintype "bidirectional"))
    )
    (net (code "179") (name "Net-(LED29-PadCKI)") (class "Default")
      (node (ref "LED29") (pin "CKI") (pinfunction "CKI_CKI") (pintype "bidirectional"))
      (node (ref "LED30") (pin "CKO") (pinfunction "CKO_CKO") (pintype "bidirectional"))
    )
    (net (code "180") (name "Net-(LED29-PadSDI)") (class "Default")
      (node (ref "LED29") (pin "SDI") (pinfunction "SDI_SDI") (pintype "bidirectional"))
      (node (ref "LED30") (pin "SDO") (pinfunction "SDO_SDO") (pintype "bidirectional"))
    )
    (net (code "181") (name "Net-(LED30-PadCKI)") (class "Default")
      (node (ref "LED30") (pin "CKI") (pinfunction "CKI_CKI") (pintype "bidirectional"))
      (node (ref "LED31") (pin "CKO") (pinfunction "CKO_CKO") (pintype "bidirectional"))
    )
    (net (code "182") (name "Net-(LED30-PadSDI)") (class "Default")
      (node (ref "LED30") (pin "SDI") (pinfunction "SDI_SDI") (pintype "bidirectional"))
      (node (ref "LED31") (pin "SDO") (pinfunction "SDO_SDO") (pintype "bidirectional"))
    )
    (net (code "183") (name "Net-(LED31-PadCKI)") (class "Default")
      (node (ref "LED31") (pin "CKI") (pinfunction "CKI_CKI") (pintype "bidirectional"))
      (node (ref "LED32") (pin "CKO") (pinfunction "CKO_CKO") (pintype "bidirectional"))
    )
    (net (code "184") (name "Net-(LED31-PadSDI)") (class "Default")
      (node (ref "LED31") (pin "SDI") (pinfunction "SDI_SDI") (pintype "bidirectional"))
      (node (ref "LED32") (pin "SDO") (pinfunction "SDO_SDO") (pintype "bidirectional"))
    )
    (net (code "185") (name "Net-(LED33-PadCKO)") (class "Default")
      (node (ref "LED33") (pin "CKO") (pinfunction "CKO_CKO") (pintype "bidirectional"))
      (node (ref "LED34") (pin "CKI") (pinfunction "CKI_CKI") (pintype "bidirectional"))
    )
    (net (code "186") (name "Net-(LED33-PadSDO)") (class "Default")
      (node (ref "LED33") (pin "SDO") (pinfunction "SDO_SDO") (pintype "bidirectional"))
      (node (ref "LED34") (pin "SDI") (pinfunction "SDI_SDI") (pintype "bidirectional"))
    )
    (net (code "187") (name "Net-(LED34-PadCKO)") (class "Default")
      (node (ref "LED34") (pin "CKO") (pinfunction "CKO_CKO") (pintype "bidirectional"))
      (node (ref "LED35") (pin "CKI") (pinfunction "CKI_CKI") (pintype "bidirectional"))
    )
    (net (code "188") (name "Net-(LED34-PadSDO)") (class "Default")
      (node (ref "LED34") (pin "SDO") (pinfunction "SDO_SDO") (pintype "bidirectional"))
      (node (ref "LED35") (pin "SDI") (pinfunction "SDI_SDI") (pintype "bidirectional"))
    )
    (net (code "189") (name "Net-(LED35-PadCKO)") (class "Default")
      (node (ref "LED35") (pin "CKO") (pinfunction "CKO_CKO") (pintype "bidirectional"))
      (node (ref "LED36") (pin "CKI") (pinfunction "CKI_CKI") (pintype "bidirectional"))
    )
    (net (code "190") (name "Net-(LED35-PadSDO)") (class "Default")
      (node (ref "LED35") (pin "SDO") (pinfunction "SDO_SDO") (pintype "bidirectional"))
      (node (ref "LED36") (pin "SDI") (pinfunction "SDI_SDI") (pintype "bidirectional"))
    )
    (net (code "191") (name "Net-(LED36-PadCKO)") (class "Default")
      (node (ref "LED36") (pin "CKO") (pinfunction "CKO_CKO") (pintype "bidirectional"))
      (node (ref "LED37") (pin "CKI") (pinfunction "CKI_CKI") (pintype "bidirectional"))
    )
    (net (code "192") (name "Net-(LED36-PadSDO)") (class "Default")
      (node (ref "LED36") (pin "SDO") (pinfunction "SDO_SDO") (pintype "bidirectional"))
      (node (ref "LED37") (pin "SDI") (pinfunction "SDI_SDI") (pintype "bidirectional"))
    )
    (net (code "193") (name "Net-(LED37-PadCKO)") (class "Default")
      (node (ref "LED37") (pin "CKO") (pinfunction "CKO_CKO") (pintype "bidirectional"))
      (node (ref "LED38") (pin "CKI") (pinfunction "CKI_CKI") (pintype "bidirectional"))
    )
    (net (code "194") (name "Net-(LED37-PadSDO)") (class "Default")
      (node (ref "LED37") (pin "SDO") (pinfunction "SDO_SDO") (pintype "bidirectional"))
      (node (ref "LED38") (pin "SDI") (pinfunction "SDI_SDI") (pintype "bidirectional"))
    )
    (net (code "195") (name "Net-(LED38-PadCKO)") (class "Default")
      (node (ref "LED38") (pin "CKO") (pinfunction "CKO_CKO") (pintype "bidirectional"))
      (node (ref "LED39") (pin "CKI") (pinfunction "CKI_CKI") (pintype "bidirectional"))
    )
    (net (code "196") (name "Net-(LED38-PadSDO)") (class "Default")
      (node (ref "LED38") (pin "SDO") (pinfunction "SDO_SDO") (pintype "bidirectional"))
      (node (ref "LED39") (pin "SDI") (pinfunction "SDI_SDI") (pintype "bidirectional"))
    )
    (net (code "197") (name "Net-(LED39-PadCKO)") (class "Default")
      (node (ref "LED39") (pin "CKO") (pinfunction "CKO_CKO") (pintype "bidirectional"))
      (node (ref "LED40") (pin "CKI") (pinfunction "CKI_CKI") (pintype "bidirectional"))
    )
    (net (code "198") (name "Net-(LED39-PadSDO)") (class "Default")
      (node (ref "LED39") (pin "SDO") (pinfunction "SDO_SDO") (pintype "bidirectional"))
      (node (ref "LED40") (pin "SDI") (pinfunction "SDI_SDI") (pintype "bidirectional"))
    )
    (net (code "199") (name "Net-(LED40-PadCKO)") (class "Default")
      (node (ref "LED40") (pin "CKO") (pinfunction "CKO_CKO") (pintype "bidirectional"))
      (node (ref "LED48") (pin "CKI") (pinfunction "CKI_CKI") (pintype "bidirectional"))
    )
    (net (code "200") (name "Net-(LED40-PadSDO)") (class "Default")
      (node (ref "LED40") (pin "SDO") (pinfunction "SDO_SDO") (pintype "bidirectional"))
      (node (ref "LED48") (pin "SDI") (pinfunction "SDI_SDI") (pintype "bidirectional"))
    )
    (net (code "201") (name "Net-(LED41-PadCKI)") (class "Default")
      (node (ref "LED41") (pin "CKI") (pinfunction "CKI_CKI") (pintype "bidirectional"))
      (node (ref "LED42") (pin "CKO") (pinfunction "CKO_CKO") (pintype "bidirectional"))
    )
    (net (code "202") (name "Net-(LED41-PadCKO)") (class "Default")
      (node (ref "LED41") (pin "CKO") (pinfunction "CKO_CKO") (pintype "bidirectional"))
      (node (ref "LED49") (pin "CKI") (pinfunction "CKI_CKI") (pintype "bidirectional"))
    )
    (net (code "203") (name "Net-(LED41-PadSDI)") (class "Default")
      (node (ref "LED41") (pin "SDI") (pinfunction "SDI_SDI") (pintype "bidirectional"))
      (node (ref "LED42") (pin "SDO") (pinfunction "SDO_SDO") (pintype "bidirectional"))
    )
    (net (code "204") (name "Net-(LED41-PadSDO)") (class "Default")
      (node (ref "LED41") (pin "SDO") (pinfunction "SDO_SDO") (pintype "bidirectional"))
      (node (ref "LED49") (pin "SDI") (pinfunction "SDI_SDI") (pintype "bidirectional"))
    )
    (net (code "205") (name "Net-(LED42-PadCKI)") (class "Default")
      (node (ref "LED42") (pin "CKI") (pinfunction "CKI_CKI") (pintype "bidirectional"))
      (node (ref "LED43") (pin "CKO") (pinfunction "CKO_CKO") (pintype "bidirectional"))
    )
    (net (code "206") (name "Net-(LED42-PadSDI)") (class "Default")
      (node (ref "LED42") (pin "SDI") (pinfunction "SDI_SDI") (pintype "bidirectional"))
      (node (ref "LED43") (pin "SDO") (pinfunction "SDO_SDO") (pintype "bidirectional"))
    )
    (net (code "207") (name "Net-(LED43-PadCKI)") (class "Default")
      (node (ref "LED43") (pin "CKI") (pinfunction "CKI_CKI") (pintype "bidirectional"))
      (node (ref "LED44") (pin "CKO") (pinfunction "CKO_CKO") (pintype "bidirectional"))
    )
    (net (code "208") (name "Net-(LED43-PadSDI)") (class "Default")
      (node (ref "LED43") (pin "SDI") (pinfunction "SDI_SDI") (pintype "bidirectional"))
      (node (ref "LED44") (pin "SDO") (pinfunction "SDO_SDO") (pintype "bidirectional"))
    )
    (net (code "209") (name "Net-(LED44-PadCKI)") (class "Default")
      (node (ref "LED44") (pin "CKI") (pinfunction "CKI_CKI") (pintype "bidirectional"))
      (node (ref "LED45") (pin "CKO") (pinfunction "CKO_CKO") (pintype "bidirectional"))
    )
    (net (code "210") (name "Net-(LED44-PadSDI)") (class "Default")
      (node (ref "LED44") (pin "SDI") (pinfunction "SDI_SDI") (pintype "bidirectional"))
      (node (ref "LED45") (pin "SDO") (pinfunction "SDO_SDO") (pintype "bidirectional"))
    )
    (net (code "211") (name "Net-(LED45-PadCKI)") (class "Default")
      (node (ref "LED45") (pin "CKI") (pinfunction "CKI_CKI") (pintype "bidirectional"))
      (node (ref "LED46") (pin "CKO") (pinfunction "CKO_CKO") (pintype "bidirectional"))
    )
    (net (code "212") (name "Net-(LED45-PadSDI)") (class "Default")
      (node (ref "LED45") (pin "SDI") (pinfunction "SDI_SDI") (pintype "bidirectional"))
      (node (ref "LED46") (pin "SDO") (pinfunction "SDO_SDO") (pintype "bidirectional"))
    )
    (net (code "213") (name "Net-(LED46-PadCKI)") (class "Default")
      (node (ref "LED46") (pin "CKI") (pinfunction "CKI_CKI") (pintype "bidirectional"))
      (node (ref "LED47") (pin "CKO") (pinfunction "CKO_CKO") (pintype "bidirectional"))
    )
    (net (code "214") (name "Net-(LED46-PadSDI)") (class "Default")
      (node (ref "LED46") (pin "SDI") (pinfunction "SDI_SDI") (pintype "bidirectional"))
      (node (ref "LED47") (pin "SDO") (pinfunction "SDO_SDO") (pintype "bidirectional"))
    )
    (net (code "215") (name "Net-(LED47-PadCKI)") (class "Default")
      (node (ref "LED47") (pin "CKI") (pinfunction "CKI_CKI") (pintype "bidirectional"))
      (node (ref "LED48") (pin "CKO") (pinfunction "CKO_CKO") (pintype "bidirectional"))
    )
    (net (code "216") (name "Net-(LED47-PadSDI)") (class "Default")
      (node (ref "LED47") (pin "SDI") (pinfunction "SDI_SDI") (pintype "bidirectional"))
      (node (ref "LED48") (pin "SDO") (pinfunction "SDO_SDO") (pintype "bidirectional"))
    )
    (net (code "217") (name "Net-(LED49-PadCKO)") (class "Default")
      (node (ref "LED49") (pin "CKO") (pinfunction "CKO_CKO") (pintype "bidirectional"))
      (node (ref "LED50") (pin "CKI") (pinfunction "CKI_CKI") (pintype "bidirectional"))
    )
    (net (code "218") (name "Net-(LED49-PadSDO)") (class "Default")
      (node (ref "LED49") (pin "SDO") (pinfunction "SDO_SDO") (pintype "bidirectional"))
      (node (ref "LED50") (pin "SDI") (pinfunction "SDI_SDI") (pintype "bidirectional"))
    )
    (net (code "219") (name "Net-(LED50-PadCKO)") (class "Default")
      (node (ref "LED50") (pin "CKO") (pinfunction "CKO_CKO") (pintype "bidirectional"))
      (node (ref "LED51") (pin "CKI") (pinfunction "CKI_CKI") (pintype "bidirectional"))
    )
    (net (code "220") (name "Net-(LED50-PadSDO)") (class "Default")
      (node (ref "LED50") (pin "SDO") (pinfunction "SDO_SDO") (pintype "bidirectional"))
      (node (ref "LED51") (pin "SDI") (pinfunction "SDI_SDI") (pintype "bidirectional"))
    )
    (net (code "221") (name "Net-(LED51-PadCKO)") (class "Default")
      (node (ref "LED51") (pin "CKO") (pinfunction "CKO_CKO") (pintype "bidirectional"))
      (node (ref "LED52") (pin "CKI") (pinfunction "CKI_CKI") (pintype "bidirectional"))
    )
    (net (code "222") (name "Net-(LED51-PadSDO)") (class "Default")
      (node (ref "LED51") (pin "SDO") (pinfunction "SDO_SDO") (pintype "bidirectional"))
      (node (ref "LED52") (pin "SDI") (pinfunction "SDI_SDI") (pintype "bidirectional"))
    )
    (net (code "223") (name "Net-(LED52-PadCKO)") (class "Default")
      (node (ref "LED52") (pin "CKO") (pinfunction "CKO_CKO") (pintype "bidirectional"))
      (node (ref "LED53") (pin "CKI") (pinfunction "CKI_CKI") (pintype "bidirectional"))
    )
    (net (code "224") (name "Net-(LED52-PadSDO)") (class "Default")
      (node (ref "LED52") (pin "SDO") (pinfunction "SDO_SDO") (pintype "bidirectional"))
      (node (ref "LED53") (pin "SDI") (pinfunction "SDI_SDI") (pintype "bidirectional"))
    )
    (net (code "225") (name "Net-(LED53-PadCKO)") (class "Default")
      (node (ref "LED53") (pin "CKO") (pinfunction "CKO_CKO") (pintype "bidirectional"))
      (node (ref "LED54") (pin "CKI") (pinfunction "CKI_CKI") (pintype "bidirectional"))
    )
    (net (code "226") (name "Net-(LED53-PadSDO)") (class "Default")
      (node (ref "LED53") (pin "SDO") (pinfunction "SDO_SDO") (pintype "bidirectional"))
      (node (ref "LED54") (pin "SDI") (pinfunction "SDI_SDI") (pintype "bidirectional"))
    )
    (net (code "227") (name "Net-(LED54-PadCKO)") (class "Default")
      (node (ref "LED54") (pin "CKO") (pinfunction "CKO_CKO") (pintype "bidirectional"))
      (node (ref "LED55") (pin "CKI") (pinfunction "CKI_CKI") (pintype "bidirectional"))
    )
    (net (code "228") (name "Net-(LED54-PadSDO)") (class "Default")
      (node (ref "LED54") (pin "SDO") (pinfunction "SDO_SDO") (pintype "bidirectional"))
      (node (ref "LED55") (pin "SDI") (pinfunction "SDI_SDI") (pintype "bidirectional"))
    )
    (net (code "229") (name "Net-(LED55-PadCKO)") (class "Default")
      (node (ref "LED55") (pin "CKO") (pinfunction "CKO_CKO") (pintype "bidirectional"))
      (node (ref "LED56") (pin "CKI") (pinfunction "CKI_CKI") (pintype "bidirectional"))
    )
    (net (code "230") (name "Net-(LED55-PadSDO)") (class "Default")
      (node (ref "LED55") (pin "SDO") (pinfunction "SDO_SDO") (pintype "bidirectional"))
      (node (ref "LED56") (pin "SDI") (pinfunction "SDI_SDI") (pintype "bidirectional"))
    )
    (net (code "231") (name "Net-(LED56-PadCKO)") (class "Default")
      (node (ref "LED56") (pin "CKO") (pinfunction "CKO_CKO") (pintype "bidirectional"))
      (node (ref "LED64") (pin "CKI") (pinfunction "CKI_CKI") (pintype "bidirectional"))
    )
    (net (code "232") (name "Net-(LED56-PadSDO)") (class "Default")
      (node (ref "LED56") (pin "SDO") (pinfunction "SDO_SDO") (pintype "bidirectional"))
      (node (ref "LED64") (pin "SDI") (pinfunction "SDI_SDI") (pintype "bidirectional"))
    )
    (net (code "233") (name "Net-(LED57-PadCKI)") (class "Default")
      (node (ref "LED57") (pin "CKI") (pinfunction "CKI_CKI") (pintype "bidirectional"))
      (node (ref "LED58") (pin "CKO") (pinfunction "CKO_CKO") (pintype "bidirectional"))
    )
    (net (code "234") (name "Net-(LED57-PadCKO)") (class "Default")
      (node (ref "LED57") (pin "CKO") (pinfunction "CKO_CKO") (pintype "bidirectional"))
      (node (ref "ROUT0") (pin "2") (pinfunction "2_2") (pintype "passive"))
    )
    (net (code "235") (name "Net-(LED57-PadSDI)") (class "Default")
      (node (ref "LED57") (pin "SDI") (pinfunction "SDI_SDI") (pintype "bidirectional"))
      (node (ref "LED58") (pin "SDO") (pinfunction "SDO_SDO") (pintype "bidirectional"))
    )
    (net (code "236") (name "Net-(LED57-PadSDO)") (class "Default")
      (node (ref "LED57") (pin "SDO") (pinfunction "SDO_SDO") (pintype "bidirectional"))
      (node (ref "ROUT1") (pin "2") (pinfunction "2_2") (pintype "passive"))
    )
    (net (code "237") (name "Net-(LED58-PadCKI)") (class "Default")
      (node (ref "LED58") (pin "CKI") (pinfunction "CKI_CKI") (pintype "bidirectional"))
      (node (ref "LED59") (pin "CKO") (pinfunction "CKO_CKO") (pintype "bidirectional"))
    )
    (net (code "238") (name "Net-(LED58-PadSDI)") (class "Default")
      (node (ref "LED58") (pin "SDI") (pinfunction "SDI_SDI") (pintype "bidirectional"))
      (node (ref "LED59") (pin "SDO") (pinfunction "SDO_SDO") (pintype "bidirectional"))
    )
    (net (code "239") (name "Net-(LED59-PadCKI)") (class "Default")
      (node (ref "LED59") (pin "CKI") (pinfunction "CKI_CKI") (pintype "bidirectional"))
      (node (ref "LED60") (pin "CKO") (pinfunction "CKO_CKO") (pintype "bidirectional"))
    )
    (net (code "240") (name "Net-(LED59-PadSDI)") (class "Default")
      (node (ref "LED59") (pin "SDI") (pinfunction "SDI_SDI") (pintype "bidirectional"))
      (node (ref "LED60") (pin "SDO") (pinfunction "SDO_SDO") (pintype "bidirectional"))
    )
    (net (code "241") (name "Net-(LED60-PadCKI)") (class "Default")
      (node (ref "LED60") (pin "CKI") (pinfunction "CKI_CKI") (pintype "bidirectional"))
      (node (ref "LED61") (pin "CKO") (pinfunction "CKO_CKO") (pintype "bidirectional"))
    )
    (net (code "242") (name "Net-(LED60-PadSDI)") (class "Default")
      (node (ref "LED60") (pin "SDI") (pinfunction "SDI_SDI") (pintype "bidirectional"))
      (node (ref "LED61") (pin "SDO") (pinfunction "SDO_SDO") (pintype "bidirectional"))
    )
    (net (code "243") (name "Net-(LED61-PadCKI)") (class "Default")
      (node (ref "LED61") (pin "CKI") (pinfunction "CKI_CKI") (pintype "bidirectional"))
      (node (ref "LED62") (pin "CKO") (pinfunction "CKO_CKO") (pintype "bidirectional"))
    )
    (net (code "244") (name "Net-(LED61-PadSDI)") (class "Default")
      (node (ref "LED61") (pin "SDI") (pinfunction "SDI_SDI") (pintype "bidirectional"))
      (node (ref "LED62") (pin "SDO") (pinfunction "SDO_SDO") (pintype "bidirectional"))
    )
    (net (code "245") (name "Net-(LED62-PadCKI)") (class "Default")
      (node (ref "LED62") (pin "CKI") (pinfunction "CKI_CKI") (pintype "bidirectional"))
      (node (ref "LED63") (pin "CKO") (pinfunction "CKO_CKO") (pintype "bidirectional"))
    )
    (net (code "246") (name "Net-(LED62-PadSDI)") (class "Default")
      (node (ref "LED62") (pin "SDI") (pinfunction "SDI_SDI") (pintype "bidirectional"))
      (node (ref "LED63") (pin "SDO") (pinfunction "SDO_SDO") (pintype "bidirectional"))
    )
    (net (code "247") (name "Net-(LED63-PadCKI)") (class "Default")
      (node (ref "LED63") (pin "CKI") (pinfunction "CKI_CKI") (pintype "bidirectional"))
      (node (ref "LED64") (pin "CKO") (pinfunction "CKO_CKO") (pintype "bidirectional"))
    )
    (net (code "248") (name "Net-(LED63-PadSDI)") (class "Default")
      (node (ref "LED63") (pin "SDI") (pinfunction "SDI_SDI") (pintype "bidirectional"))
      (node (ref "LED64") (pin "SDO") (pinfunction "SDO_SDO") (pintype "bidirectional"))
    )
    (net (code "249") (name "Net-(MOSN0-G)") (class "Default")
      (node (ref "MOSN0") (pin "1") (pinfunction "G_1") (pintype "bidirectional"))
      (node (ref "Rcg0") (pin "1") (pinfunction "1_1") (pintype "passive"))
      (node (ref "Rci0") (pin "2") (pinfunction "2_2") (pintype "passive"))
    )
    (net (code "250") (name "Net-(MOSN1-G)") (class "Default")
      (node (ref "MOSN1") (pin "1") (pinfunction "G_1") (pintype "bidirectional"))
      (node (ref "Rcg1") (pin "1") (pinfunction "1_1") (pintype "passive"))
      (node (ref "Rci1") (pin "2") (pinfunction "2_2") (pintype "passive"))
    )
    (net (code "251") (name "Net-(MOSN2-G)") (class "Default")
      (node (ref "MOSN2") (pin "1") (pinfunction "G_1") (pintype "bidirectional"))
      (node (ref "Rcg2") (pin "1") (pinfunction "1_1") (pintype "passive"))
      (node (ref "Rci2") (pin "2") (pinfunction "2_2") (pintype "passive"))
    )
    (net (code "252") (name "Net-(MOSN3-G)") (class "Default")
      (node (ref "MOSN3") (pin "1") (pinfunction "G_1") (pintype "bidirectional"))
      (node (ref "Rcg3") (pin "1") (pinfunction "1_1") (pintype "passive"))
      (node (ref "Rci3") (pin "2") (pinfunction "2_2") (pintype "passive"))
    )
    (net (code "253") (name "Net-(MOSN4-G)") (class "Default")
      (node (ref "MOSN4") (pin "1") (pinfunction "G_1") (pintype "bidirectional"))
      (node (ref "Rcg4") (pin "1") (pinfunction "1_1") (pintype "passive"))
      (node (ref "Rci4") (pin "2") (pinfunction "2_2") (pintype "passive"))
    )
    (net (code "254") (name "Net-(MOSN5-G)") (class "Default")
      (node (ref "MOSN5") (pin "1") (pinfunction "G_1") (pintype "bidirectional"))
      (node (ref "Rcg5") (pin "1") (pinfunction "1_1") (pintype "passive"))
      (node (ref "Rci5") (pin "2") (pinfunction "2_2") (pintype "passive"))
    )
    (net (code "255") (name "Net-(MOSN6-G)") (class "Default")
      (node (ref "MOSN6") (pin "1") (pinfunction "G_1") (pintype "bidirectional"))
      (node (ref "Rcg6") (pin "1") (pinfunction "1_1") (pintype "passive"))
      (node (ref "Rci6") (pin "2") (pinfunction "2_2") (pintype "passive"))
    )
    (net (code "256") (name "Net-(MOSN7-G)") (class "Default")
      (node (ref "MOSN7") (pin "1") (pinfunction "G_1") (pintype "bidirectional"))
      (node (ref "Rcg7") (pin "1") (pinfunction "1_1") (pintype "passive"))
      (node (ref "Rci7") (pin "2") (pinfunction "2_2") (pintype "passive"))
    )
    (net (code "257") (name "Net-(MOSP0-G)") (class "Default")
      (node (ref "MOSP0") (pin "1") (pinfunction "G_1") (pintype "bidirectional"))
      (node (ref "Rin0") (pin "1") (pinfunction "1_1") (pintype "passive"))
      (node (ref "Rvs0") (pin "2") (pinfunction "2_2") (pintype "passive"))
    )
    (net (code "258") (name "Net-(MOSP1-G)") (class "Default")
      (node (ref "MOSP1") (pin "1") (pinfunction "G_1") (pintype "bidirectional"))
      (node (ref "Rin1") (pin "1") (pinfunction "1_1") (pintype "passive"))
      (node (ref "Rvs1") (pin "2") (pinfunction "2_2") (pintype "passive"))
    )
    (net (code "259") (name "Net-(MOSP2-G)") (class "Default")
      (node (ref "MOSP2") (pin "1") (pinfunction "G_1") (pintype "bidirectional"))
      (node (ref "Rin2") (pin "1") (pinfunction "1_1") (pintype "passive"))
      (node (ref "Rvs2") (pin "2") (pinfunction "2_2") (pintype "passive"))
    )
    (net (code "260") (name "Net-(MOSP3-G)") (class "Default")
      (node (ref "MOSP3") (pin "1") (pinfunction "G_1") (pintype "bidirectional"))
      (node (ref "Rin3") (pin "1") (pinfunction "1_1") (pintype "passive"))
      (node (ref "Rvs3") (pin "2") (pinfunction "2_2") (pintype "passive"))
    )
    (net (code "261") (name "Net-(MOSP4-G)") (class "Default")
      (node (ref "MOSP4") (pin "1") (pinfunction "G_1") (pintype "bidirectional"))
      (node (ref "Rin4") (pin "1") (pinfunction "1_1") (pintype "passive"))
      (node (ref "Rvs4") (pin "2") (pinfunction "2_2") (pintype "passive"))
    )
    (net (code "262") (name "Net-(MOSP5-G)") (class "Default")
      (node (ref "MOSP5") (pin "1") (pinfunction "G_1") (pintype "bidirectional"))
      (node (ref "Rin5") (pin "1") (pinfunction "1_1") (pintype "passive"))
      (node (ref "Rvs5") (pin "2") (pinfunction "2_2") (pintype "passive"))
    )
    (net (code "263") (name "Net-(MOSP6-G)") (class "Default")
      (node (ref "MOSP6") (pin "1") (pinfunction "G_1") (pintype "bidirectional"))
      (node (ref "Rin6") (pin "1") (pinfunction "1_1") (pintype "passive"))
      (node (ref "Rvs6") (pin "2") (pinfunction "2_2") (pintype "passive"))
    )
    (net (code "264") (name "Net-(MOSP7-G)") (class "Default")
      (node (ref "MOSP7") (pin "1") (pinfunction "G_1") (pintype "bidirectional"))
      (node (ref "Rin7") (pin "1") (pinfunction "1_1") (pintype "passive"))
      (node (ref "Rvs7") (pin "2") (pinfunction "2_2") (pintype "passive"))
    )
    (net (code "265") (name "VCC") (class "Default")
      (node (ref "319_0") (pin "2") (pinfunction "2_2") (pintype "passive"))
      (node (ref "319_2") (pin "2") (pinfunction "2_2") (pintype "passive"))
      (node (ref "810_0") (pin "1") (pinfunction "1_1") (pintype "passive"))
      (node (ref "810_2") (pin "1") (pinfunction "1_1") (pintype "passive"))
      (node (ref "H1") (pin "1") (pinfunction "3.3_1") (pintype "passive"))
      (node (ref "H2") (pin "38") (pinfunction "38_38") (pintype "passive"))
      (node (ref "H_3_1") (pin "1") (pinfunction "1_1") (pintype "passive"))
      (node (ref "LED1") (pin "VCC") (pinfunction "VCC_VCC") (pintype "bidirectional"))
      (node (ref "LED10") (pin "VCC") (pinfunction "VCC_VCC") (pintype "bidirectional"))
      (node (ref "LED11") (pin "VCC") (pinfunction "VCC_VCC") (pintype "bidirectional"))
      (node (ref "LED12") (pin "VCC") (pinfunction "VCC_VCC") (pintype "bidirectional"))
      (node (ref "LED13") (pin "VCC") (pinfunction "VCC_VCC") (pintype "bidirectional"))
      (node (ref "LED14") (pin "VCC") (pinfunction "VCC_VCC") (pintype "bidirectional"))
      (node (ref "LED15") (pin "VCC") (pinfunction "VCC_VCC") (pintype "bidirectional"))
      (node (ref "LED16") (pin "VCC") (pinfunction "VCC_VCC") (pintype "bidirectional"))
      (node (ref "LED17") (pin "VCC") (pinfunction "VCC_VCC") (pintype "bidirectional"))
      (node (ref "LED18") (pin "VCC") (pinfunction "VCC_VCC") (pintype "bidirectional"))
      (node (ref "LED19") (pin "VCC") (pinfunction "VCC_VCC") (pintype "bidirectional"))
      (node (ref "LED2") (pin "VCC") (pinfunction "VCC_VCC") (pintype "bidirectional"))
      (node (ref "LED20") (pin "VCC") (pinfunction "VCC_VCC") (pintype "bidirectional"))
      (node (ref "LED21") (pin "VCC") (pinfunction "VCC_VCC") (pintype "bidirectional"))
      (node (ref "LED22") (pin "VCC") (pinfunction "VCC_VCC") (pintype "bidirectional"))
      (node (ref "LED23") (pin "VCC") (pinfunction "VCC_VCC") (pintype "bidirectional"))
      (node (ref "LED24") (pin "VCC") (pinfunction "VCC_VCC") (pintype "bidirectional"))
      (node (ref "LED25") (pin "VCC") (pinfunction "VCC_VCC") (pintype "bidirectional"))
      (node (ref "LED26") (pin "VCC") (pinfunction "VCC_VCC") (pintype "bidirectional"))
      (node (ref "LED27") (pin "VCC") (pinfunction "VCC_VCC") (pintype "bidirectional"))
      (node (ref "LED28") (pin "VCC") (pinfunction "VCC_VCC") (pintype "bidirectional"))
      (node (ref "LED29") (pin "VCC") (pinfunction "VCC_VCC") (pintype "bidirectional"))
      (node (ref "LED3") (pin "VCC") (pinfunction "VCC_VCC") (pintype "bidirectional"))
      (node (ref "LED30") (pin "VCC") (pinfunction "VCC_VCC") (pintype "bidirectional"))
      (node (ref "LED31") (pin "VCC") (pinfunction "VCC_VCC") (pintype "bidirectional"))
      (node (ref "LED32") (pin "VCC") (pinfunction "VCC_VCC") (pintype "bidirectional"))
      (node (ref "LED33") (pin "VCC") (pinfunction "VCC_VCC") (pintype "bidirectional"))
      (node (ref "LED34") (pin "VCC") (pinfunction "VCC_VCC") (pintype "bidirectional"))
      (node (ref "LED35") (pin "VCC") (pinfunction "VCC_VCC") (pintype "bidirectional"))
      (node (ref "LED36") (pin "VCC") (pinfunction "VCC_VCC") (pintype "bidirectional"))
      (node (ref "LED37") (pin "VCC") (pinfunction "VCC_VCC") (pintype "bidirectional"))
      (node (ref "LED38") (pin "VCC") (pinfunction "VCC_VCC") (pintype "bidirectional"))
      (node (ref "LED39") (pin "VCC") (pinfunction "VCC_VCC") (pintype "bidirectional"))
      (node (ref "LED4") (pin "VCC") (pinfunction "VCC_VCC") (pintype "bidirectional"))
      (node (ref "LED40") (pin "VCC") (pinfunction "VCC_VCC") (pintype "bidirectional"))
      (node (ref "LED41") (pin "VCC") (pinfunction "VCC_VCC") (pintype "bidirectional"))
      (node (ref "LED42") (pin "VCC") (pinfunction "VCC_VCC") (pintype "bidirectional"))
      (node (ref "LED43") (pin "VCC") (pinfunction "VCC_VCC") (pintype "bidirectional"))
      (node (ref "LED44") (pin "VCC") (pinfunction "VCC_VCC") (pintype "bidirectional"))
      (node (ref "LED45") (pin "VCC") (pinfunction "VCC_VCC") (pintype "bidirectional"))
      (node (ref "LED46") (pin "VCC") (pinfunction "VCC_VCC") (pintype "bidirectional"))
      (node (ref "LED47") (pin "VCC") (pinfunction "VCC_VCC") (pintype "bidirectional"))
      (node (ref "LED48") (pin "VCC") (pinfunction "VCC_VCC") (pintype "bidirectional"))
      (node (ref "LED49") (pin "VCC") (pinfunction "VCC_VCC") (pintype "bidirectional"))
      (node (ref "LED5") (pin "VCC") (pinfunction "VCC_VCC") (pintype "bidirectional"))
      (node (ref "LED50") (pin "VCC") (pinfunction "VCC_VCC") (pintype "bidirectional"))
      (node (ref "LED51") (pin "VCC") (pinfunction "VCC_VCC") (pintype "bidirectional"))
      (node (ref "LED52") (pin "VCC") (pinfunction "VCC_VCC") (pintype "bidirectional"))
      (node (ref "LED53") (pin "VCC") (pinfunction "VCC_VCC") (pintype "bidirectional"))
      (node (ref "LED54") (pin "VCC") (pinfunction "VCC_VCC") (pintype "bidirectional"))
      (node (ref "LED55") (pin "VCC") (pinfunction "VCC_VCC") (pintype "bidirectional"))
      (node (ref "LED56") (pin "VCC") (pinfunction "VCC_VCC") (pintype "bidirectional"))
      (node (ref "LED57") (pin "VCC") (pinfunction "VCC_VCC") (pintype "bidirectional"))
      (node (ref "LED58") (pin "VCC") (pinfunction "VCC_VCC") (pintype "bidirectional"))
      (node (ref "LED59") (pin "VCC") (pinfunction "VCC_VCC") (pintype "bidirectional"))
      (node (ref "LED6") (pin "VCC") (pinfunction "VCC_VCC") (pintype "bidirectional"))
      (node (ref "LED60") (pin "VCC") (pinfunction "VCC_VCC") (pintype "bidirectional"))
      (node (ref "LED61") (pin "VCC") (pinfunction "VCC_VCC") (pintype "bidirectional"))
      (node (ref "LED62") (pin "VCC") (pinfunction "VCC_VCC") (pintype "bidirectional"))
      (node (ref "LED63") (pin "VCC") (pinfunction "VCC_VCC") (pintype "bidirectional"))
      (node (ref "LED64") (pin "VCC") (pinfunction "VCC_VCC") (pintype "bidirectional"))
      (node (ref "LED7") (pin "VCC") (pinfunction "VCC_VCC") (pintype "bidirectional"))
      (node (ref "LED8") (pin "VCC") (pinfunction "VCC_VCC") (pintype "bidirectional"))
      (node (ref "LED9") (pin "VCC") (pinfunction "VCC_VCC") (pintype "bidirectional"))
      (node (ref "MOSP0") (pin "2") (pinfunction "S_2") (pintype "bidirectional"))
      (node (ref "MOSP1") (pin "2") (pinfunction "S_2") (pintype "bidirectional"))
      (node (ref "MOSP2") (pin "2") (pinfunction "S_2") (pintype "bidirectional"))
      (node (ref "MOSP3") (pin "2") (pinfunction "S_2") (pintype "bidirectional"))
      (node (ref "MOSP4") (pin "2") (pinfunction "S_2") (pintype "bidirectional"))
      (node (ref "MOSP5") (pin "2") (pinfunction "S_2") (pintype "bidirectional"))
      (node (ref "MOSP6") (pin "2") (pinfunction "S_2") (pintype "bidirectional"))
      (node (ref "MOSP7") (pin "2") (pinfunction "S_2") (pintype "bidirectional"))
      (node (ref "M_C") (pin "16") (pinfunction "VCC_16") (pintype "bidirectional"))
      (node (ref "M_C") (pin "6") (pinfunction "~E_6") (pintype "bidirectional"))
      (node (ref "M_R") (pin "16") (pinfunction "VCC_16") (pintype "bidirectional"))
      (node (ref "M_R") (pin "6") (pinfunction "~E_6") (pintype "bidirectional"))
      (node (ref "R200") (pin "1") (pinfunction "1_1") (pintype "passive"))
      (node (ref "R201") (pin "1") (pinfunction "1_1") (pintype "passive"))
      (node (ref "Rvs0") (pin "1") (pinfunction "1_1") (pintype "passive"))
      (node (ref "Rvs1") (pin "1") (pinfunction "1_1") (pintype "passive"))
      (node (ref "Rvs2") (pin "1") (pinfunction "1_1") (pintype "passive"))
      (node (ref "Rvs3") (pin "1") (pinfunction "1_1") (pintype "passive"))
      (node (ref "Rvs4") (pin "1") (pinfunction "1_1") (pintype "passive"))
      (node (ref "Rvs5") (pin "1") (pinfunction "1_1") (pintype "passive"))
      (node (ref "Rvs6") (pin "1") (pinfunction "1_1") (pintype "passive"))
      (node (ref "Rvs7") (pin "1") (pinfunction "1_1") (pintype "passive"))
    )
    (net (code "266") (name "unconnected-(H1-5V-Pad3)") (class "Default")
      (node (ref "H1") (pin "3") (pinfunction "5V_3") (pintype "passive"))
    )
    (net (code "267") (name "unconnected-(H1-A10-Pad14)") (class "Default")
      (node (ref "H1") (pin "14") (pinfunction "A10_14") (pintype "passive"))
    )
    (net (code "268") (name "unconnected-(H1-B4-Pad9)") (class "Default")
      (node (ref "H1") (pin "9") (pinfunction "B4_9") (pintype "passive"))
    )
    (net (code "269") (name "unconnected-(H1-B5-Pad8)") (class "Default")
      (node (ref "H1") (pin "8") (pinfunction "B5_8") (pintype "passive"))
    )
    (net (code "270") (name "unconnected-(H1-B8-Pad5)") (class "Default")
      (node (ref "H1") (pin "5") (pinfunction "B8_5") (pintype "passive"))
    )
    (net (code "271") (name "unconnected-(H1-B9-Pad4)") (class "Default")
      (node (ref "H1") (pin "4") (pinfunction "B9_4") (pintype "passive"))
    )
    (net (code "272") (name "unconnected-(H1-Pad21)") (class "Default")
      (node (ref "H1") (pin "21") (pinfunction "21_21") (pintype "passive"))
    )
    (net (code "273") (name "unconnected-(H1-Pad22)") (class "Default")
      (node (ref "H1") (pin "22") (pinfunction "22_22") (pintype "passive"))
    )
    (net (code "274") (name "unconnected-(H1-Pad23)") (class "Default")
      (node (ref "H1") (pin "23") (pinfunction "23_23") (pintype "passive"))
    )
    (net (code "275") (name "unconnected-(H1-Pad24)") (class "Default")
      (node (ref "H1") (pin "24") (pinfunction "24_24") (pintype "passive"))
    )
    (net (code "276") (name "unconnected-(H1-Pad25)") (class "Default")
      (node (ref "H1") (pin "25") (pinfunction "25_25") (pintype "passive"))
    )
    (net (code "277") (name "unconnected-(H1-Pad26)") (class "Default")
      (node (ref "H1") (pin "26") (pinfunction "26_26") (pintype "passive"))
    )
    (net (code "278") (name "unconnected-(H1-Pad27)") (class "Default")
      (node (ref "H1") (pin "27") (pinfunction "27_27") (pintype "passive"))
    )
    (net (code "279") (name "unconnected-(H1-Pad28)") (class "Default")
      (node (ref "H1") (pin "28") (pinfunction "28_28") (pintype "passive"))
    )
    (net (code "280") (name "unconnected-(H1-Pad29)") (class "Default")
      (node (ref "H1") (pin "29") (pinfunction "29_29") (pintype "passive"))
    )
    (net (code "281") (name "unconnected-(H1-Pad30)") (class "Default")
      (node (ref "H1") (pin "30") (pinfunction "30_30") (pintype "passive"))
    )
    (net (code "282") (name "unconnected-(H1-Pad31)") (class "Default")
      (node (ref "H1") (pin "31") (pinfunction "31_31") (pintype "passive"))
    )
    (net (code "283") (name "unconnected-(H1-Pad32)") (class "Default")
      (node (ref "H1") (pin "32") (pinfunction "32_32") (pintype "passive"))
    )
    (net (code "284") (name "unconnected-(H1-Pad33)") (class "Default")
      (node (ref "H1") (pin "33") (pinfunction "33_33") (pintype "passive"))
    )
    (net (code "285") (name "unconnected-(H1-Pad34)") (class "Default")
      (node (ref "H1") (pin "34") (pinfunction "34_34") (pintype "passive"))
    )
    (net (code "286") (name "unconnected-(H1-Pad35)") (class "Default")
      (node (ref "H1") (pin "35") (pinfunction "35_35") (pintype "passive"))
    )
    (net (code "287") (name "unconnected-(H1-Pad36)") (class "Default")
      (node (ref "H1") (pin "36") (pinfunction "36_36") (pintype "passive"))
    )
    (net (code "288") (name "unconnected-(H1-Pad37)") (class "Default")
      (node (ref "H1") (pin "37") (pinfunction "37_37") (pintype "passive"))
    )
    (net (code "289") (name "unconnected-(H1-Pad38)") (class "Default")
      (node (ref "H1") (pin "38") (pinfunction "38_38") (pintype "passive"))
    )
    (net (code "290") (name "unconnected-(H1-Pad39)") (class "Default")
      (node (ref "H1") (pin "39") (pinfunction "39_39") (pintype "passive"))
    )
    (net (code "291") (name "unconnected-(H1-Pad40)") (class "Default")
      (node (ref "H1") (pin "40") (pinfunction "40_40") (pintype "passive"))
    )
    (net (code "292") (name "unconnected-(H2-3.3-Pad1)") (class "Default")
      (node (ref "H2") (pin "1") (pinfunction "3.3_1") (pintype "passive"))
    )
    (net (code "293") (name "unconnected-(H2-5V-Pad3)") (class "Default")
      (node (ref "H2") (pin "3") (pinfunction "5V_3") (pintype "passive"))
    )
    (net (code "294") (name "unconnected-(H2-A8-Pad16)") (class "Default")
      (node (ref "H2") (pin "16") (pinfunction "A8_16") (pintype "passive"))
    )
    (net (code "295") (name "unconnected-(H2-A9-Pad15)") (class "Default")
      (node (ref "H2") (pin "15") (pinfunction "A9_15") (pintype "passive"))
    )
    (net (code "296") (name "unconnected-(H2-A10-Pad14)") (class "Default")
      (node (ref "H2") (pin "14") (pinfunction "A10_14") (pintype "passive"))
    )
    (net (code "297") (name "unconnected-(H2-A11-Pad13)") (class "Default")
      (node (ref "H2") (pin "13") (pinfunction "A11_13") (pintype "passive"))
    )
    (net (code "298") (name "unconnected-(H2-A12-Pad12)") (class "Default")
      (node (ref "H2") (pin "12") (pinfunction "A12_12") (pintype "passive"))
    )
    (net (code "299") (name "unconnected-(H2-A15-Pad11)") (class "Default")
      (node (ref "H2") (pin "11") (pinfunction "A15_11") (pintype "passive"))
    )
    (net (code "300") (name "unconnected-(H2-B3-Pad10)") (class "Default")
      (node (ref "H2") (pin "10") (pinfunction "B3_10") (pintype "passive"))
    )
    (net (code "301") (name "unconnected-(H2-B4-Pad9)") (class "Default")
      (node (ref "H2") (pin "9") (pinfunction "B4_9") (pintype "passive"))
    )
    (net (code "302") (name "unconnected-(H2-B5-Pad8)") (class "Default")
      (node (ref "H2") (pin "8") (pinfunction "B5_8") (pintype "passive"))
    )
    (net (code "303") (name "unconnected-(H2-B6-Pad7)") (class "Default")
      (node (ref "H2") (pin "7") (pinfunction "B6_7") (pintype "passive"))
    )
    (net (code "304") (name "unconnected-(H2-B7-Pad6)") (class "Default")
      (node (ref "H2") (pin "6") (pinfunction "B7_6") (pintype "passive"))
    )
    (net (code "305") (name "unconnected-(H2-B8-Pad5)") (class "Default")
      (node (ref "H2") (pin "5") (pinfunction "B8_5") (pintype "passive"))
    )
    (net (code "306") (name "unconnected-(H2-B9-Pad4)") (class "Default")
      (node (ref "H2") (pin "4") (pinfunction "B9_4") (pintype "passive"))
    )
    (net (code "307") (name "unconnected-(H2-B12-Pad20)") (class "Default")
      (node (ref "H2") (pin "20") (pinfunction "B12_20") (pintype "passive"))
    )
    (net (code "308") (name "unconnected-(H2-B13-Pad19)") (class "Default")
      (node (ref "H2") (pin "19") (pinfunction "B13_19") (pintype "passive"))
    )
    (net (code "309") (name "unconnected-(H2-B14-Pad18)") (class "Default")
      (node (ref "H2") (pin "18") (pinfunction "B14_18") (pintype "passive"))
    )
    (net (code "310") (name "unconnected-(H2-B15-Pad17)") (class "Default")
      (node (ref "H2") (pin "17") (pinfunction "B15_17") (pintype "passive"))
    )
    (net (code "311") (name "unconnected-(H2-G-Pad2)") (class "Default")
      (node (ref "H2") (pin "2") (pinfunction "G_2") (pintype "passive"))
    )
    (net (code "312") (name "unconnected-(H2-Pad21)") (class "Default")
      (node (ref "H2") (pin "21") (pinfunction "21_21") (pintype "passive"))
    )
    (net (code "313") (name "unconnected-(H2-Pad22)") (class "Default")
      (node (ref "H2") (pin "22") (pinfunction "22_22") (pintype "passive"))
    )
    (net (code "314") (name "unconnected-(H2-Pad23)") (class "Default")
      (node (ref "H2") (pin "23") (pinfunction "23_23") (pintype "passive"))
    )
    (net (code "315") (name "unconnected-(H2-Pad24)") (class "Default")
      (node (ref "H2") (pin "24") (pinfunction "24_24") (pintype "passive"))
    )
    (net (code "316") (name "unconnected-(H2-Pad33)") (class "Default")
      (node (ref "H2") (pin "33") (pinfunction "33_33") (pintype "passive"))
    )
    (net (code "317") (name "unconnected-(H2-Pad34)") (class "Default")
      (node (ref "H2") (pin "34") (pinfunction "34_34") (pintype "passive"))
    )
    (net (code "318") (name "unconnected-(H2-Pad37)") (class "Default")
      (node (ref "H2") (pin "37") (pinfunction "37_37") (pintype "passive"))
    )
    (net (code "319") (name "unconnected-(M_C-Z-Pad3)") (class "Default")
      (node (ref "M_C") (pin "3") (pinfunction "Z_3") (pintype "bidirectional"))
    )
    (net (code "320") (name "unconnected-(M_R-Z-Pad3)") (class "Default")
      (node (ref "M_R") (pin "3") (pinfunction "Z_3") (pintype "bidirectional"))
    )
  )
)
